# trig3_board_de0-nano.net
KiCad netlist of a schematic drawn in EAGLE
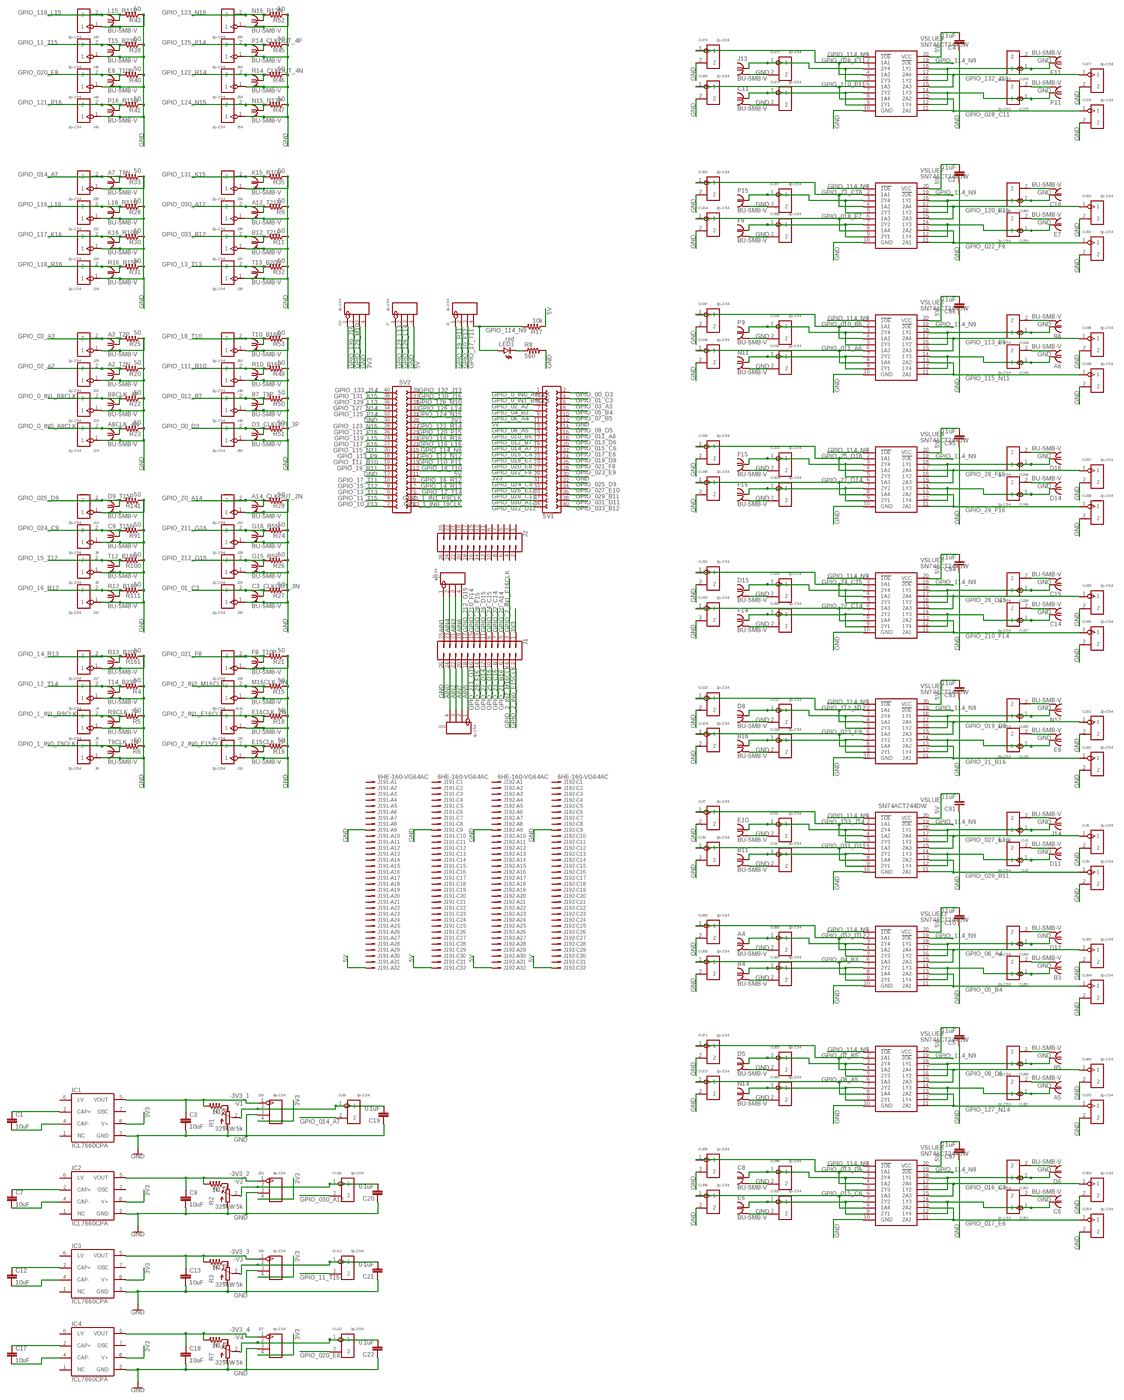
[diagram p0: schematic, sheet 1, overview]
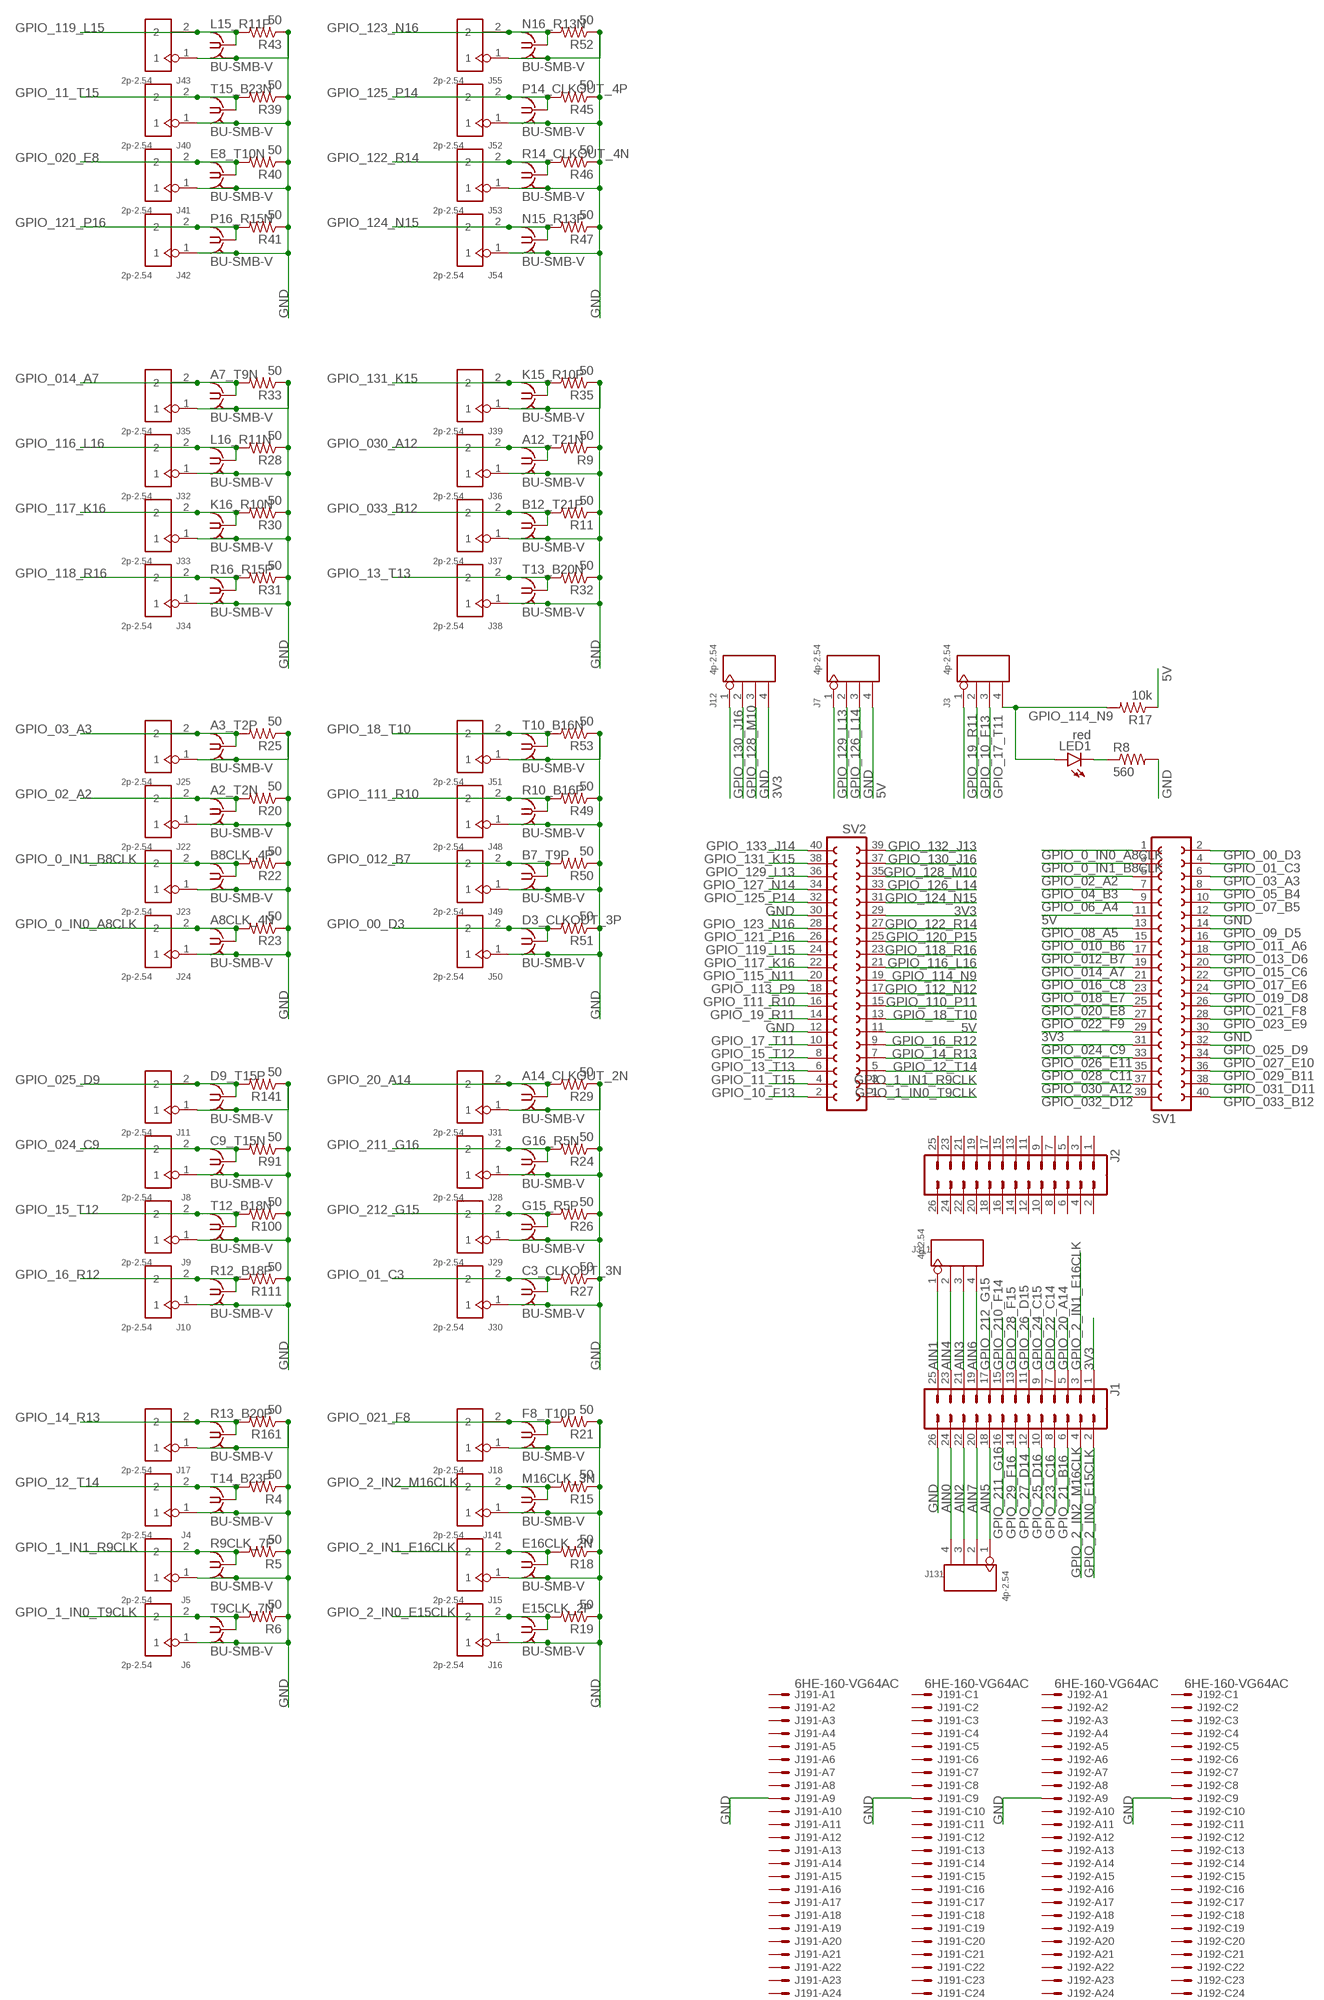
[diagram p1: schematic, sheet 1, part 1 of 4]
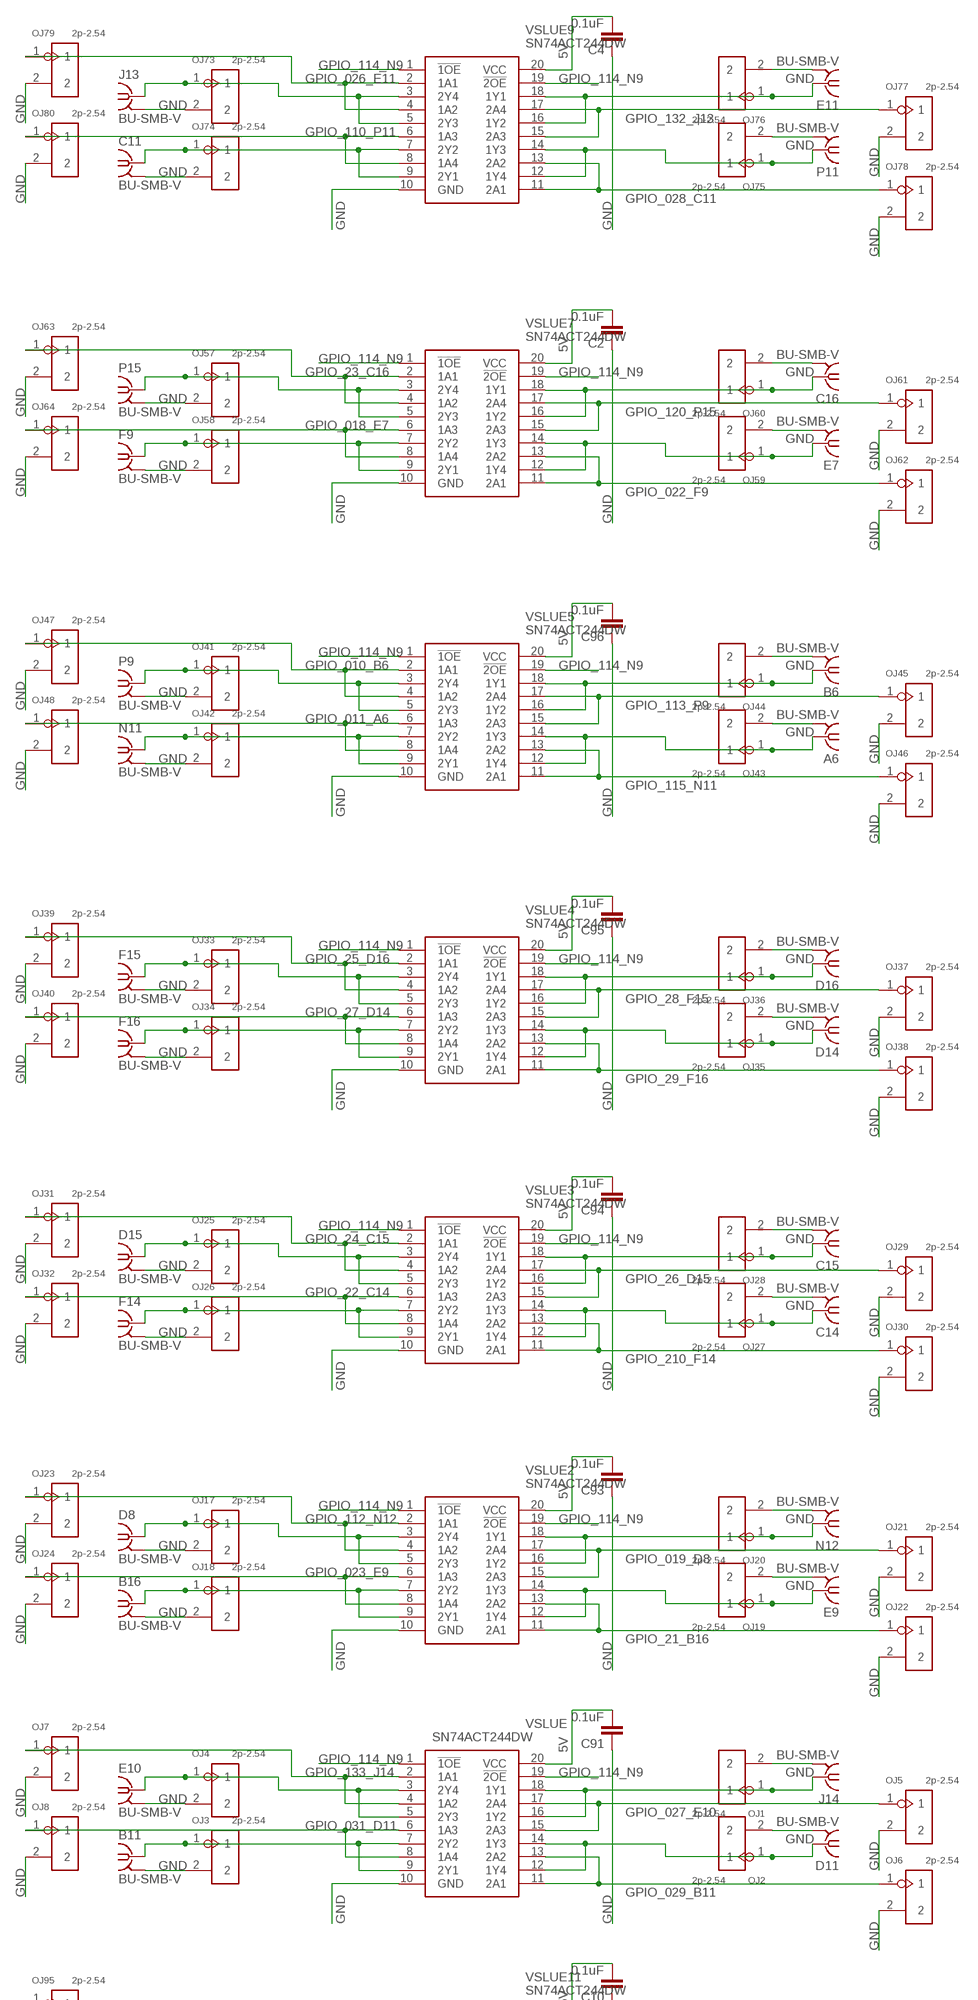
[diagram p2: schematic, sheet 1, part 2 of 4]
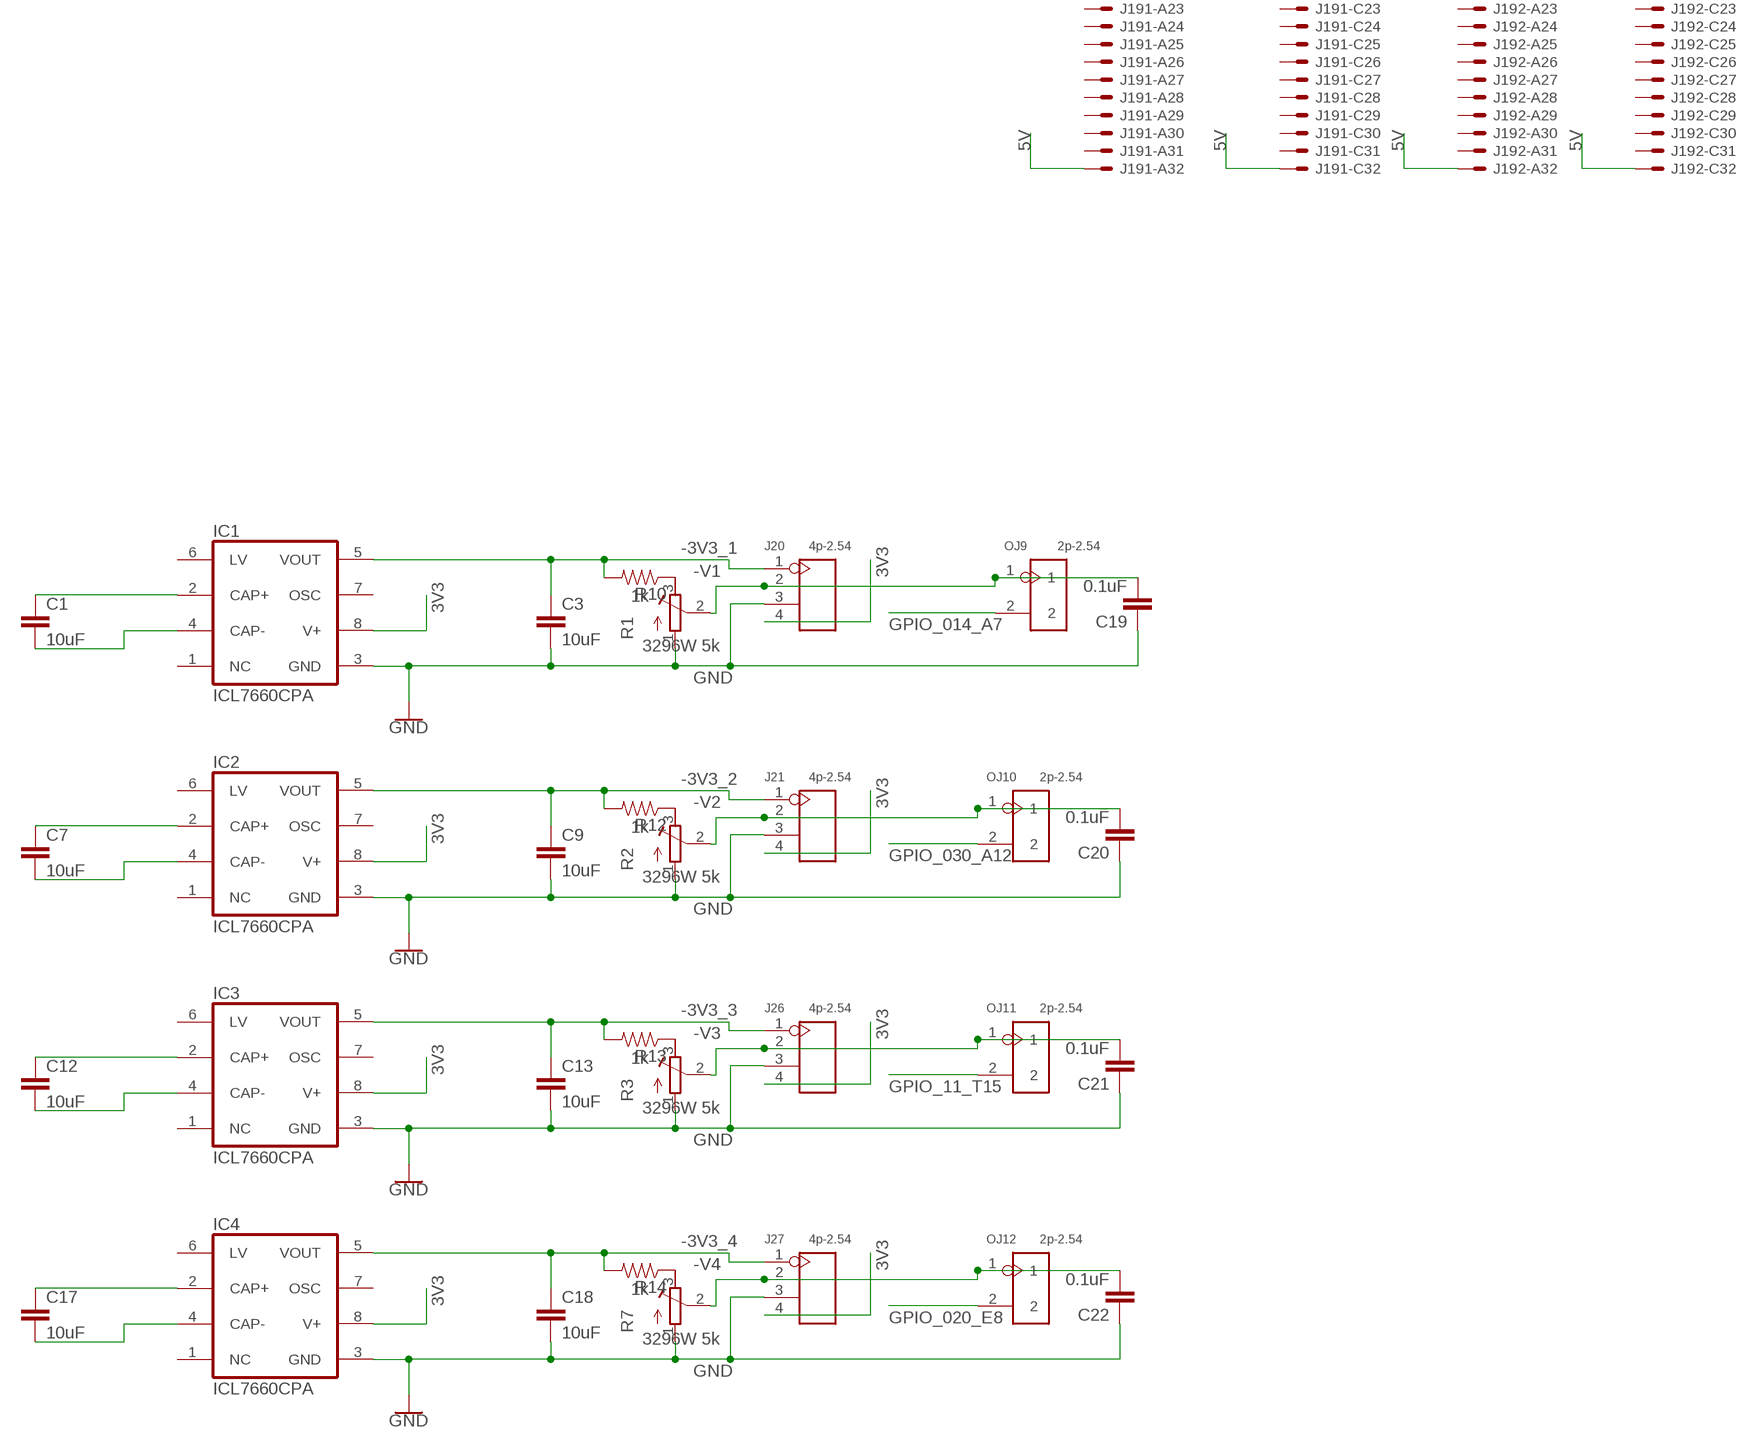
[diagram p3: schematic, sheet 1, part 3 of 4]
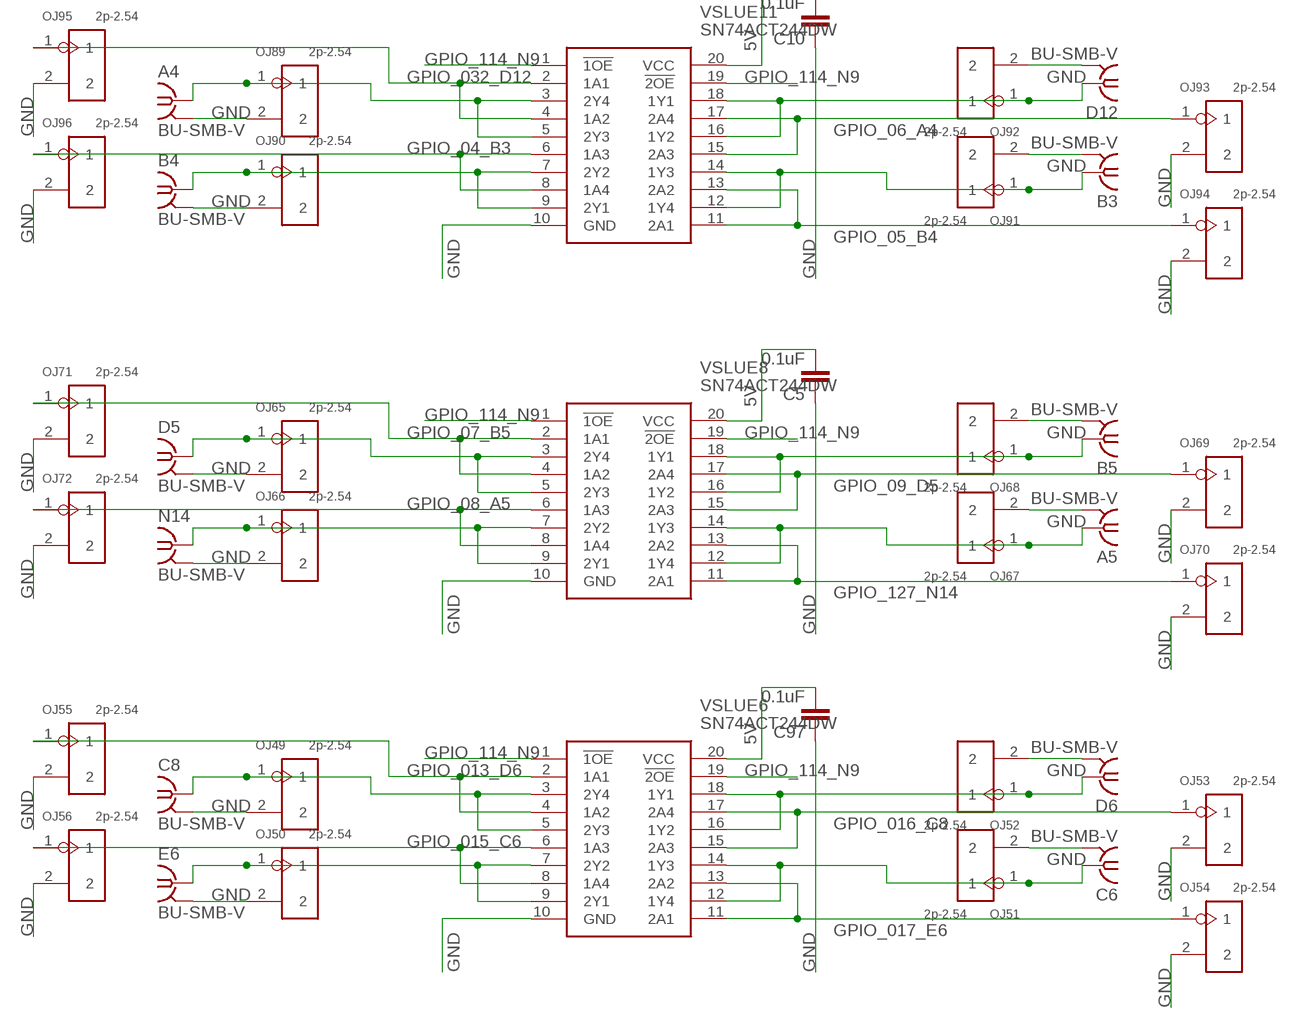
[diagram p4: schematic, sheet 1, part 4 of 4]

(export (version "E")
  (design (tool "Eeschema 10.0.6"))
  (components
    (comp (ref "A2_T2N")
      (value "BU-SMB-V")
      (footprint "eagle-import:BU-SMB-V")
      (libsource (lib "eagle-import") (part "BU-SMB-V"))
    )
    (comp (ref "A3_T2P")
      (value "BU-SMB-V")
      (footprint "eagle-import:BU-SMB-V")
      (libsource (lib "eagle-import") (part "BU-SMB-V"))
    )
    (comp (ref "A4")
      (value "BU-SMB-V")
      (footprint "eagle-import:BU-SMB-V")
      (libsource (lib "eagle-import") (part "BU-SMB-V"))
    )
    (comp (ref "A5")
      (value "BU-SMB-V")
      (footprint "eagle-import:BU-SMB-V")
      (libsource (lib "eagle-import") (part "BU-SMB-V"))
    )
    (comp (ref "A6")
      (value "BU-SMB-V")
      (footprint "eagle-import:BU-SMB-V")
      (libsource (lib "eagle-import") (part "BU-SMB-V"))
    )
    (comp (ref "A7_T9N")
      (value "BU-SMB-V")
      (footprint "eagle-import:BU-SMB-V")
      (libsource (lib "eagle-import") (part "BU-SMB-V"))
    )
    (comp (ref "A8CLK_4N")
      (value "BU-SMB-V")
      (footprint "eagle-import:BU-SMB-V")
      (libsource (lib "eagle-import") (part "BU-SMB-V"))
    )
    (comp (ref "A12_T21N")
      (value "BU-SMB-V")
      (footprint "eagle-import:BU-SMB-V")
      (libsource (lib "eagle-import") (part "BU-SMB-V"))
    )
    (comp (ref "A14_CLKOUT_2N")
      (value "BU-SMB-V")
      (footprint "eagle-import:BU-SMB-V")
      (libsource (lib "eagle-import") (part "BU-SMB-V"))
    )
    (comp (ref "B3")
      (value "BU-SMB-V")
      (footprint "eagle-import:BU-SMB-V")
      (libsource (lib "eagle-import") (part "BU-SMB-V"))
    )
    (comp (ref "B4")
      (value "BU-SMB-V")
      (footprint "eagle-import:BU-SMB-V")
      (libsource (lib "eagle-import") (part "BU-SMB-V"))
    )
    (comp (ref "B5")
      (value "BU-SMB-V")
      (footprint "eagle-import:BU-SMB-V")
      (libsource (lib "eagle-import") (part "BU-SMB-V"))
    )
    (comp (ref "B6")
      (value "BU-SMB-V")
      (footprint "eagle-import:BU-SMB-V")
      (libsource (lib "eagle-import") (part "BU-SMB-V"))
    )
    (comp (ref "B7_T9P")
      (value "BU-SMB-V")
      (footprint "eagle-import:BU-SMB-V")
      (libsource (lib "eagle-import") (part "BU-SMB-V"))
    )
    (comp (ref "B8CLK_4P")
      (value "BU-SMB-V")
      (footprint "eagle-import:BU-SMB-V")
      (libsource (lib "eagle-import") (part "BU-SMB-V"))
    )
    (comp (ref "B11")
      (value "BU-SMB-V")
      (footprint "eagle-import:BU-SMB-V")
      (libsource (lib "eagle-import") (part "BU-SMB-V"))
    )
    (comp (ref "B12_T21P")
      (value "BU-SMB-V")
      (footprint "eagle-import:BU-SMB-V")
      (libsource (lib "eagle-import") (part "BU-SMB-V"))
    )
    (comp (ref "B16")
      (value "BU-SMB-V")
      (footprint "eagle-import:BU-SMB-V")
      (libsource (lib "eagle-import") (part "BU-SMB-V"))
    )
    (comp (ref "C1")
      (value "10uF")
      (footprint "eagle-import:CAP-PTH-5MM")
      (libsource (lib "eagle-import") (part "CAPPTH1"))
    )
    (comp (ref "C2")
      (value "0.1uF")
      (footprint "eagle-import:0805")
      (libsource (lib "eagle-import") (part "CAP0805"))
    )
    (comp (ref "C3")
      (value "10uF")
      (footprint "eagle-import:CAP-PTH-5MM")
      (libsource (lib "eagle-import") (part "CAPPTH1"))
    )
    (comp (ref "C3_CLKOUT_3N")
      (value "BU-SMB-V")
      (footprint "eagle-import:BU-SMB-V")
      (libsource (lib "eagle-import") (part "BU-SMB-V"))
    )
    (comp (ref "C4")
      (value "0.1uF")
      (footprint "eagle-import:0805")
      (libsource (lib "eagle-import") (part "CAP0805"))
    )
    (comp (ref "C5")
      (value "0.1uF")
      (footprint "eagle-import:0805")
      (libsource (lib "eagle-import") (part "CAP0805"))
    )
    (comp (ref "C6")
      (value "BU-SMB-V")
      (footprint "eagle-import:BU-SMB-V")
      (libsource (lib "eagle-import") (part "BU-SMB-V"))
    )
    (comp (ref "C7")
      (value "10uF")
      (footprint "eagle-import:CAP-PTH-5MM")
      (libsource (lib "eagle-import") (part "CAPPTH1"))
    )
    (comp (ref "C8")
      (value "BU-SMB-V")
      (footprint "eagle-import:BU-SMB-V")
      (libsource (lib "eagle-import") (part "BU-SMB-V"))
    )
    (comp (ref "C9")
      (value "10uF")
      (footprint "eagle-import:CAP-PTH-5MM")
      (libsource (lib "eagle-import") (part "CAPPTH1"))
    )
    (comp (ref "C9_T15N")
      (value "BU-SMB-V")
      (footprint "eagle-import:BU-SMB-V")
      (libsource (lib "eagle-import") (part "BU-SMB-V"))
    )
    (comp (ref "C10")
      (value "0.1uF")
      (footprint "eagle-import:0805")
      (libsource (lib "eagle-import") (part "CAP0805"))
    )
    (comp (ref "C11")
      (value "BU-SMB-V")
      (footprint "eagle-import:BU-SMB-V")
      (libsource (lib "eagle-import") (part "BU-SMB-V"))
    )
    (comp (ref "C12")
      (value "10uF")
      (footprint "eagle-import:CAP-PTH-5MM")
      (libsource (lib "eagle-import") (part "CAPPTH1"))
    )
    (comp (ref "C13")
      (value "10uF")
      (footprint "eagle-import:CAP-PTH-5MM")
      (libsource (lib "eagle-import") (part "CAPPTH1"))
    )
    (comp (ref "C14")
      (value "BU-SMB-V")
      (footprint "eagle-import:BU-SMB-V")
      (libsource (lib "eagle-import") (part "BU-SMB-V"))
    )
    (comp (ref "C15")
      (value "BU-SMB-V")
      (footprint "eagle-import:BU-SMB-V")
      (libsource (lib "eagle-import") (part "BU-SMB-V"))
    )
    (comp (ref "C16")
      (value "BU-SMB-V")
      (footprint "eagle-import:BU-SMB-V")
      (libsource (lib "eagle-import") (part "BU-SMB-V"))
    )
    (comp (ref "C17")
      (value "10uF")
      (footprint "eagle-import:CAP-PTH-5MM")
      (libsource (lib "eagle-import") (part "CAPPTH1"))
    )
    (comp (ref "C18")
      (value "10uF")
      (footprint "eagle-import:CAP-PTH-5MM")
      (libsource (lib "eagle-import") (part "CAPPTH1"))
    )
    (comp (ref "C19")
      (value "0.1uF")
      (footprint "eagle-import:0805")
      (libsource (lib "eagle-import") (part "CAP0805"))
    )
    (comp (ref "C20")
      (value "0.1uF")
      (footprint "eagle-import:0805")
      (libsource (lib "eagle-import") (part "CAP0805"))
    )
    (comp (ref "C21")
      (value "0.1uF")
      (footprint "eagle-import:0805")
      (libsource (lib "eagle-import") (part "CAP0805"))
    )
    (comp (ref "C22")
      (value "0.1uF")
      (footprint "eagle-import:0805")
      (libsource (lib "eagle-import") (part "CAP0805"))
    )
    (comp (ref "C91")
      (value "0.1uF")
      (footprint "eagle-import:0805")
      (libsource (lib "eagle-import") (part "CAP0805"))
    )
    (comp (ref "C93")
      (value "0.1uF")
      (footprint "eagle-import:0805")
      (libsource (lib "eagle-import") (part "CAP0805"))
    )
    (comp (ref "C94")
      (value "0.1uF")
      (footprint "eagle-import:0805")
      (libsource (lib "eagle-import") (part "CAP0805"))
    )
    (comp (ref "C95")
      (value "0.1uF")
      (footprint "eagle-import:0805")
      (libsource (lib "eagle-import") (part "CAP0805"))
    )
    (comp (ref "C96")
      (value "0.1uF")
      (footprint "eagle-import:0805")
      (libsource (lib "eagle-import") (part "CAP0805"))
    )
    (comp (ref "C97")
      (value "0.1uF")
      (footprint "eagle-import:0805")
      (libsource (lib "eagle-import") (part "CAP0805"))
    )
    (comp (ref "D3_CLKOUT_3P")
      (value "BU-SMB-V")
      (footprint "eagle-import:BU-SMB-V")
      (libsource (lib "eagle-import") (part "BU-SMB-V"))
    )
    (comp (ref "D5")
      (value "BU-SMB-V")
      (footprint "eagle-import:BU-SMB-V")
      (libsource (lib "eagle-import") (part "BU-SMB-V"))
    )
    (comp (ref "D6")
      (value "BU-SMB-V")
      (footprint "eagle-import:BU-SMB-V")
      (libsource (lib "eagle-import") (part "BU-SMB-V"))
    )
    (comp (ref "D8")
      (value "BU-SMB-V")
      (footprint "eagle-import:BU-SMB-V")
      (libsource (lib "eagle-import") (part "BU-SMB-V"))
    )
    (comp (ref "D9_T15P")
      (value "BU-SMB-V")
      (footprint "eagle-import:BU-SMB-V")
      (libsource (lib "eagle-import") (part "BU-SMB-V"))
    )
    (comp (ref "D11")
      (value "BU-SMB-V")
      (footprint "eagle-import:BU-SMB-V")
      (libsource (lib "eagle-import") (part "BU-SMB-V"))
    )
    (comp (ref "D12")
      (value "BU-SMB-V")
      (footprint "eagle-import:BU-SMB-V")
      (libsource (lib "eagle-import") (part "BU-SMB-V"))
    )
    (comp (ref "D14")
      (value "BU-SMB-V")
      (footprint "eagle-import:BU-SMB-V")
      (libsource (lib "eagle-import") (part "BU-SMB-V"))
    )
    (comp (ref "D15")
      (value "BU-SMB-V")
      (footprint "eagle-import:BU-SMB-V")
      (libsource (lib "eagle-import") (part "BU-SMB-V"))
    )
    (comp (ref "D16")
      (value "BU-SMB-V")
      (footprint "eagle-import:BU-SMB-V")
      (libsource (lib "eagle-import") (part "BU-SMB-V"))
    )
    (comp (ref "E6")
      (value "BU-SMB-V")
      (footprint "eagle-import:BU-SMB-V")
      (libsource (lib "eagle-import") (part "BU-SMB-V"))
    )
    (comp (ref "E7")
      (value "BU-SMB-V")
      (footprint "eagle-import:BU-SMB-V")
      (libsource (lib "eagle-import") (part "BU-SMB-V"))
    )
    (comp (ref "E8_T10N")
      (value "BU-SMB-V")
      (footprint "eagle-import:BU-SMB-V")
      (libsource (lib "eagle-import") (part "BU-SMB-V"))
    )
    (comp (ref "E9")
      (value "BU-SMB-V")
      (footprint "eagle-import:BU-SMB-V")
      (libsource (lib "eagle-import") (part "BU-SMB-V"))
    )
    (comp (ref "E10")
      (value "BU-SMB-V")
      (footprint "eagle-import:BU-SMB-V")
      (libsource (lib "eagle-import") (part "BU-SMB-V"))
    )
    (comp (ref "E11")
      (value "BU-SMB-V")
      (footprint "eagle-import:BU-SMB-V")
      (libsource (lib "eagle-import") (part "BU-SMB-V"))
    )
    (comp (ref "E15CLK_2P")
      (value "BU-SMB-V")
      (footprint "eagle-import:BU-SMB-V")
      (libsource (lib "eagle-import") (part "BU-SMB-V"))
    )
    (comp (ref "E16CLK_2N")
      (value "BU-SMB-V")
      (footprint "eagle-import:BU-SMB-V")
      (libsource (lib "eagle-import") (part "BU-SMB-V"))
    )
    (comp (ref "F8_T10P")
      (value "BU-SMB-V")
      (footprint "eagle-import:BU-SMB-V")
      (libsource (lib "eagle-import") (part "BU-SMB-V"))
    )
    (comp (ref "F9")
      (value "BU-SMB-V")
      (footprint "eagle-import:BU-SMB-V")
      (libsource (lib "eagle-import") (part "BU-SMB-V"))
    )
    (comp (ref "F14")
      (value "BU-SMB-V")
      (footprint "eagle-import:BU-SMB-V")
      (libsource (lib "eagle-import") (part "BU-SMB-V"))
    )
    (comp (ref "F15")
      (value "BU-SMB-V")
      (footprint "eagle-import:BU-SMB-V")
      (libsource (lib "eagle-import") (part "BU-SMB-V"))
    )
    (comp (ref "F16")
      (value "BU-SMB-V")
      (footprint "eagle-import:BU-SMB-V")
      (libsource (lib "eagle-import") (part "BU-SMB-V"))
    )
    (comp (ref "G15_R5P")
      (value "BU-SMB-V")
      (footprint "eagle-import:BU-SMB-V")
      (libsource (lib "eagle-import") (part "BU-SMB-V"))
    )
    (comp (ref "G16_R5N")
      (value "BU-SMB-V")
      (footprint "eagle-import:BU-SMB-V")
      (libsource (lib "eagle-import") (part "BU-SMB-V"))
    )
    (comp (ref "IC1")
      (value "ICL7660CPA")
      (footprint "eagle-import:DIL08")
      (fields (field (name "MF") "INTERSIL"))
      (libsource (lib "eagle-import") (part "ICL7660CPA"))
    )
    (comp (ref "IC2")
      (value "ICL7660CPA")
      (footprint "eagle-import:DIL08")
      (fields (field (name "MF") "INTERSIL"))
      (libsource (lib "eagle-import") (part "ICL7660CPA"))
    )
    (comp (ref "IC3")
      (value "ICL7660CPA")
      (footprint "eagle-import:DIL08")
      (fields (field (name "MF") "INTERSIL"))
      (libsource (lib "eagle-import") (part "ICL7660CPA"))
    )
    (comp (ref "IC4")
      (value "ICL7660CPA")
      (footprint "eagle-import:DIL08")
      (fields (field (name "MF") "INTERSIL"))
      (libsource (lib "eagle-import") (part "ICL7660CPA"))
    )
    (comp (ref "J1")
      (value "M13X22X13")
      (footprint "eagle-import:2X13")
      (libsource (lib "eagle-import") (part "M13X22X13"))
    )
    (comp (ref "J2")
      (value "M13X22X13")
      (footprint "eagle-import:2X13")
      (libsource (lib "eagle-import") (part "M13X22X13"))
    )
    (comp (ref "J3")
      (value "4p-2.54")
      (footprint "eagle-import:H4-2.54")
      (fields (field (name "MPN") "F185-1104A1BSYA1"))
      (libsource (lib "eagle-import") (part "DIP-BLACK-FEMALE-HEADER-VERT(4P-2.54)"))
    )
    (comp (ref "J4")
      (value "2p-2.54")
      (footprint "eagle-import:H2-2.54")
      (fields (field (name "MPN") "P125-1102A0BS116A1"))
      (libsource (lib "eagle-import") (part "DIP-BLACK-MALE-HEADER-VERT(2P-2.54)"))
    )
    (comp (ref "J5")
      (value "2p-2.54")
      (footprint "eagle-import:H2-2.54")
      (fields (field (name "MPN") "P125-1102A0BS116A1"))
      (libsource (lib "eagle-import") (part "DIP-BLACK-MALE-HEADER-VERT(2P-2.54)"))
    )
    (comp (ref "J6")
      (value "2p-2.54")
      (footprint "eagle-import:H2-2.54")
      (fields (field (name "MPN") "P125-1102A0BS116A1"))
      (libsource (lib "eagle-import") (part "DIP-BLACK-MALE-HEADER-VERT(2P-2.54)"))
    )
    (comp (ref "J7")
      (value "4p-2.54")
      (footprint "eagle-import:H4-2.54")
      (fields (field (name "MPN") "F185-1104A1BSYA1"))
      (libsource (lib "eagle-import") (part "DIP-BLACK-FEMALE-HEADER-VERT(4P-2.54)"))
    )
    (comp (ref "J8")
      (value "2p-2.54")
      (footprint "eagle-import:H2-2.54")
      (fields (field (name "MPN") "P125-1102A0BS116A1"))
      (libsource (lib "eagle-import") (part "DIP-BLACK-MALE-HEADER-VERT(2P-2.54)"))
    )
    (comp (ref "J9")
      (value "2p-2.54")
      (footprint "eagle-import:H2-2.54")
      (fields (field (name "MPN") "P125-1102A0BS116A1"))
      (libsource (lib "eagle-import") (part "DIP-BLACK-MALE-HEADER-VERT(2P-2.54)"))
    )
    (comp (ref "J10")
      (value "2p-2.54")
      (footprint "eagle-import:H2-2.54")
      (fields (field (name "MPN") "P125-1102A0BS116A1"))
      (libsource (lib "eagle-import") (part "DIP-BLACK-MALE-HEADER-VERT(2P-2.54)"))
    )
    (comp (ref "J11")
      (value "2p-2.54")
      (footprint "eagle-import:H2-2.54")
      (fields (field (name "MPN") "P125-1102A0BS116A1"))
      (libsource (lib "eagle-import") (part "DIP-BLACK-MALE-HEADER-VERT(2P-2.54)"))
    )
    (comp (ref "J12")
      (value "4p-2.54")
      (footprint "eagle-import:H4-2.54")
      (fields (field (name "MPN") "F185-1104A1BSYA1"))
      (libsource (lib "eagle-import") (part "DIP-BLACK-FEMALE-HEADER-VERT(4P-2.54)"))
    )
    (comp (ref "J13")
      (value "BU-SMB-V")
      (footprint "eagle-import:BU-SMB-V")
      (libsource (lib "eagle-import") (part "BU-SMB-V"))
    )
    (comp (ref "J14")
      (value "BU-SMB-V")
      (footprint "eagle-import:BU-SMB-V")
      (libsource (lib "eagle-import") (part "BU-SMB-V"))
    )
    (comp (ref "J15")
      (value "2p-2.54")
      (footprint "eagle-import:H2-2.54")
      (fields (field (name "MPN") "P125-1102A0BS116A1"))
      (libsource (lib "eagle-import") (part "DIP-BLACK-MALE-HEADER-VERT(2P-2.54)"))
    )
    (comp (ref "J16")
      (value "2p-2.54")
      (footprint "eagle-import:H2-2.54")
      (fields (field (name "MPN") "P125-1102A0BS116A1"))
      (libsource (lib "eagle-import") (part "DIP-BLACK-MALE-HEADER-VERT(2P-2.54)"))
    )
    (comp (ref "J17")
      (value "2p-2.54")
      (footprint "eagle-import:H2-2.54")
      (fields (field (name "MPN") "P125-1102A0BS116A1"))
      (libsource (lib "eagle-import") (part "DIP-BLACK-MALE-HEADER-VERT(2P-2.54)"))
    )
    (comp (ref "J18")
      (value "2p-2.54")
      (footprint "eagle-import:H2-2.54")
      (fields (field (name "MPN") "P125-1102A0BS116A1"))
      (libsource (lib "eagle-import") (part "DIP-BLACK-MALE-HEADER-VERT(2P-2.54)"))
    )
    (comp (ref "J19")
      (value "6HE-160-VG64AC")
      (footprint "eagle-import:6HE_160-VG64AC")
      (libsource (lib "eagle-import") (part "6HE-?-VG64AC160"))
    )
    (comp (ref "J20")
      (value "4p-2.54")
      (footprint "eagle-import:H4-2.54")
      (fields (field (name "MPN") "P125-1104A0BS116A1"))
      (libsource (lib "eagle-import") (part "DIP-BLACK-MALE-HEADER-VERT(4P-2.54)"))
    )
    (comp (ref "J21")
      (value "4p-2.54")
      (footprint "eagle-import:H4-2.54")
      (fields (field (name "MPN") "P125-1104A0BS116A1"))
      (libsource (lib "eagle-import") (part "DIP-BLACK-MALE-HEADER-VERT(4P-2.54)"))
    )
    (comp (ref "J22")
      (value "2p-2.54")
      (footprint "eagle-import:H2-2.54")
      (fields (field (name "MPN") "P125-1102A0BS116A1"))
      (libsource (lib "eagle-import") (part "DIP-BLACK-MALE-HEADER-VERT(2P-2.54)"))
    )
    (comp (ref "J23")
      (value "2p-2.54")
      (footprint "eagle-import:H2-2.54")
      (fields (field (name "MPN") "P125-1102A0BS116A1"))
      (libsource (lib "eagle-import") (part "DIP-BLACK-MALE-HEADER-VERT(2P-2.54)"))
    )
    (comp (ref "J24")
      (value "2p-2.54")
      (footprint "eagle-import:H2-2.54")
      (fields (field (name "MPN") "P125-1102A0BS116A1"))
      (libsource (lib "eagle-import") (part "DIP-BLACK-MALE-HEADER-VERT(2P-2.54)"))
    )
    (comp (ref "J25")
      (value "2p-2.54")
      (footprint "eagle-import:H2-2.54")
      (fields (field (name "MPN") "P125-1102A0BS116A1"))
      (libsource (lib "eagle-import") (part "DIP-BLACK-MALE-HEADER-VERT(2P-2.54)"))
    )
    (comp (ref "J26")
      (value "4p-2.54")
      (footprint "eagle-import:H4-2.54")
      (fields (field (name "MPN") "P125-1104A0BS116A1"))
      (libsource (lib "eagle-import") (part "DIP-BLACK-MALE-HEADER-VERT(4P-2.54)"))
    )
    (comp (ref "J27")
      (value "4p-2.54")
      (footprint "eagle-import:H4-2.54")
      (fields (field (name "MPN") "P125-1104A0BS116A1"))
      (libsource (lib "eagle-import") (part "DIP-BLACK-MALE-HEADER-VERT(4P-2.54)"))
    )
    (comp (ref "J28")
      (value "2p-2.54")
      (footprint "eagle-import:H2-2.54")
      (fields (field (name "MPN") "P125-1102A0BS116A1"))
      (libsource (lib "eagle-import") (part "DIP-BLACK-MALE-HEADER-VERT(2P-2.54)"))
    )
    (comp (ref "J29")
      (value "2p-2.54")
      (footprint "eagle-import:H2-2.54")
      (fields (field (name "MPN") "P125-1102A0BS116A1"))
      (libsource (lib "eagle-import") (part "DIP-BLACK-MALE-HEADER-VERT(2P-2.54)"))
    )
    (comp (ref "J30")
      (value "2p-2.54")
      (footprint "eagle-import:H2-2.54")
      (fields (field (name "MPN") "P125-1102A0BS116A1"))
      (libsource (lib "eagle-import") (part "DIP-BLACK-MALE-HEADER-VERT(2P-2.54)"))
    )
    (comp (ref "J31")
      (value "2p-2.54")
      (footprint "eagle-import:H2-2.54")
      (fields (field (name "MPN") "P125-1102A0BS116A1"))
      (libsource (lib "eagle-import") (part "DIP-BLACK-MALE-HEADER-VERT(2P-2.54)"))
    )
    (comp (ref "J32")
      (value "2p-2.54")
      (footprint "eagle-import:H2-2.54")
      (fields (field (name "MPN") "P125-1102A0BS116A1"))
      (libsource (lib "eagle-import") (part "DIP-BLACK-MALE-HEADER-VERT(2P-2.54)"))
    )
    (comp (ref "J33")
      (value "2p-2.54")
      (footprint "eagle-import:H2-2.54")
      (fields (field (name "MPN") "P125-1102A0BS116A1"))
      (libsource (lib "eagle-import") (part "DIP-BLACK-MALE-HEADER-VERT(2P-2.54)"))
    )
    (comp (ref "J34")
      (value "2p-2.54")
      (footprint "eagle-import:H2-2.54")
      (fields (field (name "MPN") "P125-1102A0BS116A1"))
      (libsource (lib "eagle-import") (part "DIP-BLACK-MALE-HEADER-VERT(2P-2.54)"))
    )
    (comp (ref "J35")
      (value "2p-2.54")
      (footprint "eagle-import:H2-2.54")
      (fields (field (name "MPN") "P125-1102A0BS116A1"))
      (libsource (lib "eagle-import") (part "DIP-BLACK-MALE-HEADER-VERT(2P-2.54)"))
    )
    (comp (ref "J36")
      (value "2p-2.54")
      (footprint "eagle-import:H2-2.54")
      (fields (field (name "MPN") "P125-1102A0BS116A1"))
      (libsource (lib "eagle-import") (part "DIP-BLACK-MALE-HEADER-VERT(2P-2.54)"))
    )
    (comp (ref "J37")
      (value "2p-2.54")
      (footprint "eagle-import:H2-2.54")
      (fields (field (name "MPN") "P125-1102A0BS116A1"))
      (libsource (lib "eagle-import") (part "DIP-BLACK-MALE-HEADER-VERT(2P-2.54)"))
    )
    (comp (ref "J38")
      (value "2p-2.54")
      (footprint "eagle-import:H2-2.54")
      (fields (field (name "MPN") "P125-1102A0BS116A1"))
      (libsource (lib "eagle-import") (part "DIP-BLACK-MALE-HEADER-VERT(2P-2.54)"))
    )
    (comp (ref "J39")
      (value "2p-2.54")
      (footprint "eagle-import:H2-2.54")
      (fields (field (name "MPN") "P125-1102A0BS116A1"))
      (libsource (lib "eagle-import") (part "DIP-BLACK-MALE-HEADER-VERT(2P-2.54)"))
    )
    (comp (ref "J40")
      (value "2p-2.54")
      (footprint "eagle-import:H2-2.54")
      (fields (field (name "MPN") "P125-1102A0BS116A1"))
      (libsource (lib "eagle-import") (part "DIP-BLACK-MALE-HEADER-VERT(2P-2.54)"))
    )
    (comp (ref "J41")
      (value "2p-2.54")
      (footprint "eagle-import:H2-2.54")
      (fields (field (name "MPN") "P125-1102A0BS116A1"))
      (libsource (lib "eagle-import") (part "DIP-BLACK-MALE-HEADER-VERT(2P-2.54)"))
    )
    (comp (ref "J42")
      (value "2p-2.54")
      (footprint "eagle-import:H2-2.54")
      (fields (field (name "MPN") "P125-1102A0BS116A1"))
      (libsource (lib "eagle-import") (part "DIP-BLACK-MALE-HEADER-VERT(2P-2.54)"))
    )
    (comp (ref "J43")
      (value "2p-2.54")
      (footprint "eagle-import:H2-2.54")
      (fields (field (name "MPN") "P125-1102A0BS116A1"))
      (libsource (lib "eagle-import") (part "DIP-BLACK-MALE-HEADER-VERT(2P-2.54)"))
    )
    (comp (ref "J48")
      (value "2p-2.54")
      (footprint "eagle-import:H2-2.54")
      (fields (field (name "MPN") "P125-1102A0BS116A1"))
      (libsource (lib "eagle-import") (part "DIP-BLACK-MALE-HEADER-VERT(2P-2.54)"))
    )
    (comp (ref "J49")
      (value "2p-2.54")
      (footprint "eagle-import:H2-2.54")
      (fields (field (name "MPN") "P125-1102A0BS116A1"))
      (libsource (lib "eagle-import") (part "DIP-BLACK-MALE-HEADER-VERT(2P-2.54)"))
    )
    (comp (ref "J50")
      (value "2p-2.54")
      (footprint "eagle-import:H2-2.54")
      (fields (field (name "MPN") "P125-1102A0BS116A1"))
      (libsource (lib "eagle-import") (part "DIP-BLACK-MALE-HEADER-VERT(2P-2.54)"))
    )
    (comp (ref "J51")
      (value "2p-2.54")
      (footprint "eagle-import:H2-2.54")
      (fields (field (name "MPN") "P125-1102A0BS116A1"))
      (libsource (lib "eagle-import") (part "DIP-BLACK-MALE-HEADER-VERT(2P-2.54)"))
    )
    (comp (ref "J52")
      (value "2p-2.54")
      (footprint "eagle-import:H2-2.54")
      (fields (field (name "MPN") "P125-1102A0BS116A1"))
      (libsource (lib "eagle-import") (part "DIP-BLACK-MALE-HEADER-VERT(2P-2.54)"))
    )
    (comp (ref "J53")
      (value "2p-2.54")
      (footprint "eagle-import:H2-2.54")
      (fields (field (name "MPN") "P125-1102A0BS116A1"))
      (libsource (lib "eagle-import") (part "DIP-BLACK-MALE-HEADER-VERT(2P-2.54)"))
    )
    (comp (ref "J54")
      (value "2p-2.54")
      (footprint "eagle-import:H2-2.54")
      (fields (field (name "MPN") "P125-1102A0BS116A1"))
      (libsource (lib "eagle-import") (part "DIP-BLACK-MALE-HEADER-VERT(2P-2.54)"))
    )
    (comp (ref "J55")
      (value "2p-2.54")
      (footprint "eagle-import:H2-2.54")
      (fields (field (name "MPN") "P125-1102A0BS116A1"))
      (libsource (lib "eagle-import") (part "DIP-BLACK-MALE-HEADER-VERT(2P-2.54)"))
    )
    (comp (ref "J131")
      (value "4p-2.54")
      (footprint "eagle-import:H4-2.54")
      (fields (field (name "MPN") "F185-1104A1BSYA1"))
      (libsource (lib "eagle-import") (part "DIP-BLACK-FEMALE-HEADER-VERT(4P-2.54)"))
    )
    (comp (ref "J141")
      (value "2p-2.54")
      (footprint "eagle-import:H2-2.54")
      (fields (field (name "MPN") "P125-1102A0BS116A1"))
      (libsource (lib "eagle-import") (part "DIP-BLACK-MALE-HEADER-VERT(2P-2.54)"))
    )
    (comp (ref "J311")
      (value "4p-2.54")
      (footprint "eagle-import:H4-2.54")
      (fields (field (name "MPN") "F185-1104A1BSYA1"))
      (libsource (lib "eagle-import") (part "DIP-BLACK-FEMALE-HEADER-VERT(4P-2.54)"))
    )
    (comp (ref "K15_R10P")
      (value "BU-SMB-V")
      (footprint "eagle-import:BU-SMB-V")
      (libsource (lib "eagle-import") (part "BU-SMB-V"))
    )
    (comp (ref "K16_R10N")
      (value "BU-SMB-V")
      (footprint "eagle-import:BU-SMB-V")
      (libsource (lib "eagle-import") (part "BU-SMB-V"))
    )
    (comp (ref "L15_R11P")
      (value "BU-SMB-V")
      (footprint "eagle-import:BU-SMB-V")
      (libsource (lib "eagle-import") (part "BU-SMB-V"))
    )
    (comp (ref "L16_R11N")
      (value "BU-SMB-V")
      (footprint "eagle-import:BU-SMB-V")
      (libsource (lib "eagle-import") (part "BU-SMB-V"))
    )
    (comp (ref "LED1")
      (value "red")
      (footprint "eagle-import:CHIP-LED0805")
      (libsource (lib "eagle-import") (part "LEDCHIP-LED0805"))
    )
    (comp (ref "M16CLK_3N")
      (value "BU-SMB-V")
      (footprint "eagle-import:BU-SMB-V")
      (libsource (lib "eagle-import") (part "BU-SMB-V"))
    )
    (comp (ref "N11")
      (value "BU-SMB-V")
      (footprint "eagle-import:BU-SMB-V")
      (libsource (lib "eagle-import") (part "BU-SMB-V"))
    )
    (comp (ref "N12")
      (value "BU-SMB-V")
      (footprint "eagle-import:BU-SMB-V")
      (libsource (lib "eagle-import") (part "BU-SMB-V"))
    )
    (comp (ref "N14")
      (value "BU-SMB-V")
      (footprint "eagle-import:BU-SMB-V")
      (libsource (lib "eagle-import") (part "BU-SMB-V"))
    )
    (comp (ref "N15_R13P")
      (value "BU-SMB-V")
      (footprint "eagle-import:BU-SMB-V")
      (libsource (lib "eagle-import") (part "BU-SMB-V"))
    )
    (comp (ref "N16_R13N")
      (value "BU-SMB-V")
      (footprint "eagle-import:BU-SMB-V")
      (libsource (lib "eagle-import") (part "BU-SMB-V"))
    )
    (comp (ref "OJ1")
      (value "2p-2.54")
      (footprint "eagle-import:H2-2.54")
      (fields (field (name "MPN") "P125-1102A0BS116A1"))
      (libsource (lib "eagle-import") (part "DIP-BLACK-MALE-HEADER-VERT(2P-2.54)"))
    )
    (comp (ref "OJ2")
      (value "2p-2.54")
      (footprint "eagle-import:H2-2.54")
      (fields (field (name "MPN") "P125-1102A0BS116A1"))
      (libsource (lib "eagle-import") (part "DIP-BLACK-MALE-HEADER-VERT(2P-2.54)"))
    )
    (comp (ref "OJ3")
      (value "2p-2.54")
      (footprint "eagle-import:H2-2.54")
      (fields (field (name "MPN") "P125-1102A0BS116A1"))
      (libsource (lib "eagle-import") (part "DIP-BLACK-MALE-HEADER-VERT(2P-2.54)"))
    )
    (comp (ref "OJ4")
      (value "2p-2.54")
      (footprint "eagle-import:H2-2.54")
      (fields (field (name "MPN") "P125-1102A0BS116A1"))
      (libsource (lib "eagle-import") (part "DIP-BLACK-MALE-HEADER-VERT(2P-2.54)"))
    )
    (comp (ref "OJ5")
      (value "2p-2.54")
      (footprint "eagle-import:H2-2.54")
      (fields (field (name "MPN") "P125-1102A0BS116A1"))
      (libsource (lib "eagle-import") (part "DIP-BLACK-MALE-HEADER-VERT(2P-2.54)"))
    )
    (comp (ref "OJ6")
      (value "2p-2.54")
      (footprint "eagle-import:H2-2.54")
      (fields (field (name "MPN") "P125-1102A0BS116A1"))
      (libsource (lib "eagle-import") (part "DIP-BLACK-MALE-HEADER-VERT(2P-2.54)"))
    )
    (comp (ref "OJ7")
      (value "2p-2.54")
      (footprint "eagle-import:H2-2.54")
      (fields (field (name "MPN") "P125-1102A0BS116A1"))
      (libsource (lib "eagle-import") (part "DIP-BLACK-MALE-HEADER-VERT(2P-2.54)"))
    )
    (comp (ref "OJ8")
      (value "2p-2.54")
      (footprint "eagle-import:H2-2.54")
      (fields (field (name "MPN") "P125-1102A0BS116A1"))
      (libsource (lib "eagle-import") (part "DIP-BLACK-MALE-HEADER-VERT(2P-2.54)"))
    )
    (comp (ref "OJ9")
      (value "2p-2.54")
      (footprint "eagle-import:H2-2.54")
      (fields (field (name "MPN") "P125-1102A0BS116A1"))
      (libsource (lib "eagle-import") (part "DIP-BLACK-MALE-HEADER-VERT(2P-2.54)"))
    )
    (comp (ref "OJ10")
      (value "2p-2.54")
      (footprint "eagle-import:H2-2.54")
      (fields (field (name "MPN") "P125-1102A0BS116A1"))
      (libsource (lib "eagle-import") (part "DIP-BLACK-MALE-HEADER-VERT(2P-2.54)"))
    )
    (comp (ref "OJ11")
      (value "2p-2.54")
      (footprint "eagle-import:H2-2.54")
      (fields (field (name "MPN") "P125-1102A0BS116A1"))
      (libsource (lib "eagle-import") (part "DIP-BLACK-MALE-HEADER-VERT(2P-2.54)"))
    )
    (comp (ref "OJ12")
      (value "2p-2.54")
      (footprint "eagle-import:H2-2.54")
      (fields (field (name "MPN") "P125-1102A0BS116A1"))
      (libsource (lib "eagle-import") (part "DIP-BLACK-MALE-HEADER-VERT(2P-2.54)"))
    )
    (comp (ref "OJ17")
      (value "2p-2.54")
      (footprint "eagle-import:H2-2.54")
      (fields (field (name "MPN") "P125-1102A0BS116A1"))
      (libsource (lib "eagle-import") (part "DIP-BLACK-MALE-HEADER-VERT(2P-2.54)"))
    )
    (comp (ref "OJ18")
      (value "2p-2.54")
      (footprint "eagle-import:H2-2.54")
      (fields (field (name "MPN") "P125-1102A0BS116A1"))
      (libsource (lib "eagle-import") (part "DIP-BLACK-MALE-HEADER-VERT(2P-2.54)"))
    )
    (comp (ref "OJ19")
      (value "2p-2.54")
      (footprint "eagle-import:H2-2.54")
      (fields (field (name "MPN") "P125-1102A0BS116A1"))
      (libsource (lib "eagle-import") (part "DIP-BLACK-MALE-HEADER-VERT(2P-2.54)"))
    )
    (comp (ref "OJ20")
      (value "2p-2.54")
      (footprint "eagle-import:H2-2.54")
      (fields (field (name "MPN") "P125-1102A0BS116A1"))
      (libsource (lib "eagle-import") (part "DIP-BLACK-MALE-HEADER-VERT(2P-2.54)"))
    )
    (comp (ref "OJ21")
      (value "2p-2.54")
      (footprint "eagle-import:H2-2.54")
      (fields (field (name "MPN") "P125-1102A0BS116A1"))
      (libsource (lib "eagle-import") (part "DIP-BLACK-MALE-HEADER-VERT(2P-2.54)"))
    )
    (comp (ref "OJ22")
      (value "2p-2.54")
      (footprint "eagle-import:H2-2.54")
      (fields (field (name "MPN") "P125-1102A0BS116A1"))
      (libsource (lib "eagle-import") (part "DIP-BLACK-MALE-HEADER-VERT(2P-2.54)"))
    )
    (comp (ref "OJ23")
      (value "2p-2.54")
      (footprint "eagle-import:H2-2.54")
      (fields (field (name "MPN") "P125-1102A0BS116A1"))
      (libsource (lib "eagle-import") (part "DIP-BLACK-MALE-HEADER-VERT(2P-2.54)"))
    )
    (comp (ref "OJ24")
      (value "2p-2.54")
      (footprint "eagle-import:H2-2.54")
      (fields (field (name "MPN") "P125-1102A0BS116A1"))
      (libsource (lib "eagle-import") (part "DIP-BLACK-MALE-HEADER-VERT(2P-2.54)"))
    )
    (comp (ref "OJ25")
      (value "2p-2.54")
      (footprint "eagle-import:H2-2.54")
      (fields (field (name "MPN") "P125-1102A0BS116A1"))
      (libsource (lib "eagle-import") (part "DIP-BLACK-MALE-HEADER-VERT(2P-2.54)"))
    )
    (comp (ref "OJ26")
      (value "2p-2.54")
      (footprint "eagle-import:H2-2.54")
      (fields (field (name "MPN") "P125-1102A0BS116A1"))
      (libsource (lib "eagle-import") (part "DIP-BLACK-MALE-HEADER-VERT(2P-2.54)"))
    )
    (comp (ref "OJ27")
      (value "2p-2.54")
      (footprint "eagle-import:H2-2.54")
      (fields (field (name "MPN") "P125-1102A0BS116A1"))
      (libsource (lib "eagle-import") (part "DIP-BLACK-MALE-HEADER-VERT(2P-2.54)"))
    )
    (comp (ref "OJ28")
      (value "2p-2.54")
      (footprint "eagle-import:H2-2.54")
      (fields (field (name "MPN") "P125-1102A0BS116A1"))
      (libsource (lib "eagle-import") (part "DIP-BLACK-MALE-HEADER-VERT(2P-2.54)"))
    )
    (comp (ref "OJ29")
      (value "2p-2.54")
      (footprint "eagle-import:H2-2.54")
      (fields (field (name "MPN") "P125-1102A0BS116A1"))
      (libsource (lib "eagle-import") (part "DIP-BLACK-MALE-HEADER-VERT(2P-2.54)"))
    )
    (comp (ref "OJ30")
      (value "2p-2.54")
      (footprint "eagle-import:H2-2.54")
      (fields (field (name "MPN") "P125-1102A0BS116A1"))
      (libsource (lib "eagle-import") (part "DIP-BLACK-MALE-HEADER-VERT(2P-2.54)"))
    )
    (comp (ref "OJ31")
      (value "2p-2.54")
      (footprint "eagle-import:H2-2.54")
      (fields (field (name "MPN") "P125-1102A0BS116A1"))
      (libsource (lib "eagle-import") (part "DIP-BLACK-MALE-HEADER-VERT(2P-2.54)"))
    )
    (comp (ref "OJ32")
      (value "2p-2.54")
      (footprint "eagle-import:H2-2.54")
      (fields (field (name "MPN") "P125-1102A0BS116A1"))
      (libsource (lib "eagle-import") (part "DIP-BLACK-MALE-HEADER-VERT(2P-2.54)"))
    )
    (comp (ref "OJ33")
      (value "2p-2.54")
      (footprint "eagle-import:H2-2.54")
      (fields (field (name "MPN") "P125-1102A0BS116A1"))
      (libsource (lib "eagle-import") (part "DIP-BLACK-MALE-HEADER-VERT(2P-2.54)"))
    )
    (comp (ref "OJ34")
      (value "2p-2.54")
      (footprint "eagle-import:H2-2.54")
      (fields (field (name "MPN") "P125-1102A0BS116A1"))
      (libsource (lib "eagle-import") (part "DIP-BLACK-MALE-HEADER-VERT(2P-2.54)"))
    )
    (comp (ref "OJ35")
      (value "2p-2.54")
      (footprint "eagle-import:H2-2.54")
      (fields (field (name "MPN") "P125-1102A0BS116A1"))
      (libsource (lib "eagle-import") (part "DIP-BLACK-MALE-HEADER-VERT(2P-2.54)"))
    )
    (comp (ref "OJ36")
      (value "2p-2.54")
      (footprint "eagle-import:H2-2.54")
      (fields (field (name "MPN") "P125-1102A0BS116A1"))
      (libsource (lib "eagle-import") (part "DIP-BLACK-MALE-HEADER-VERT(2P-2.54)"))
    )
    (comp (ref "OJ37")
      (value "2p-2.54")
      (footprint "eagle-import:H2-2.54")
      (fields (field (name "MPN") "P125-1102A0BS116A1"))
      (libsource (lib "eagle-import") (part "DIP-BLACK-MALE-HEADER-VERT(2P-2.54)"))
    )
    (comp (ref "OJ38")
      (value "2p-2.54")
      (footprint "eagle-import:H2-2.54")
      (fields (field (name "MPN") "P125-1102A0BS116A1"))
      (libsource (lib "eagle-import") (part "DIP-BLACK-MALE-HEADER-VERT(2P-2.54)"))
    )
    (comp (ref "OJ39")
      (value "2p-2.54")
      (footprint "eagle-import:H2-2.54")
      (fields (field (name "MPN") "P125-1102A0BS116A1"))
      (libsource (lib "eagle-import") (part "DIP-BLACK-MALE-HEADER-VERT(2P-2.54)"))
    )
    (comp (ref "OJ40")
      (value "2p-2.54")
      (footprint "eagle-import:H2-2.54")
      (fields (field (name "MPN") "P125-1102A0BS116A1"))
      (libsource (lib "eagle-import") (part "DIP-BLACK-MALE-HEADER-VERT(2P-2.54)"))
    )
    (comp (ref "OJ41")
      (value "2p-2.54")
      (footprint "eagle-import:H2-2.54")
      (fields (field (name "MPN") "P125-1102A0BS116A1"))
      (libsource (lib "eagle-import") (part "DIP-BLACK-MALE-HEADER-VERT(2P-2.54)"))
    )
    (comp (ref "OJ42")
      (value "2p-2.54")
      (footprint "eagle-import:H2-2.54")
      (fields (field (name "MPN") "P125-1102A0BS116A1"))
      (libsource (lib "eagle-import") (part "DIP-BLACK-MALE-HEADER-VERT(2P-2.54)"))
    )
    (comp (ref "OJ43")
      (value "2p-2.54")
      (footprint "eagle-import:H2-2.54")
      (fields (field (name "MPN") "P125-1102A0BS116A1"))
      (libsource (lib "eagle-import") (part "DIP-BLACK-MALE-HEADER-VERT(2P-2.54)"))
    )
    (comp (ref "OJ44")
      (value "2p-2.54")
      (footprint "eagle-import:H2-2.54")
      (fields (field (name "MPN") "P125-1102A0BS116A1"))
      (libsource (lib "eagle-import") (part "DIP-BLACK-MALE-HEADER-VERT(2P-2.54)"))
    )
    (comp (ref "OJ45")
      (value "2p-2.54")
      (footprint "eagle-import:H2-2.54")
      (fields (field (name "MPN") "P125-1102A0BS116A1"))
      (libsource (lib "eagle-import") (part "DIP-BLACK-MALE-HEADER-VERT(2P-2.54)"))
    )
    (comp (ref "OJ46")
      (value "2p-2.54")
      (footprint "eagle-import:H2-2.54")
      (fields (field (name "MPN") "P125-1102A0BS116A1"))
      (libsource (lib "eagle-import") (part "DIP-BLACK-MALE-HEADER-VERT(2P-2.54)"))
    )
    (comp (ref "OJ47")
      (value "2p-2.54")
      (footprint "eagle-import:H2-2.54")
      (fields (field (name "MPN") "P125-1102A0BS116A1"))
      (libsource (lib "eagle-import") (part "DIP-BLACK-MALE-HEADER-VERT(2P-2.54)"))
    )
    (comp (ref "OJ48")
      (value "2p-2.54")
      (footprint "eagle-import:H2-2.54")
      (fields (field (name "MPN") "P125-1102A0BS116A1"))
      (libsource (lib "eagle-import") (part "DIP-BLACK-MALE-HEADER-VERT(2P-2.54)"))
    )
    (comp (ref "OJ49")
      (value "2p-2.54")
      (footprint "eagle-import:H2-2.54")
      (fields (field (name "MPN") "P125-1102A0BS116A1"))
      (libsource (lib "eagle-import") (part "DIP-BLACK-MALE-HEADER-VERT(2P-2.54)"))
    )
    (comp (ref "OJ50")
      (value "2p-2.54")
      (footprint "eagle-import:H2-2.54")
      (fields (field (name "MPN") "P125-1102A0BS116A1"))
      (libsource (lib "eagle-import") (part "DIP-BLACK-MALE-HEADER-VERT(2P-2.54)"))
    )
    (comp (ref "OJ51")
      (value "2p-2.54")
      (footprint "eagle-import:H2-2.54")
      (fields (field (name "MPN") "P125-1102A0BS116A1"))
      (libsource (lib "eagle-import") (part "DIP-BLACK-MALE-HEADER-VERT(2P-2.54)"))
    )
    (comp (ref "OJ52")
      (value "2p-2.54")
      (footprint "eagle-import:H2-2.54")
      (fields (field (name "MPN") "P125-1102A0BS116A1"))
      (libsource (lib "eagle-import") (part "DIP-BLACK-MALE-HEADER-VERT(2P-2.54)"))
    )
    (comp (ref "OJ53")
      (value "2p-2.54")
      (footprint "eagle-import:H2-2.54")
      (fields (field (name "MPN") "P125-1102A0BS116A1"))
      (libsource (lib "eagle-import") (part "DIP-BLACK-MALE-HEADER-VERT(2P-2.54)"))
    )
    (comp (ref "OJ54")
      (value "2p-2.54")
      (footprint "eagle-import:H2-2.54")
      (fields (field (name "MPN") "P125-1102A0BS116A1"))
      (libsource (lib "eagle-import") (part "DIP-BLACK-MALE-HEADER-VERT(2P-2.54)"))
    )
    (comp (ref "OJ55")
      (value "2p-2.54")
      (footprint "eagle-import:H2-2.54")
      (fields (field (name "MPN") "P125-1102A0BS116A1"))
      (libsource (lib "eagle-import") (part "DIP-BLACK-MALE-HEADER-VERT(2P-2.54)"))
    )
    (comp (ref "OJ56")
      (value "2p-2.54")
      (footprint "eagle-import:H2-2.54")
      (fields (field (name "MPN") "P125-1102A0BS116A1"))
      (libsource (lib "eagle-import") (part "DIP-BLACK-MALE-HEADER-VERT(2P-2.54)"))
    )
    (comp (ref "OJ57")
      (value "2p-2.54")
      (footprint "eagle-import:H2-2.54")
      (fields (field (name "MPN") "P125-1102A0BS116A1"))
      (libsource (lib "eagle-import") (part "DIP-BLACK-MALE-HEADER-VERT(2P-2.54)"))
    )
    (comp (ref "OJ58")
      (value "2p-2.54")
      (footprint "eagle-import:H2-2.54")
      (fields (field (name "MPN") "P125-1102A0BS116A1"))
      (libsource (lib "eagle-import") (part "DIP-BLACK-MALE-HEADER-VERT(2P-2.54)"))
    )
    (comp (ref "OJ59")
      (value "2p-2.54")
      (footprint "eagle-import:H2-2.54")
      (fields (field (name "MPN") "P125-1102A0BS116A1"))
      (libsource (lib "eagle-import") (part "DIP-BLACK-MALE-HEADER-VERT(2P-2.54)"))
    )
    (comp (ref "OJ60")
      (value "2p-2.54")
      (footprint "eagle-import:H2-2.54")
      (fields (field (name "MPN") "P125-1102A0BS116A1"))
      (libsource (lib "eagle-import") (part "DIP-BLACK-MALE-HEADER-VERT(2P-2.54)"))
    )
    (comp (ref "OJ61")
      (value "2p-2.54")
      (footprint "eagle-import:H2-2.54")
      (fields (field (name "MPN") "P125-1102A0BS116A1"))
      (libsource (lib "eagle-import") (part "DIP-BLACK-MALE-HEADER-VERT(2P-2.54)"))
    )
    (comp (ref "OJ62")
      (value "2p-2.54")
      (footprint "eagle-import:H2-2.54")
      (fields (field (name "MPN") "P125-1102A0BS116A1"))
      (libsource (lib "eagle-import") (part "DIP-BLACK-MALE-HEADER-VERT(2P-2.54)"))
    )
    (comp (ref "OJ63")
      (value "2p-2.54")
      (footprint "eagle-import:H2-2.54")
      (fields (field (name "MPN") "P125-1102A0BS116A1"))
      (libsource (lib "eagle-import") (part "DIP-BLACK-MALE-HEADER-VERT(2P-2.54)"))
    )
    (comp (ref "OJ64")
      (value "2p-2.54")
      (footprint "eagle-import:H2-2.54")
      (fields (field (name "MPN") "P125-1102A0BS116A1"))
      (libsource (lib "eagle-import") (part "DIP-BLACK-MALE-HEADER-VERT(2P-2.54)"))
    )
    (comp (ref "OJ65")
      (value "2p-2.54")
      (footprint "eagle-import:H2-2.54")
      (fields (field (name "MPN") "P125-1102A0BS116A1"))
      (libsource (lib "eagle-import") (part "DIP-BLACK-MALE-HEADER-VERT(2P-2.54)"))
    )
    (comp (ref "OJ66")
      (value "2p-2.54")
      (footprint "eagle-import:H2-2.54")
      (fields (field (name "MPN") "P125-1102A0BS116A1"))
      (libsource (lib "eagle-import") (part "DIP-BLACK-MALE-HEADER-VERT(2P-2.54)"))
    )
    (comp (ref "OJ67")
      (value "2p-2.54")
      (footprint "eagle-import:H2-2.54")
      (fields (field (name "MPN") "P125-1102A0BS116A1"))
      (libsource (lib "eagle-import") (part "DIP-BLACK-MALE-HEADER-VERT(2P-2.54)"))
    )
    (comp (ref "OJ68")
      (value "2p-2.54")
      (footprint "eagle-import:H2-2.54")
      (fields (field (name "MPN") "P125-1102A0BS116A1"))
      (libsource (lib "eagle-import") (part "DIP-BLACK-MALE-HEADER-VERT(2P-2.54)"))
    )
    (comp (ref "OJ69")
      (value "2p-2.54")
      (footprint "eagle-import:H2-2.54")
      (fields (field (name "MPN") "P125-1102A0BS116A1"))
      (libsource (lib "eagle-import") (part "DIP-BLACK-MALE-HEADER-VERT(2P-2.54)"))
    )
    (comp (ref "OJ70")
      (value "2p-2.54")
      (footprint "eagle-import:H2-2.54")
      (fields (field (name "MPN") "P125-1102A0BS116A1"))
      (libsource (lib "eagle-import") (part "DIP-BLACK-MALE-HEADER-VERT(2P-2.54)"))
    )
    (comp (ref "OJ71")
      (value "2p-2.54")
      (footprint "eagle-import:H2-2.54")
      (fields (field (name "MPN") "P125-1102A0BS116A1"))
      (libsource (lib "eagle-import") (part "DIP-BLACK-MALE-HEADER-VERT(2P-2.54)"))
    )
    (comp (ref "OJ72")
      (value "2p-2.54")
      (footprint "eagle-import:H2-2.54")
      (fields (field (name "MPN") "P125-1102A0BS116A1"))
      (libsource (lib "eagle-import") (part "DIP-BLACK-MALE-HEADER-VERT(2P-2.54)"))
    )
    (comp (ref "OJ73")
      (value "2p-2.54")
      (footprint "eagle-import:H2-2.54")
      (fields (field (name "MPN") "P125-1102A0BS116A1"))
      (libsource (lib "eagle-import") (part "DIP-BLACK-MALE-HEADER-VERT(2P-2.54)"))
    )
    (comp (ref "OJ74")
      (value "2p-2.54")
      (footprint "eagle-import:H2-2.54")
      (fields (field (name "MPN") "P125-1102A0BS116A1"))
      (libsource (lib "eagle-import") (part "DIP-BLACK-MALE-HEADER-VERT(2P-2.54)"))
    )
    (comp (ref "OJ75")
      (value "2p-2.54")
      (footprint "eagle-import:H2-2.54")
      (fields (field (name "MPN") "P125-1102A0BS116A1"))
      (libsource (lib "eagle-import") (part "DIP-BLACK-MALE-HEADER-VERT(2P-2.54)"))
    )
    (comp (ref "OJ76")
      (value "2p-2.54")
      (footprint "eagle-import:H2-2.54")
      (fields (field (name "MPN") "P125-1102A0BS116A1"))
      (libsource (lib "eagle-import") (part "DIP-BLACK-MALE-HEADER-VERT(2P-2.54)"))
    )
    (comp (ref "OJ77")
      (value "2p-2.54")
      (footprint "eagle-import:H2-2.54")
      (fields (field (name "MPN") "P125-1102A0BS116A1"))
      (libsource (lib "eagle-import") (part "DIP-BLACK-MALE-HEADER-VERT(2P-2.54)"))
    )
    (comp (ref "OJ78")
      (value "2p-2.54")
      (footprint "eagle-import:H2-2.54")
      (fields (field (name "MPN") "P125-1102A0BS116A1"))
      (libsource (lib "eagle-import") (part "DIP-BLACK-MALE-HEADER-VERT(2P-2.54)"))
    )
    (comp (ref "OJ79")
      (value "2p-2.54")
      (footprint "eagle-import:H2-2.54")
      (fields (field (name "MPN") "P125-1102A0BS116A1"))
      (libsource (lib "eagle-import") (part "DIP-BLACK-MALE-HEADER-VERT(2P-2.54)"))
    )
    (comp (ref "OJ80")
      (value "2p-2.54")
      (footprint "eagle-import:H2-2.54")
      (fields (field (name "MPN") "P125-1102A0BS116A1"))
      (libsource (lib "eagle-import") (part "DIP-BLACK-MALE-HEADER-VERT(2P-2.54)"))
    )
    (comp (ref "OJ89")
      (value "2p-2.54")
      (footprint "eagle-import:H2-2.54")
      (fields (field (name "MPN") "P125-1102A0BS116A1"))
      (libsource (lib "eagle-import") (part "DIP-BLACK-MALE-HEADER-VERT(2P-2.54)"))
    )
    (comp (ref "OJ90")
      (value "2p-2.54")
      (footprint "eagle-import:H2-2.54")
      (fields (field (name "MPN") "P125-1102A0BS116A1"))
      (libsource (lib "eagle-import") (part "DIP-BLACK-MALE-HEADER-VERT(2P-2.54)"))
    )
    (comp (ref "OJ91")
      (value "2p-2.54")
      (footprint "eagle-import:H2-2.54")
      (fields (field (name "MPN") "P125-1102A0BS116A1"))
      (libsource (lib "eagle-import") (part "DIP-BLACK-MALE-HEADER-VERT(2P-2.54)"))
    )
    (comp (ref "OJ92")
      (value "2p-2.54")
      (footprint "eagle-import:H2-2.54")
      (fields (field (name "MPN") "P125-1102A0BS116A1"))
      (libsource (lib "eagle-import") (part "DIP-BLACK-MALE-HEADER-VERT(2P-2.54)"))
    )
    (comp (ref "OJ93")
      (value "2p-2.54")
      (footprint "eagle-import:H2-2.54")
      (fields (field (name "MPN") "P125-1102A0BS116A1"))
      (libsource (lib "eagle-import") (part "DIP-BLACK-MALE-HEADER-VERT(2P-2.54)"))
    )
    (comp (ref "OJ94")
      (value "2p-2.54")
      (footprint "eagle-import:H2-2.54")
      (fields (field (name "MPN") "P125-1102A0BS116A1"))
      (libsource (lib "eagle-import") (part "DIP-BLACK-MALE-HEADER-VERT(2P-2.54)"))
    )
    (comp (ref "OJ95")
      (value "2p-2.54")
      (footprint "eagle-import:H2-2.54")
      (fields (field (name "MPN") "P125-1102A0BS116A1"))
      (libsource (lib "eagle-import") (part "DIP-BLACK-MALE-HEADER-VERT(2P-2.54)"))
    )
    (comp (ref "OJ96")
      (value "2p-2.54")
      (footprint "eagle-import:H2-2.54")
      (fields (field (name "MPN") "P125-1102A0BS116A1"))
      (libsource (lib "eagle-import") (part "DIP-BLACK-MALE-HEADER-VERT(2P-2.54)"))
    )
    (comp (ref "P9")
      (value "BU-SMB-V")
      (footprint "eagle-import:BU-SMB-V")
      (libsource (lib "eagle-import") (part "BU-SMB-V"))
    )
    (comp (ref "P11")
      (value "BU-SMB-V")
      (footprint "eagle-import:BU-SMB-V")
      (libsource (lib "eagle-import") (part "BU-SMB-V"))
    )
    (comp (ref "P14_CLKOUT_4P")
      (value "BU-SMB-V")
      (footprint "eagle-import:BU-SMB-V")
      (libsource (lib "eagle-import") (part "BU-SMB-V"))
    )
    (comp (ref "P15")
      (value "BU-SMB-V")
      (footprint "eagle-import:BU-SMB-V")
      (libsource (lib "eagle-import") (part "BU-SMB-V"))
    )
    (comp (ref "P16_R15N")
      (value "BU-SMB-V")
      (footprint "eagle-import:BU-SMB-V")
      (libsource (lib "eagle-import") (part "BU-SMB-V"))
    )
    (comp (ref "R1")
      (value "3296W 5k")
      (footprint "eagle-import:RTRIM3296W")
      (libsource (lib "eagle-import") (part "R-TRIMM3296W"))
    )
    (comp (ref "R2")
      (value "3296W 5k")
      (footprint "eagle-import:RTRIM3296W")
      (libsource (lib "eagle-import") (part "R-TRIMM3296W"))
    )
    (comp (ref "R3")
      (value "3296W 5k")
      (footprint "eagle-import:RTRIM3296W")
      (libsource (lib "eagle-import") (part "R-TRIMM3296W"))
    )
    (comp (ref "R4")
      (value "50")
      (footprint "eagle-import:AXIAL-0.3")
      (libsource (lib "eagle-import") (part "RESISTORAXIAL-0.3"))
    )
    (comp (ref "R5")
      (value "50")
      (footprint "eagle-import:AXIAL-0.3")
      (libsource (lib "eagle-import") (part "RESISTORAXIAL-0.3"))
    )
    (comp (ref "R6")
      (value "50")
      (footprint "eagle-import:AXIAL-0.3")
      (libsource (lib "eagle-import") (part "RESISTORAXIAL-0.3"))
    )
    (comp (ref "R7")
      (value "3296W 5k")
      (footprint "eagle-import:RTRIM3296W")
      (libsource (lib "eagle-import") (part "R-TRIMM3296W"))
    )
    (comp (ref "R8")
      (value "560")
      (footprint "eagle-import:R0805")
      (libsource (lib "eagle-import") (part "R-US_R0805"))
    )
    (comp (ref "R9")
      (value "50")
      (footprint "eagle-import:AXIAL-0.3")
      (libsource (lib "eagle-import") (part "RESISTORAXIAL-0.3"))
    )
    (comp (ref "R9CLK_7P")
      (value "BU-SMB-V")
      (footprint "eagle-import:BU-SMB-V")
      (libsource (lib "eagle-import") (part "BU-SMB-V"))
    )
    (comp (ref "R10")
      (value "1k")
      (footprint "eagle-import:AXIAL-0.3")
      (libsource (lib "eagle-import") (part "RESISTORAXIAL-0.3"))
    )
    (comp (ref "R10_B16P")
      (value "BU-SMB-V")
      (footprint "eagle-import:BU-SMB-V")
      (libsource (lib "eagle-import") (part "BU-SMB-V"))
    )
    (comp (ref "R11")
      (value "50")
      (footprint "eagle-import:AXIAL-0.3")
      (libsource (lib "eagle-import") (part "RESISTORAXIAL-0.3"))
    )
    (comp (ref "R12")
      (value "1k")
      (footprint "eagle-import:AXIAL-0.3")
      (libsource (lib "eagle-import") (part "RESISTORAXIAL-0.3"))
    )
    (comp (ref "R12_B18P")
      (value "BU-SMB-V")
      (footprint "eagle-import:BU-SMB-V")
      (libsource (lib "eagle-import") (part "BU-SMB-V"))
    )
    (comp (ref "R13")
      (value "1k")
      (footprint "eagle-import:AXIAL-0.3")
      (libsource (lib "eagle-import") (part "RESISTORAXIAL-0.3"))
    )
    (comp (ref "R13_B20P")
      (value "BU-SMB-V")
      (footprint "eagle-import:BU-SMB-V")
      (libsource (lib "eagle-import") (part "BU-SMB-V"))
    )
    (comp (ref "R14")
      (value "1k")
      (footprint "eagle-import:AXIAL-0.3")
      (libsource (lib "eagle-import") (part "RESISTORAXIAL-0.3"))
    )
    (comp (ref "R14_CLKOUT_4N")
      (value "BU-SMB-V")
      (footprint "eagle-import:BU-SMB-V")
      (libsource (lib "eagle-import") (part "BU-SMB-V"))
    )
    (comp (ref "R15")
      (value "50")
      (footprint "eagle-import:AXIAL-0.3")
      (libsource (lib "eagle-import") (part "RESISTORAXIAL-0.3"))
    )
    (comp (ref "R16_R15P")
      (value "BU-SMB-V")
      (footprint "eagle-import:BU-SMB-V")
      (libsource (lib "eagle-import") (part "BU-SMB-V"))
    )
    (comp (ref "R17")
      (value "10k")
      (footprint "eagle-import:AXIAL-0.3")
      (libsource (lib "eagle-import") (part "RESISTORAXIAL-0.3"))
    )
    (comp (ref "R18")
      (value "50")
      (footprint "eagle-import:AXIAL-0.3")
      (libsource (lib "eagle-import") (part "RESISTORAXIAL-0.3"))
    )
    (comp (ref "R19")
      (value "50")
      (footprint "eagle-import:AXIAL-0.3")
      (libsource (lib "eagle-import") (part "RESISTORAXIAL-0.3"))
    )
    (comp (ref "R20")
      (value "50")
      (footprint "eagle-import:AXIAL-0.3")
      (libsource (lib "eagle-import") (part "RESISTORAXIAL-0.3"))
    )
    (comp (ref "R21")
      (value "50")
      (footprint "eagle-import:AXIAL-0.3")
      (libsource (lib "eagle-import") (part "RESISTORAXIAL-0.3"))
    )
    (comp (ref "R22")
      (value "50")
      (footprint "eagle-import:AXIAL-0.3")
      (libsource (lib "eagle-import") (part "RESISTORAXIAL-0.3"))
    )
    (comp (ref "R23")
      (value "50")
      (footprint "eagle-import:AXIAL-0.3")
      (libsource (lib "eagle-import") (part "RESISTORAXIAL-0.3"))
    )
    (comp (ref "R24")
      (value "50")
      (footprint "eagle-import:AXIAL-0.3")
      (libsource (lib "eagle-import") (part "RESISTORAXIAL-0.3"))
    )
    (comp (ref "R25")
      (value "50")
      (footprint "eagle-import:AXIAL-0.3")
      (libsource (lib "eagle-import") (part "RESISTORAXIAL-0.3"))
    )
    (comp (ref "R26")
      (value "50")
      (footprint "eagle-import:AXIAL-0.3")
      (libsource (lib "eagle-import") (part "RESISTORAXIAL-0.3"))
    )
    (comp (ref "R27")
      (value "50")
      (footprint "eagle-import:AXIAL-0.3")
      (libsource (lib "eagle-import") (part "RESISTORAXIAL-0.3"))
    )
    (comp (ref "R28")
      (value "50")
      (footprint "eagle-import:AXIAL-0.3")
      (libsource (lib "eagle-import") (part "RESISTORAXIAL-0.3"))
    )
    (comp (ref "R29")
      (value "50")
      (footprint "eagle-import:AXIAL-0.3")
      (libsource (lib "eagle-import") (part "RESISTORAXIAL-0.3"))
    )
    (comp (ref "R30")
      (value "50")
      (footprint "eagle-import:AXIAL-0.3")
      (libsource (lib "eagle-import") (part "RESISTORAXIAL-0.3"))
    )
    (comp (ref "R31")
      (value "50")
      (footprint "eagle-import:AXIAL-0.3")
      (libsource (lib "eagle-import") (part "RESISTORAXIAL-0.3"))
    )
    (comp (ref "R32")
      (value "50")
      (footprint "eagle-import:AXIAL-0.3")
      (libsource (lib "eagle-import") (part "RESISTORAXIAL-0.3"))
    )
    (comp (ref "R33")
      (value "50")
      (footprint "eagle-import:AXIAL-0.3")
      (libsource (lib "eagle-import") (part "RESISTORAXIAL-0.3"))
    )
    (comp (ref "R35")
      (value "50")
      (footprint "eagle-import:AXIAL-0.3")
      (libsource (lib "eagle-import") (part "RESISTORAXIAL-0.3"))
    )
    (comp (ref "R39")
      (value "50")
      (footprint "eagle-import:AXIAL-0.3")
      (libsource (lib "eagle-import") (part "RESISTORAXIAL-0.3"))
    )
    (comp (ref "R40")
      (value "50")
      (footprint "eagle-import:AXIAL-0.3")
      (libsource (lib "eagle-import") (part "RESISTORAXIAL-0.3"))
    )
    (comp (ref "R41")
      (value "50")
      (footprint "eagle-import:AXIAL-0.3")
      (libsource (lib "eagle-import") (part "RESISTORAXIAL-0.3"))
    )
    (comp (ref "R43")
      (value "50")
      (footprint "eagle-import:AXIAL-0.3")
      (libsource (lib "eagle-import") (part "RESISTORAXIAL-0.3"))
    )
    (comp (ref "R45")
      (value "50")
      (footprint "eagle-import:AXIAL-0.3")
      (libsource (lib "eagle-import") (part "RESISTORAXIAL-0.3"))
    )
    (comp (ref "R46")
      (value "50")
      (footprint "eagle-import:AXIAL-0.3")
      (libsource (lib "eagle-import") (part "RESISTORAXIAL-0.3"))
    )
    (comp (ref "R47")
      (value "50")
      (footprint "eagle-import:AXIAL-0.3")
      (libsource (lib "eagle-import") (part "RESISTORAXIAL-0.3"))
    )
    (comp (ref "R49")
      (value "50")
      (footprint "eagle-import:AXIAL-0.3")
      (libsource (lib "eagle-import") (part "RESISTORAXIAL-0.3"))
    )
    (comp (ref "R50")
      (value "50")
      (footprint "eagle-import:AXIAL-0.3")
      (libsource (lib "eagle-import") (part "RESISTORAXIAL-0.3"))
    )
    (comp (ref "R51")
      (value "50")
      (footprint "eagle-import:AXIAL-0.3")
      (libsource (lib "eagle-import") (part "RESISTORAXIAL-0.3"))
    )
    (comp (ref "R52")
      (value "50")
      (footprint "eagle-import:AXIAL-0.3")
      (libsource (lib "eagle-import") (part "RESISTORAXIAL-0.3"))
    )
    (comp (ref "R53")
      (value "50")
      (footprint "eagle-import:AXIAL-0.3")
      (libsource (lib "eagle-import") (part "RESISTORAXIAL-0.3"))
    )
    (comp (ref "R91")
      (value "50")
      (footprint "eagle-import:AXIAL-0.3")
      (libsource (lib "eagle-import") (part "RESISTORAXIAL-0.3"))
    )
    (comp (ref "R100")
      (value "50")
      (footprint "eagle-import:AXIAL-0.3")
      (libsource (lib "eagle-import") (part "RESISTORAXIAL-0.3"))
    )
    (comp (ref "R111")
      (value "50")
      (footprint "eagle-import:AXIAL-0.3")
      (libsource (lib "eagle-import") (part "RESISTORAXIAL-0.3"))
    )
    (comp (ref "R141")
      (value "50")
      (footprint "eagle-import:AXIAL-0.3")
      (libsource (lib "eagle-import") (part "RESISTORAXIAL-0.3"))
    )
    (comp (ref "R161")
      (value "50")
      (footprint "eagle-import:AXIAL-0.3")
      (libsource (lib "eagle-import") (part "RESISTORAXIAL-0.3"))
    )
    (comp (ref "SV1")
      (value "FE20-2")
      (footprint "eagle-import:FE20-2")
      (libsource (lib "eagle-import") (part "FE20-2"))
    )
    (comp (ref "SV2")
      (value "FE20-2")
      (footprint "eagle-import:FE20-2")
      (libsource (lib "eagle-import") (part "FE20-2"))
    )
    (comp (ref "T9CLK_7N")
      (value "BU-SMB-V")
      (footprint "eagle-import:BU-SMB-V")
      (libsource (lib "eagle-import") (part "BU-SMB-V"))
    )
    (comp (ref "T10_B16N")
      (value "BU-SMB-V")
      (footprint "eagle-import:BU-SMB-V")
      (libsource (lib "eagle-import") (part "BU-SMB-V"))
    )
    (comp (ref "T12_B18N")
      (value "BU-SMB-V")
      (footprint "eagle-import:BU-SMB-V")
      (libsource (lib "eagle-import") (part "BU-SMB-V"))
    )
    (comp (ref "T13_B20N")
      (value "BU-SMB-V")
      (footprint "eagle-import:BU-SMB-V")
      (libsource (lib "eagle-import") (part "BU-SMB-V"))
    )
    (comp (ref "T14_B23P")
      (value "BU-SMB-V")
      (footprint "eagle-import:BU-SMB-V")
      (libsource (lib "eagle-import") (part "BU-SMB-V"))
    )
    (comp (ref "T15_B23N")
      (value "BU-SMB-V")
      (footprint "eagle-import:BU-SMB-V")
      (libsource (lib "eagle-import") (part "BU-SMB-V"))
    )
    (comp (ref "VSLUE")
      (value "SN74ACT244DW")
      (footprint "eagle-import:SOIC127P1030X265-20N")
      (fields (field (name "RS_PART_NUMBER") "4363169"))
      (libsource (lib "eagle-import") (part "SN74ACT244DW"))
    )
    (comp (ref "VSLUE2")
      (value "SN74ACT244DW")
      (footprint "eagle-import:SOIC127P1030X265-20N")
      (fields (field (name "RS_PART_NUMBER") "4363169"))
      (libsource (lib "eagle-import") (part "SN74ACT244DW"))
    )
    (comp (ref "VSLUE3")
      (value "SN74ACT244DW")
      (footprint "eagle-import:SOIC127P1030X265-20N")
      (fields (field (name "RS_PART_NUMBER") "4363169"))
      (libsource (lib "eagle-import") (part "SN74ACT244DW"))
    )
    (comp (ref "VSLUE4")
      (value "SN74ACT244DW")
      (footprint "eagle-import:SOIC127P1030X265-20N")
      (fields (field (name "RS_PART_NUMBER") "4363169"))
      (libsource (lib "eagle-import") (part "SN74ACT244DW"))
    )
    (comp (ref "VSLUE5")
      (value "SN74ACT244DW")
      (footprint "eagle-import:SOIC127P1030X265-20N")
      (fields (field (name "RS_PART_NUMBER") "4363169"))
      (libsource (lib "eagle-import") (part "SN74ACT244DW"))
    )
    (comp (ref "VSLUE6")
      (value "SN74ACT244DW")
      (footprint "eagle-import:SOIC127P1030X265-20N")
      (fields (field (name "RS_PART_NUMBER") "4363169"))
      (libsource (lib "eagle-import") (part "SN74ACT244DW"))
    )
    (comp (ref "VSLUE7")
      (value "SN74ACT244DW")
      (footprint "eagle-import:SOIC127P1030X265-20N")
      (fields (field (name "RS_PART_NUMBER") "4363169"))
      (libsource (lib "eagle-import") (part "SN74ACT244DW"))
    )
    (comp (ref "VSLUE8")
      (value "SN74ACT244DW")
      (footprint "eagle-import:SOIC127P1030X265-20N")
      (fields (field (name "RS_PART_NUMBER") "4363169"))
      (libsource (lib "eagle-import") (part "SN74ACT244DW"))
    )
    (comp (ref "VSLUE9")
      (value "SN74ACT244DW")
      (footprint "eagle-import:SOIC127P1030X265-20N")
      (fields (field (name "RS_PART_NUMBER") "4363169"))
      (libsource (lib "eagle-import") (part "SN74ACT244DW"))
    )
    (comp (ref "VSLUE11")
      (value "SN74ACT244DW")
      (footprint "eagle-import:SOIC127P1030X265-20N")
      (fields (field (name "RS_PART_NUMBER") "4363169"))
      (libsource (lib "eagle-import") (part "SN74ACT244DW"))
    )
  )
  (nets
    (net (code "1") (name "/-3V3_1") (class "Default")
      (node (ref "C3") (pin "1") (pinfunction "1_1") (pintype "passive"))
      (node (ref "IC1") (pin "5") (pinfunction "VOUT_5") (pintype "output"))
      (node (ref "J20") (pin "1") (pinfunction "P$1_1") (pintype "bidirectional"))
      (node (ref "R10") (pin "P$2") (pinfunction "2_P$2") (pintype "passive"))
    )
    (net (code "2") (name "/-3V3_2") (class "Default")
      (node (ref "C9") (pin "1") (pinfunction "1_1") (pintype "passive"))
      (node (ref "IC2") (pin "5") (pinfunction "VOUT_5") (pintype "output"))
      (node (ref "J21") (pin "1") (pinfunction "P$1_1") (pintype "bidirectional"))
      (node (ref "R12") (pin "P$2") (pinfunction "2_P$2") (pintype "passive"))
    )
    (net (code "3") (name "/-3V3_3") (class "Default")
      (node (ref "C13") (pin "1") (pinfunction "1_1") (pintype "passive"))
      (node (ref "IC3") (pin "5") (pinfunction "VOUT_5") (pintype "output"))
      (node (ref "J26") (pin "1") (pinfunction "P$1_1") (pintype "bidirectional"))
      (node (ref "R13") (pin "P$2") (pinfunction "2_P$2") (pintype "passive"))
    )
    (net (code "4") (name "/-3V3_4") (class "Default")
      (node (ref "C18") (pin "1") (pinfunction "1_1") (pintype "passive"))
      (node (ref "IC4") (pin "5") (pinfunction "VOUT_5") (pintype "output"))
      (node (ref "J27") (pin "1") (pinfunction "P$1_1") (pintype "bidirectional"))
      (node (ref "R14") (pin "P$2") (pinfunction "2_P$2") (pintype "passive"))
    )
    (net (code "5") (name "/-V1") (class "Default")
      (node (ref "C19") (pin "2") (pinfunction "2_2") (pintype "passive"))
      (node (ref "J20") (pin "2") (pinfunction "P$2_2") (pintype "bidirectional"))
      (node (ref "OJ9") (pin "1") (pinfunction "1_1") (pintype "bidirectional"))
      (node (ref "R1") (pin "2") (pinfunction "S_2") (pintype "passive"))
    )
    (net (code "6") (name "/-V2") (class "Default")
      (node (ref "C20") (pin "2") (pinfunction "2_2") (pintype "passive"))
      (node (ref "J21") (pin "2") (pinfunction "P$2_2") (pintype "bidirectional"))
      (node (ref "OJ10") (pin "1") (pinfunction "1_1") (pintype "bidirectional"))
      (node (ref "R2") (pin "2") (pinfunction "S_2") (pintype "passive"))
    )
    (net (code "7") (name "/-V3") (class "Default")
      (node (ref "C21") (pin "2") (pinfunction "2_2") (pintype "passive"))
      (node (ref "J26") (pin "2") (pinfunction "P$2_2") (pintype "bidirectional"))
      (node (ref "OJ11") (pin "1") (pinfunction "1_1") (pintype "bidirectional"))
      (node (ref "R3") (pin "2") (pinfunction "S_2") (pintype "passive"))
    )
    (net (code "8") (name "/-V4") (class "Default")
      (node (ref "C22") (pin "2") (pinfunction "2_2") (pintype "passive"))
      (node (ref "J27") (pin "2") (pinfunction "P$2_2") (pintype "bidirectional"))
      (node (ref "OJ12") (pin "1") (pinfunction "1_1") (pintype "bidirectional"))
      (node (ref "R7") (pin "2") (pinfunction "S_2") (pintype "passive"))
    )
    (net (code "9") (name "/3V3") (class "Default")
      (node (ref "IC1") (pin "8") (pinfunction "V+_8") (pintype "power_in"))
      (node (ref "IC2") (pin "8") (pinfunction "V+_8") (pintype "power_in"))
      (node (ref "IC3") (pin "8") (pinfunction "V+_8") (pintype "power_in"))
      (node (ref "IC4") (pin "8") (pinfunction "V+_8") (pintype "power_in"))
      (node (ref "J1") (pin "1") (pinfunction "1_1") (pintype "passive"))
      (node (ref "J12") (pin "4") (pinfunction "P$4_4") (pintype "bidirectional"))
      (node (ref "J20") (pin "4") (pinfunction "P$4_4") (pintype "bidirectional"))
      (node (ref "J21") (pin "4") (pinfunction "P$4_4") (pintype "bidirectional"))
      (node (ref "J26") (pin "4") (pinfunction "P$4_4") (pintype "bidirectional"))
      (node (ref "J27") (pin "4") (pinfunction "P$4_4") (pintype "bidirectional"))
      (node (ref "SV1") (pin "29") (pinfunction "29_29") (pintype "passive"))
      (node (ref "SV2") (pin "29") (pinfunction "29_29") (pintype "passive"))
    )
    (net (code "10") (name "/5V") (class "Default")
      (node (ref "C10") (pin "2") (pinfunction "2_2") (pintype "passive"))
      (node (ref "C2") (pin "2") (pinfunction "2_2") (pintype "passive"))
      (node (ref "C4") (pin "2") (pinfunction "2_2") (pintype "passive"))
      (node (ref "C5") (pin "2") (pinfunction "2_2") (pintype "passive"))
      (node (ref "C91") (pin "2") (pinfunction "2_2") (pintype "passive"))
      (node (ref "C93") (pin "2") (pinfunction "2_2") (pintype "passive"))
      (node (ref "C94") (pin "2") (pinfunction "2_2") (pintype "passive"))
      (node (ref "C95") (pin "2") (pinfunction "2_2") (pintype "passive"))
      (node (ref "C96") (pin "2") (pinfunction "2_2") (pintype "passive"))
      (node (ref "C97") (pin "2") (pinfunction "2_2") (pintype "passive"))
      (node (ref "J19") (pin "1-A32") (pinfunction "MS_1-A32") (pintype "passive"))
      (node (ref "J19") (pin "1-C32") (pinfunction "MS_1-C32") (pintype "passive"))
      (node (ref "J19") (pin "2-A32") (pinfunction "MS_2-A32") (pintype "passive"))
      (node (ref "J19") (pin "2-C32") (pinfunction "MS_2-C32") (pintype "passive"))
      (node (ref "J7") (pin "4") (pinfunction "P$4_4") (pintype "bidirectional"))
      (node (ref "R17") (pin "P$1") (pinfunction "1_P$1") (pintype "passive"))
      (node (ref "SV1") (pin "11") (pinfunction "11_11") (pintype "passive"))
      (node (ref "SV2") (pin "11") (pinfunction "11_11") (pintype "passive"))
      (node (ref "VSLUE") (pin "20") (pinfunction "VCC_20") (pintype "power_in"))
      (node (ref "VSLUE11") (pin "20") (pinfunction "VCC_20") (pintype "power_in"))
      (node (ref "VSLUE2") (pin "20") (pinfunction "VCC_20") (pintype "power_in"))
      (node (ref "VSLUE3") (pin "20") (pinfunction "VCC_20") (pintype "power_in"))
      (node (ref "VSLUE4") (pin "20") (pinfunction "VCC_20") (pintype "power_in"))
      (node (ref "VSLUE5") (pin "20") (pinfunction "VCC_20") (pintype "power_in"))
      (node (ref "VSLUE6") (pin "20") (pinfunction "VCC_20") (pintype "power_in"))
      (node (ref "VSLUE7") (pin "20") (pinfunction "VCC_20") (pintype "power_in"))
      (node (ref "VSLUE8") (pin "20") (pinfunction "VCC_20") (pintype "power_in"))
      (node (ref "VSLUE9") (pin "20") (pinfunction "VCC_20") (pintype "power_in"))
    )
    (net (code "11") (name "/AIN0") (class "Default")
      (node (ref "J1") (pin "24") (pinfunction "24_24") (pintype "passive"))
      (node (ref "J131") (pin "4") (pinfunction "P$4_4") (pintype "bidirectional"))
    )
    (net (code "12") (name "/AIN1") (class "Default")
      (node (ref "J1") (pin "25") (pinfunction "25_25") (pintype "passive"))
      (node (ref "J311") (pin "1") (pinfunction "P$1_1") (pintype "bidirectional"))
    )
    (net (code "13") (name "/AIN2") (class "Default")
      (node (ref "J1") (pin "22") (pinfunction "22_22") (pintype "passive"))
      (node (ref "J131") (pin "3") (pinfunction "P$3_3") (pintype "bidirectional"))
    )
    (net (code "14") (name "/AIN3") (class "Default")
      (node (ref "J1") (pin "21") (pinfunction "21_21") (pintype "passive"))
      (node (ref "J311") (pin "3") (pinfunction "P$3_3") (pintype "bidirectional"))
    )
    (net (code "15") (name "/AIN4") (class "Default")
      (node (ref "J1") (pin "23") (pinfunction "23_23") (pintype "passive"))
      (node (ref "J311") (pin "2") (pinfunction "P$2_2") (pintype "bidirectional"))
    )
    (net (code "16") (name "/AIN5") (class "Default")
      (node (ref "J1") (pin "18") (pinfunction "18_18") (pintype "passive"))
      (node (ref "J131") (pin "1") (pinfunction "P$1_1") (pintype "bidirectional"))
    )
    (net (code "17") (name "/AIN6") (class "Default")
      (node (ref "J1") (pin "19") (pinfunction "19_19") (pintype "passive"))
      (node (ref "J311") (pin "4") (pinfunction "P$4_4") (pintype "bidirectional"))
    )
    (net (code "18") (name "/AIN7") (class "Default")
      (node (ref "J1") (pin "20") (pinfunction "20_20") (pintype "passive"))
      (node (ref "J131") (pin "2") (pinfunction "P$2_2") (pintype "bidirectional"))
    )
    (net (code "19") (name "/GPIO_00_D3") (class "Default")
      (node (ref "D3_CLKOUT_3P") (pin "1") (pinfunction "1_1") (pintype "passive"))
      (node (ref "J50") (pin "2") (pinfunction "2_2") (pintype "bidirectional"))
      (node (ref "R51") (pin "P$2") (pinfunction "2_P$2") (pintype "passive"))
      (node (ref "SV1") (pin "2") (pinfunction "2_2") (pintype "passive"))
    )
    (net (code "20") (name "/GPIO_0_IN0_A8CLK") (class "Default")
      (node (ref "A8CLK_4N") (pin "1") (pinfunction "1_1") (pintype "passive"))
      (node (ref "J24") (pin "2") (pinfunction "2_2") (pintype "bidirectional"))
      (node (ref "R23") (pin "P$2") (pinfunction "2_P$2") (pintype "passive"))
      (node (ref "SV1") (pin "1") (pinfunction "1_1") (pintype "passive"))
    )
    (net (code "21") (name "/GPIO_0_IN1_B8CLK") (class "Default")
      (node (ref "B8CLK_4P") (pin "1") (pinfunction "1_1") (pintype "passive"))
      (node (ref "J23") (pin "2") (pinfunction "2_2") (pintype "bidirectional"))
      (node (ref "R22") (pin "P$2") (pinfunction "2_P$2") (pintype "passive"))
      (node (ref "SV1") (pin "3") (pinfunction "3_3") (pintype "passive"))
    )
    (net (code "22") (name "/GPIO_01_C3") (class "Default")
      (node (ref "C3_CLKOUT_3N") (pin "1") (pinfunction "1_1") (pintype "passive"))
      (node (ref "J30") (pin "2") (pinfunction "2_2") (pintype "bidirectional"))
      (node (ref "R27") (pin "P$2") (pinfunction "2_P$2") (pintype "passive"))
      (node (ref "SV1") (pin "4") (pinfunction "4_4") (pintype "passive"))
    )
    (net (code "23") (name "/GPIO_1_IN0_T9CLK") (class "Default")
      (node (ref "J6") (pin "2") (pinfunction "2_2") (pintype "bidirectional"))
      (node (ref "R6") (pin "P$2") (pinfunction "2_P$2") (pintype "passive"))
      (node (ref "SV2") (pin "1") (pinfunction "1_1") (pintype "passive"))
      (node (ref "T9CLK_7N") (pin "1") (pinfunction "1_1") (pintype "passive"))
    )
    (net (code "24") (name "/GPIO_1_IN1_R9CLK") (class "Default")
      (node (ref "J5") (pin "2") (pinfunction "2_2") (pintype "bidirectional"))
      (node (ref "R5") (pin "P$2") (pinfunction "2_P$2") (pintype "passive"))
      (node (ref "R9CLK_7P") (pin "1") (pinfunction "1_1") (pintype "passive"))
      (node (ref "SV2") (pin "3") (pinfunction "3_3") (pintype "passive"))
    )
    (net (code "25") (name "/GPIO_02_A2") (class "Default")
      (node (ref "A2_T2N") (pin "1") (pinfunction "1_1") (pintype "passive"))
      (node (ref "J22") (pin "2") (pinfunction "2_2") (pintype "bidirectional"))
      (node (ref "R20") (pin "P$2") (pinfunction "2_P$2") (pintype "passive"))
      (node (ref "SV1") (pin "5") (pinfunction "5_5") (pintype "passive"))
    )
    (net (code "26") (name "/GPIO_2_IN0_E15CLK") (class "Default")
      (node (ref "E15CLK_2P") (pin "1") (pinfunction "1_1") (pintype "passive"))
      (node (ref "J1") (pin "2") (pinfunction "2_2") (pintype "passive"))
      (node (ref "J16") (pin "2") (pinfunction "2_2") (pintype "bidirectional"))
      (node (ref "R19") (pin "P$2") (pinfunction "2_P$2") (pintype "passive"))
    )
    (net (code "27") (name "/GPIO_2_IN1_E16CLK") (class "Default")
      (node (ref "E16CLK_2N") (pin "1") (pinfunction "1_1") (pintype "passive"))
      (node (ref "J1") (pin "3") (pinfunction "3_3") (pintype "passive"))
      (node (ref "J15") (pin "2") (pinfunction "2_2") (pintype "bidirectional"))
      (node (ref "R18") (pin "P$2") (pinfunction "2_P$2") (pintype "passive"))
    )
    (net (code "28") (name "/GPIO_2_IN2_M16CLK") (class "Default")
      (node (ref "J1") (pin "4") (pinfunction "4_4") (pintype "passive"))
      (node (ref "J141") (pin "2") (pinfunction "2_2") (pintype "bidirectional"))
      (node (ref "M16CLK_3N") (pin "1") (pinfunction "1_1") (pintype "passive"))
      (node (ref "R15") (pin "P$2") (pinfunction "2_P$2") (pintype "passive"))
    )
    (net (code "29") (name "/GPIO_03_A3") (class "Default")
      (node (ref "A3_T2P") (pin "1") (pinfunction "1_1") (pintype "passive"))
      (node (ref "J25") (pin "2") (pinfunction "2_2") (pintype "bidirectional"))
      (node (ref "R25") (pin "P$2") (pinfunction "2_P$2") (pintype "passive"))
      (node (ref "SV1") (pin "6") (pinfunction "6_6") (pintype "passive"))
    )
    (net (code "30") (name "/GPIO_04_B3") (class "Default")
      (node (ref "OJ96") (pin "1") (pinfunction "1_1") (pintype "bidirectional"))
      (node (ref "SV1") (pin "7") (pinfunction "7_7") (pintype "passive"))
      (node (ref "VSLUE11") (pin "6") (pinfunction "1A3_6") (pintype "input"))
      (node (ref "VSLUE11") (pin "8") (pinfunction "1A4_8") (pintype "input"))
    )
    (net (code "31") (name "/GPIO_05_B4") (class "Default")
      (node (ref "OJ94") (pin "1") (pinfunction "1_1") (pintype "bidirectional"))
      (node (ref "SV1") (pin "8") (pinfunction "8_8") (pintype "passive"))
      (node (ref "VSLUE11") (pin "11") (pinfunction "2A1_11") (pintype "input"))
      (node (ref "VSLUE11") (pin "13") (pinfunction "2A2_13") (pintype "input"))
    )
    (net (code "32") (name "/GPIO_06_A4") (class "Default")
      (node (ref "OJ93") (pin "1") (pinfunction "1_1") (pintype "bidirectional"))
      (node (ref "SV1") (pin "9") (pinfunction "9_9") (pintype "passive"))
      (node (ref "VSLUE11") (pin "15") (pinfunction "2A3_15") (pintype "input"))
      (node (ref "VSLUE11") (pin "17") (pinfunction "2A4_17") (pintype "input"))
    )
    (net (code "33") (name "/GPIO_07_B5") (class "Default")
      (node (ref "OJ71") (pin "1") (pinfunction "1_1") (pintype "bidirectional"))
      (node (ref "SV1") (pin "10") (pinfunction "10_10") (pintype "passive"))
      (node (ref "VSLUE8") (pin "2") (pinfunction "1A1_2") (pintype "input"))
      (node (ref "VSLUE8") (pin "4") (pinfunction "1A2_4") (pintype "input"))
    )
    (net (code "34") (name "/GPIO_08_A5") (class "Default")
      (node (ref "OJ72") (pin "1") (pinfunction "1_1") (pintype "bidirectional"))
      (node (ref "SV1") (pin "13") (pinfunction "13_13") (pintype "passive"))
      (node (ref "VSLUE8") (pin "6") (pinfunction "1A3_6") (pintype "input"))
      (node (ref "VSLUE8") (pin "8") (pinfunction "1A4_8") (pintype "input"))
    )
    (net (code "35") (name "/GPIO_09_D5") (class "Default")
      (node (ref "OJ69") (pin "1") (pinfunction "1_1") (pintype "bidirectional"))
      (node (ref "SV1") (pin "14") (pinfunction "14_14") (pintype "passive"))
      (node (ref "VSLUE8") (pin "15") (pinfunction "2A3_15") (pintype "input"))
      (node (ref "VSLUE8") (pin "17") (pinfunction "2A4_17") (pintype "input"))
    )
    (net (code "36") (name "/GPIO_010_B6") (class "Default")
      (node (ref "OJ47") (pin "1") (pinfunction "1_1") (pintype "bidirectional"))
      (node (ref "SV1") (pin "15") (pinfunction "15_15") (pintype "passive"))
      (node (ref "VSLUE5") (pin "2") (pinfunction "1A1_2") (pintype "input"))
      (node (ref "VSLUE5") (pin "4") (pinfunction "1A2_4") (pintype "input"))
    )
    (net (code "37") (name "/GPIO_10_F13") (class "Default")
      (node (ref "J3") (pin "2") (pinfunction "P$2_2") (pintype "bidirectional"))
      (node (ref "SV2") (pin "2") (pinfunction "2_2") (pintype "passive"))
    )
    (net (code "38") (name "/GPIO_011_A6") (class "Default")
      (node (ref "OJ48") (pin "1") (pinfunction "1_1") (pintype "bidirectional"))
      (node (ref "SV1") (pin "16") (pinfunction "16_16") (pintype "passive"))
      (node (ref "VSLUE5") (pin "6") (pinfunction "1A3_6") (pintype "input"))
      (node (ref "VSLUE5") (pin "8") (pinfunction "1A4_8") (pintype "input"))
    )
    (net (code "39") (name "/GPIO_11_T15") (class "Default")
      (node (ref "J40") (pin "2") (pinfunction "2_2") (pintype "bidirectional"))
      (node (ref "OJ11") (pin "2") (pinfunction "2_2") (pintype "bidirectional"))
      (node (ref "R39") (pin "P$2") (pinfunction "2_P$2") (pintype "passive"))
      (node (ref "SV2") (pin "4") (pinfunction "4_4") (pintype "passive"))
      (node (ref "T15_B23N") (pin "1") (pinfunction "1_1") (pintype "passive"))
    )
    (net (code "40") (name "/GPIO_012_B7") (class "Default")
      (node (ref "B7_T9P") (pin "1") (pinfunction "1_1") (pintype "passive"))
      (node (ref "J49") (pin "2") (pinfunction "2_2") (pintype "bidirectional"))
      (node (ref "R50") (pin "P$2") (pinfunction "2_P$2") (pintype "passive"))
      (node (ref "SV1") (pin "17") (pinfunction "17_17") (pintype "passive"))
    )
    (net (code "41") (name "/GPIO_12_T14") (class "Default")
      (node (ref "J4") (pin "2") (pinfunction "2_2") (pintype "bidirectional"))
      (node (ref "R4") (pin "P$2") (pinfunction "2_P$2") (pintype "passive"))
      (node (ref "SV2") (pin "5") (pinfunction "5_5") (pintype "passive"))
      (node (ref "T14_B23P") (pin "1") (pinfunction "1_1") (pintype "passive"))
    )
    (net (code "42") (name "/GPIO_013_D6") (class "Default")
      (node (ref "OJ55") (pin "1") (pinfunction "1_1") (pintype "bidirectional"))
      (node (ref "SV1") (pin "18") (pinfunction "18_18") (pintype "passive"))
      (node (ref "VSLUE6") (pin "2") (pinfunction "1A1_2") (pintype "input"))
      (node (ref "VSLUE6") (pin "4") (pinfunction "1A2_4") (pintype "input"))
    )
    (net (code "43") (name "/GPIO_13_T13") (class "Default")
      (node (ref "J38") (pin "2") (pinfunction "2_2") (pintype "bidirectional"))
      (node (ref "R32") (pin "P$2") (pinfunction "2_P$2") (pintype "passive"))
      (node (ref "SV2") (pin "6") (pinfunction "6_6") (pintype "passive"))
      (node (ref "T13_B20N") (pin "1") (pinfunction "1_1") (pintype "passive"))
    )
    (net (code "44") (name "/GPIO_014_A7") (class "Default")
      (node (ref "A7_T9N") (pin "1") (pinfunction "1_1") (pintype "passive"))
      (node (ref "J35") (pin "2") (pinfunction "2_2") (pintype "bidirectional"))
      (node (ref "OJ9") (pin "2") (pinfunction "2_2") (pintype "bidirectional"))
      (node (ref "R33") (pin "P$2") (pinfunction "2_P$2") (pintype "passive"))
      (node (ref "SV1") (pin "19") (pinfunction "19_19") (pintype "passive"))
    )
    (net (code "45") (name "/GPIO_14_R13") (class "Default")
      (node (ref "J17") (pin "2") (pinfunction "2_2") (pintype "bidirectional"))
      (node (ref "R13_B20P") (pin "1") (pinfunction "1_1") (pintype "passive"))
      (node (ref "R161") (pin "P$2") (pinfunction "2_P$2") (pintype "passive"))
      (node (ref "SV2") (pin "7") (pinfunction "7_7") (pintype "passive"))
    )
    (net (code "46") (name "/GPIO_015_C6") (class "Default")
      (node (ref "OJ56") (pin "1") (pinfunction "1_1") (pintype "bidirectional"))
      (node (ref "SV1") (pin "20") (pinfunction "20_20") (pintype "passive"))
      (node (ref "VSLUE6") (pin "6") (pinfunction "1A3_6") (pintype "input"))
      (node (ref "VSLUE6") (pin "8") (pinfunction "1A4_8") (pintype "input"))
    )
    (net (code "47") (name "/GPIO_15_T12") (class "Default")
      (node (ref "J9") (pin "2") (pinfunction "2_2") (pintype "bidirectional"))
      (node (ref "R100") (pin "P$2") (pinfunction "2_P$2") (pintype "passive"))
      (node (ref "SV2") (pin "8") (pinfunction "8_8") (pintype "passive"))
      (node (ref "T12_B18N") (pin "1") (pinfunction "1_1") (pintype "passive"))
    )
    (net (code "48") (name "/GPIO_016_C8") (class "Default")
      (node (ref "OJ53") (pin "1") (pinfunction "1_1") (pintype "bidirectional"))
      (node (ref "SV1") (pin "21") (pinfunction "21_21") (pintype "passive"))
      (node (ref "VSLUE6") (pin "15") (pinfunction "2A3_15") (pintype "input"))
      (node (ref "VSLUE6") (pin "17") (pinfunction "2A4_17") (pintype "input"))
    )
    (net (code "49") (name "/GPIO_16_R12") (class "Default")
      (node (ref "J10") (pin "2") (pinfunction "2_2") (pintype "bidirectional"))
      (node (ref "R111") (pin "P$2") (pinfunction "2_P$2") (pintype "passive"))
      (node (ref "R12_B18P") (pin "1") (pinfunction "1_1") (pintype "passive"))
      (node (ref "SV2") (pin "9") (pinfunction "9_9") (pintype "passive"))
    )
    (net (code "50") (name "/GPIO_017_E6") (class "Default")
      (node (ref "OJ54") (pin "1") (pinfunction "1_1") (pintype "bidirectional"))
      (node (ref "SV1") (pin "22") (pinfunction "22_22") (pintype "passive"))
      (node (ref "VSLUE6") (pin "11") (pinfunction "2A1_11") (pintype "input"))
      (node (ref "VSLUE6") (pin "13") (pinfunction "2A2_13") (pintype "input"))
    )
    (net (code "51") (name "/GPIO_17_T11") (class "Default")
      (node (ref "J3") (pin "3") (pinfunction "P$3_3") (pintype "bidirectional"))
      (node (ref "SV2") (pin "10") (pinfunction "10_10") (pintype "passive"))
    )
    (net (code "52") (name "/GPIO_018_E7") (class "Default")
      (node (ref "OJ64") (pin "1") (pinfunction "1_1") (pintype "bidirectional"))
      (node (ref "SV1") (pin "23") (pinfunction "23_23") (pintype "passive"))
      (node (ref "VSLUE7") (pin "6") (pinfunction "1A3_6") (pintype "input"))
      (node (ref "VSLUE7") (pin "8") (pinfunction "1A4_8") (pintype "input"))
    )
    (net (code "53") (name "/GPIO_18_T10") (class "Default")
      (node (ref "J51") (pin "2") (pinfunction "2_2") (pintype "bidirectional"))
      (node (ref "R53") (pin "P$2") (pinfunction "2_P$2") (pintype "passive"))
      (node (ref "SV2") (pin "13") (pinfunction "13_13") (pintype "passive"))
      (node (ref "T10_B16N") (pin "1") (pinfunction "1_1") (pintype "passive"))
    )
    (net (code "54") (name "/GPIO_019_D8") (class "Default")
      (node (ref "OJ21") (pin "1") (pinfunction "1_1") (pintype "bidirectional"))
      (node (ref "SV1") (pin "24") (pinfunction "24_24") (pintype "passive"))
      (node (ref "VSLUE2") (pin "15") (pinfunction "2A3_15") (pintype "input"))
      (node (ref "VSLUE2") (pin "17") (pinfunction "2A4_17") (pintype "input"))
    )
    (net (code "55") (name "/GPIO_19_R11") (class "Default")
      (node (ref "J3") (pin "1") (pinfunction "P$1_1") (pintype "bidirectional"))
      (node (ref "SV2") (pin "14") (pinfunction "14_14") (pintype "passive"))
    )
    (net (code "56") (name "/GPIO_20_A14") (class "Default")
      (node (ref "A14_CLKOUT_2N") (pin "1") (pinfunction "1_1") (pintype "passive"))
      (node (ref "J1") (pin "5") (pinfunction "5_5") (pintype "passive"))
      (node (ref "J31") (pin "2") (pinfunction "2_2") (pintype "bidirectional"))
      (node (ref "R29") (pin "P$2") (pinfunction "2_P$2") (pintype "passive"))
    )
    (net (code "57") (name "/GPIO_020_E8") (class "Default")
      (node (ref "E8_T10N") (pin "1") (pinfunction "1_1") (pintype "passive"))
      (node (ref "J41") (pin "2") (pinfunction "2_2") (pintype "bidirectional"))
      (node (ref "OJ12") (pin "2") (pinfunction "2_2") (pintype "bidirectional"))
      (node (ref "R40") (pin "P$2") (pinfunction "2_P$2") (pintype "passive"))
      (node (ref "SV1") (pin "25") (pinfunction "25_25") (pintype "passive"))
    )
    (net (code "58") (name "/GPIO_21_B16") (class "Default")
      (node (ref "J1") (pin "6") (pinfunction "6_6") (pintype "passive"))
      (node (ref "OJ22") (pin "1") (pinfunction "1_1") (pintype "bidirectional"))
      (node (ref "VSLUE2") (pin "11") (pinfunction "2A1_11") (pintype "input"))
      (node (ref "VSLUE2") (pin "13") (pinfunction "2A2_13") (pintype "input"))
    )
    (net (code "59") (name "/GPIO_021_F8") (class "Default")
      (node (ref "F8_T10P") (pin "1") (pinfunction "1_1") (pintype "passive"))
      (node (ref "J18") (pin "2") (pinfunction "2_2") (pintype "bidirectional"))
      (node (ref "R21") (pin "P$2") (pinfunction "2_P$2") (pintype "passive"))
      (node (ref "SV1") (pin "26") (pinfunction "26_26") (pintype "passive"))
    )
    (net (code "60") (name "/GPIO_22_C14") (class "Default")
      (node (ref "J1") (pin "7") (pinfunction "7_7") (pintype "passive"))
      (node (ref "OJ32") (pin "1") (pinfunction "1_1") (pintype "bidirectional"))
      (node (ref "VSLUE3") (pin "6") (pinfunction "1A3_6") (pintype "input"))
      (node (ref "VSLUE3") (pin "8") (pinfunction "1A4_8") (pintype "input"))
    )
    (net (code "61") (name "/GPIO_022_F9") (class "Default")
      (node (ref "OJ62") (pin "1") (pinfunction "1_1") (pintype "bidirectional"))
      (node (ref "SV1") (pin "27") (pinfunction "27_27") (pintype "passive"))
      (node (ref "VSLUE7") (pin "11") (pinfunction "2A1_11") (pintype "input"))
      (node (ref "VSLUE7") (pin "13") (pinfunction "2A2_13") (pintype "input"))
    )
    (net (code "62") (name "/GPIO_23_C16") (class "Default")
      (node (ref "J1") (pin "8") (pinfunction "8_8") (pintype "passive"))
      (node (ref "OJ63") (pin "1") (pinfunction "1_1") (pintype "bidirectional"))
      (node (ref "VSLUE7") (pin "2") (pinfunction "1A1_2") (pintype "input"))
      (node (ref "VSLUE7") (pin "4") (pinfunction "1A2_4") (pintype "input"))
    )
    (net (code "63") (name "/GPIO_023_E9") (class "Default")
      (node (ref "OJ24") (pin "1") (pinfunction "1_1") (pintype "bidirectional"))
      (node (ref "SV1") (pin "28") (pinfunction "28_28") (pintype "passive"))
      (node (ref "VSLUE2") (pin "6") (pinfunction "1A3_6") (pintype "input"))
      (node (ref "VSLUE2") (pin "8") (pinfunction "1A4_8") (pintype "input"))
    )
    (net (code "64") (name "/GPIO_024_C9") (class "Default")
      (node (ref "C9_T15N") (pin "1") (pinfunction "1_1") (pintype "passive"))
      (node (ref "J8") (pin "2") (pinfunction "2_2") (pintype "bidirectional"))
      (node (ref "R91") (pin "P$2") (pinfunction "2_P$2") (pintype "passive"))
      (node (ref "SV1") (pin "31") (pinfunction "31_31") (pintype "passive"))
    )
    (net (code "65") (name "/GPIO_24_C15") (class "Default")
      (node (ref "J1") (pin "9") (pinfunction "9_9") (pintype "passive"))
      (node (ref "OJ31") (pin "1") (pinfunction "1_1") (pintype "bidirectional"))
      (node (ref "VSLUE3") (pin "2") (pinfunction "1A1_2") (pintype "input"))
      (node (ref "VSLUE3") (pin "4") (pinfunction "1A2_4") (pintype "input"))
    )
    (net (code "66") (name "/GPIO_025_D9") (class "Default")
      (node (ref "D9_T15P") (pin "1") (pinfunction "1_1") (pintype "passive"))
      (node (ref "J11") (pin "2") (pinfunction "2_2") (pintype "bidirectional"))
      (node (ref "R141") (pin "P$2") (pinfunction "2_P$2") (pintype "passive"))
      (node (ref "SV1") (pin "32") (pinfunction "32_32") (pintype "passive"))
    )
    (net (code "67") (name "/GPIO_25_D16") (class "Default")
      (node (ref "J1") (pin "10") (pinfunction "10_10") (pintype "passive"))
      (node (ref "OJ39") (pin "1") (pinfunction "1_1") (pintype "bidirectional"))
      (node (ref "VSLUE4") (pin "2") (pinfunction "1A1_2") (pintype "input"))
      (node (ref "VSLUE4") (pin "4") (pinfunction "1A2_4") (pintype "input"))
    )
    (net (code "68") (name "/GPIO_26_D15") (class "Default")
      (node (ref "J1") (pin "11") (pinfunction "11_11") (pintype "passive"))
      (node (ref "OJ29") (pin "1") (pinfunction "1_1") (pintype "bidirectional"))
      (node (ref "VSLUE3") (pin "15") (pinfunction "2A3_15") (pintype "input"))
      (node (ref "VSLUE3") (pin "17") (pinfunction "2A4_17") (pintype "input"))
    )
    (net (code "69") (name "/GPIO_026_E11") (class "Default")
      (node (ref "OJ79") (pin "1") (pinfunction "1_1") (pintype "bidirectional"))
      (node (ref "SV1") (pin "33") (pinfunction "33_33") (pintype "passive"))
      (node (ref "VSLUE9") (pin "2") (pinfunction "1A1_2") (pintype "input"))
      (node (ref "VSLUE9") (pin "4") (pinfunction "1A2_4") (pintype "input"))
    )
    (net (code "70") (name "/GPIO_27_D14") (class "Default")
      (node (ref "J1") (pin "12") (pinfunction "12_12") (pintype "passive"))
      (node (ref "OJ40") (pin "1") (pinfunction "1_1") (pintype "bidirectional"))
      (node (ref "VSLUE4") (pin "6") (pinfunction "1A3_6") (pintype "input"))
      (node (ref "VSLUE4") (pin "8") (pinfunction "1A4_8") (pintype "input"))
    )
    (net (code "71") (name "/GPIO_027_E10") (class "Default")
      (node (ref "OJ5") (pin "1") (pinfunction "1_1") (pintype "bidirectional"))
      (node (ref "SV1") (pin "34") (pinfunction "34_34") (pintype "passive"))
      (node (ref "VSLUE") (pin "15") (pinfunction "2A3_15") (pintype "input"))
      (node (ref "VSLUE") (pin "17") (pinfunction "2A4_17") (pintype "input"))
    )
    (net (code "72") (name "/GPIO_028_C11") (class "Default")
      (node (ref "OJ78") (pin "1") (pinfunction "1_1") (pintype "bidirectional"))
      (node (ref "SV1") (pin "35") (pinfunction "35_35") (pintype "passive"))
      (node (ref "VSLUE9") (pin "11") (pinfunction "2A1_11") (pintype "input"))
      (node (ref "VSLUE9") (pin "13") (pinfunction "2A2_13") (pintype "input"))
    )
    (net (code "73") (name "/GPIO_28_F15") (class "Default")
      (node (ref "J1") (pin "13") (pinfunction "13_13") (pintype "passive"))
      (node (ref "OJ37") (pin "1") (pinfunction "1_1") (pintype "bidirectional"))
      (node (ref "VSLUE4") (pin "15") (pinfunction "2A3_15") (pintype "input"))
      (node (ref "VSLUE4") (pin "17") (pinfunction "2A4_17") (pintype "input"))
    )
    (net (code "74") (name "/GPIO_029_B11") (class "Default")
      (node (ref "OJ6") (pin "1") (pinfunction "1_1") (pintype "bidirectional"))
      (node (ref "SV1") (pin "36") (pinfunction "36_36") (pintype "passive"))
      (node (ref "VSLUE") (pin "11") (pinfunction "2A1_11") (pintype "input"))
      (node (ref "VSLUE") (pin "13") (pinfunction "2A2_13") (pintype "input"))
    )
    (net (code "75") (name "/GPIO_29_F16") (class "Default")
      (node (ref "J1") (pin "14") (pinfunction "14_14") (pintype "passive"))
      (node (ref "OJ38") (pin "1") (pinfunction "1_1") (pintype "bidirectional"))
      (node (ref "VSLUE4") (pin "11") (pinfunction "2A1_11") (pintype "input"))
      (node (ref "VSLUE4") (pin "13") (pinfunction "2A2_13") (pintype "input"))
    )
    (net (code "76") (name "/GPIO_030_A12") (class "Default")
      (node (ref "A12_T21N") (pin "1") (pinfunction "1_1") (pintype "passive"))
      (node (ref "J36") (pin "2") (pinfunction "2_2") (pintype "bidirectional"))
      (node (ref "OJ10") (pin "2") (pinfunction "2_2") (pintype "bidirectional"))
      (node (ref "R9") (pin "P$2") (pinfunction "2_P$2") (pintype "passive"))
      (node (ref "SV1") (pin "37") (pinfunction "37_37") (pintype "passive"))
    )
    (net (code "77") (name "/GPIO_031_D11") (class "Default")
      (node (ref "OJ8") (pin "1") (pinfunction "1_1") (pintype "bidirectional"))
      (node (ref "SV1") (pin "38") (pinfunction "38_38") (pintype "passive"))
      (node (ref "VSLUE") (pin "6") (pinfunction "1A3_6") (pintype "input"))
      (node (ref "VSLUE") (pin "8") (pinfunction "1A4_8") (pintype "input"))
    )
    (net (code "78") (name "/GPIO_032_D12") (class "Default")
      (node (ref "OJ95") (pin "1") (pinfunction "1_1") (pintype "bidirectional"))
      (node (ref "SV1") (pin "39") (pinfunction "39_39") (pintype "passive"))
      (node (ref "VSLUE11") (pin "2") (pinfunction "1A1_2") (pintype "input"))
      (node (ref "VSLUE11") (pin "4") (pinfunction "1A2_4") (pintype "input"))
    )
    (net (code "79") (name "/GPIO_033_B12") (class "Default")
      (node (ref "B12_T21P") (pin "1") (pinfunction "1_1") (pintype "passive"))
      (node (ref "J37") (pin "2") (pinfunction "2_2") (pintype "bidirectional"))
      (node (ref "R11") (pin "P$2") (pinfunction "2_P$2") (pintype "passive"))
      (node (ref "SV1") (pin "40") (pinfunction "40_40") (pintype "passive"))
    )
    (net (code "80") (name "/GPIO_110_P11") (class "Default")
      (node (ref "OJ80") (pin "1") (pinfunction "1_1") (pintype "bidirectional"))
      (node (ref "SV2") (pin "15") (pinfunction "15_15") (pintype "passive"))
      (node (ref "VSLUE9") (pin "6") (pinfunction "1A3_6") (pintype "input"))
      (node (ref "VSLUE9") (pin "8") (pinfunction "1A4_8") (pintype "input"))
    )
    (net (code "81") (name "/GPIO_111_R10") (class "Default")
      (node (ref "J48") (pin "2") (pinfunction "2_2") (pintype "bidirectional"))
      (node (ref "R10_B16P") (pin "1") (pinfunction "1_1") (pintype "passive"))
      (node (ref "R49") (pin "P$2") (pinfunction "2_P$2") (pintype "passive"))
      (node (ref "SV2") (pin "16") (pinfunction "16_16") (pintype "passive"))
    )
    (net (code "82") (name "/GPIO_112_N12") (class "Default")
      (node (ref "OJ23") (pin "1") (pinfunction "1_1") (pintype "bidirectional"))
      (node (ref "SV2") (pin "17") (pinfunction "17_17") (pintype "passive"))
      (node (ref "VSLUE2") (pin "2") (pinfunction "1A1_2") (pintype "input"))
      (node (ref "VSLUE2") (pin "4") (pinfunction "1A2_4") (pintype "input"))
    )
    (net (code "83") (name "/GPIO_113_P9") (class "Default")
      (node (ref "OJ45") (pin "1") (pinfunction "1_1") (pintype "bidirectional"))
      (node (ref "SV2") (pin "18") (pinfunction "18_18") (pintype "passive"))
      (node (ref "VSLUE5") (pin "15") (pinfunction "2A3_15") (pintype "input"))
      (node (ref "VSLUE5") (pin "17") (pinfunction "2A4_17") (pintype "input"))
    )
    (net (code "84") (name "/GPIO_114_N9") (class "Default")
      (node (ref "J3") (pin "4") (pinfunction "P$4_4") (pintype "bidirectional"))
      (node (ref "LED1") (pin "A") (pinfunction "A_A") (pintype "passive"))
      (node (ref "R17") (pin "P$2") (pinfunction "2_P$2") (pintype "passive"))
      (node (ref "SV2") (pin "19") (pinfunction "19_19") (pintype "passive"))
      (node (ref "VSLUE") (pin "1") (pinfunction "~{1OE}_1") (pintype "input"))
      (node (ref "VSLUE") (pin "19") (pinfunction "~{2OE}_19") (pintype "input"))
      (node (ref "VSLUE11") (pin "1") (pinfunction "~{1OE}_1") (pintype "input"))
      (node (ref "VSLUE11") (pin "19") (pinfunction "~{2OE}_19") (pintype "input"))
      (node (ref "VSLUE2") (pin "1") (pinfunction "~{1OE}_1") (pintype "input"))
      (node (ref "VSLUE2") (pin "19") (pinfunction "~{2OE}_19") (pintype "input"))
      (node (ref "VSLUE3") (pin "1") (pinfunction "~{1OE}_1") (pintype "input"))
      (node (ref "VSLUE3") (pin "19") (pinfunction "~{2OE}_19") (pintype "input"))
      (node (ref "VSLUE4") (pin "1") (pinfunction "~{1OE}_1") (pintype "input"))
      (node (ref "VSLUE4") (pin "19") (pinfunction "~{2OE}_19") (pintype "input"))
      (node (ref "VSLUE5") (pin "1") (pinfunction "~{1OE}_1") (pintype "input"))
      (node (ref "VSLUE5") (pin "19") (pinfunction "~{2OE}_19") (pintype "input"))
      (node (ref "VSLUE6") (pin "1") (pinfunction "~{1OE}_1") (pintype "input"))
      (node (ref "VSLUE6") (pin "19") (pinfunction "~{2OE}_19") (pintype "input"))
      (node (ref "VSLUE7") (pin "1") (pinfunction "~{1OE}_1") (pintype "input"))
      (node (ref "VSLUE7") (pin "19") (pinfunction "~{2OE}_19") (pintype "input"))
      (node (ref "VSLUE8") (pin "1") (pinfunction "~{1OE}_1") (pintype "input"))
      (node (ref "VSLUE8") (pin "19") (pinfunction "~{2OE}_19") (pintype "input"))
      (node (ref "VSLUE9") (pin "1") (pinfunction "~{1OE}_1") (pintype "input"))
      (node (ref "VSLUE9") (pin "19") (pinfunction "~{2OE}_19") (pintype "input"))
    )
    (net (code "85") (name "/GPIO_115_N11") (class "Default")
      (node (ref "OJ46") (pin "1") (pinfunction "1_1") (pintype "bidirectional"))
      (node (ref "SV2") (pin "20") (pinfunction "20_20") (pintype "passive"))
      (node (ref "VSLUE5") (pin "11") (pinfunction "2A1_11") (pintype "input"))
      (node (ref "VSLUE5") (pin "13") (pinfunction "2A2_13") (pintype "input"))
    )
    (net (code "86") (name "/GPIO_116_L16") (class "Default")
      (node (ref "J32") (pin "2") (pinfunction "2_2") (pintype "bidirectional"))
      (node (ref "L16_R11N") (pin "1") (pinfunction "1_1") (pintype "passive"))
      (node (ref "R28") (pin "P$2") (pinfunction "2_P$2") (pintype "passive"))
      (node (ref "SV2") (pin "21") (pinfunction "21_21") (pintype "passive"))
    )
    (net (code "87") (name "/GPIO_117_K16") (class "Default")
      (node (ref "J33") (pin "2") (pinfunction "2_2") (pintype "bidirectional"))
      (node (ref "K16_R10N") (pin "1") (pinfunction "1_1") (pintype "passive"))
      (node (ref "R30") (pin "P$2") (pinfunction "2_P$2") (pintype "passive"))
      (node (ref "SV2") (pin "22") (pinfunction "22_22") (pintype "passive"))
    )
    (net (code "88") (name "/GPIO_118_R16") (class "Default")
      (node (ref "J34") (pin "2") (pinfunction "2_2") (pintype "bidirectional"))
      (node (ref "R16_R15P") (pin "1") (pinfunction "1_1") (pintype "passive"))
      (node (ref "R31") (pin "P$2") (pinfunction "2_P$2") (pintype "passive"))
      (node (ref "SV2") (pin "23") (pinfunction "23_23") (pintype "passive"))
    )
    (net (code "89") (name "/GPIO_119_L15") (class "Default")
      (node (ref "J43") (pin "2") (pinfunction "2_2") (pintype "bidirectional"))
      (node (ref "L15_R11P") (pin "1") (pinfunction "1_1") (pintype "passive"))
      (node (ref "R43") (pin "P$2") (pinfunction "2_P$2") (pintype "passive"))
      (node (ref "SV2") (pin "24") (pinfunction "24_24") (pintype "passive"))
    )
    (net (code "90") (name "/GPIO_120_P15") (class "Default")
      (node (ref "OJ61") (pin "1") (pinfunction "1_1") (pintype "bidirectional"))
      (node (ref "SV2") (pin "25") (pinfunction "25_25") (pintype "passive"))
      (node (ref "VSLUE7") (pin "15") (pinfunction "2A3_15") (pintype "input"))
      (node (ref "VSLUE7") (pin "17") (pinfunction "2A4_17") (pintype "input"))
    )
    (net (code "91") (name "/GPIO_121_P16") (class "Default")
      (node (ref "J42") (pin "2") (pinfunction "2_2") (pintype "bidirectional"))
      (node (ref "P16_R15N") (pin "1") (pinfunction "1_1") (pintype "passive"))
      (node (ref "R41") (pin "P$2") (pinfunction "2_P$2") (pintype "passive"))
      (node (ref "SV2") (pin "26") (pinfunction "26_26") (pintype "passive"))
    )
    (net (code "92") (name "/GPIO_122_R14") (class "Default")
      (node (ref "J53") (pin "2") (pinfunction "2_2") (pintype "bidirectional"))
      (node (ref "R14_CLKOUT_4N") (pin "1") (pinfunction "1_1") (pintype "passive"))
      (node (ref "R46") (pin "P$2") (pinfunction "2_P$2") (pintype "passive"))
      (node (ref "SV2") (pin "27") (pinfunction "27_27") (pintype "passive"))
    )
    (net (code "93") (name "/GPIO_123_N16") (class "Default")
      (node (ref "J55") (pin "2") (pinfunction "2_2") (pintype "bidirectional"))
      (node (ref "N16_R13N") (pin "1") (pinfunction "1_1") (pintype "passive"))
      (node (ref "R52") (pin "P$2") (pinfunction "2_P$2") (pintype "passive"))
      (node (ref "SV2") (pin "28") (pinfunction "28_28") (pintype "passive"))
    )
    (net (code "94") (name "/GPIO_124_N15") (class "Default")
      (node (ref "J54") (pin "2") (pinfunction "2_2") (pintype "bidirectional"))
      (node (ref "N15_R13P") (pin "1") (pinfunction "1_1") (pintype "passive"))
      (node (ref "R47") (pin "P$2") (pinfunction "2_P$2") (pintype "passive"))
      (node (ref "SV2") (pin "31") (pinfunction "31_31") (pintype "passive"))
    )
    (net (code "95") (name "/GPIO_125_P14") (class "Default")
      (node (ref "J52") (pin "2") (pinfunction "2_2") (pintype "bidirectional"))
      (node (ref "P14_CLKOUT_4P") (pin "1") (pinfunction "1_1") (pintype "passive"))
      (node (ref "R45") (pin "P$2") (pinfunction "2_P$2") (pintype "passive"))
      (node (ref "SV2") (pin "32") (pinfunction "32_32") (pintype "passive"))
    )
    (net (code "96") (name "/GPIO_126_L14") (class "Default")
      (node (ref "J7") (pin "2") (pinfunction "P$2_2") (pintype "bidirectional"))
      (node (ref "SV2") (pin "33") (pinfunction "33_33") (pintype "passive"))
    )
    (net (code "97") (name "/GPIO_127_N14") (class "Default")
      (node (ref "OJ70") (pin "1") (pinfunction "1_1") (pintype "bidirectional"))
      (node (ref "SV2") (pin "34") (pinfunction "34_34") (pintype "passive"))
      (node (ref "VSLUE8") (pin "11") (pinfunction "2A1_11") (pintype "input"))
      (node (ref "VSLUE8") (pin "13") (pinfunction "2A2_13") (pintype "input"))
    )
    (net (code "98") (name "/GPIO_128_M10") (class "Default")
      (node (ref "J12") (pin "2") (pinfunction "P$2_2") (pintype "bidirectional"))
      (node (ref "SV2") (pin "35") (pinfunction "35_35") (pintype "passive"))
    )
    (net (code "99") (name "/GPIO_129_L13") (class "Default")
      (node (ref "J7") (pin "1") (pinfunction "P$1_1") (pintype "bidirectional"))
      (node (ref "SV2") (pin "36") (pinfunction "36_36") (pintype "passive"))
    )
    (net (code "100") (name "/GPIO_130_J16") (class "Default")
      (node (ref "J12") (pin "1") (pinfunction "P$1_1") (pintype "bidirectional"))
      (node (ref "SV2") (pin "37") (pinfunction "37_37") (pintype "passive"))
    )
    (net (code "101") (name "/GPIO_131_K15") (class "Default")
      (node (ref "J39") (pin "2") (pinfunction "2_2") (pintype "bidirectional"))
      (node (ref "K15_R10P") (pin "1") (pinfunction "1_1") (pintype "passive"))
      (node (ref "R35") (pin "P$2") (pinfunction "2_P$2") (pintype "passive"))
      (node (ref "SV2") (pin "38") (pinfunction "38_38") (pintype "passive"))
    )
    (net (code "102") (name "/GPIO_132_J13") (class "Default")
      (node (ref "OJ77") (pin "1") (pinfunction "1_1") (pintype "bidirectional"))
      (node (ref "SV2") (pin "39") (pinfunction "39_39") (pintype "passive"))
      (node (ref "VSLUE9") (pin "15") (pinfunction "2A3_15") (pintype "input"))
      (node (ref "VSLUE9") (pin "17") (pinfunction "2A4_17") (pintype "input"))
    )
    (net (code "103") (name "/GPIO_133_J14") (class "Default")
      (node (ref "OJ7") (pin "1") (pinfunction "1_1") (pintype "bidirectional"))
      (node (ref "SV2") (pin "40") (pinfunction "40_40") (pintype "passive"))
      (node (ref "VSLUE") (pin "2") (pinfunction "1A1_2") (pintype "input"))
      (node (ref "VSLUE") (pin "4") (pinfunction "1A2_4") (pintype "input"))
    )
    (net (code "104") (name "/GPIO_210_F14") (class "Default")
      (node (ref "J1") (pin "15") (pinfunction "15_15") (pintype "passive"))
      (node (ref "OJ30") (pin "1") (pinfunction "1_1") (pintype "bidirectional"))
      (node (ref "VSLUE3") (pin "11") (pinfunction "2A1_11") (pintype "input"))
      (node (ref "VSLUE3") (pin "13") (pinfunction "2A2_13") (pintype "input"))
    )
    (net (code "105") (name "/GPIO_211_G16") (class "Default")
      (node (ref "G16_R5N") (pin "1") (pinfunction "1_1") (pintype "passive"))
      (node (ref "J1") (pin "16") (pinfunction "16_16") (pintype "passive"))
      (node (ref "J28") (pin "2") (pinfunction "2_2") (pintype "bidirectional"))
      (node (ref "R24") (pin "P$2") (pinfunction "2_P$2") (pintype "passive"))
    )
    (net (code "106") (name "/GPIO_212_G15") (class "Default")
      (node (ref "G15_R5P") (pin "1") (pinfunction "1_1") (pintype "passive"))
      (node (ref "J1") (pin "17") (pinfunction "17_17") (pintype "passive"))
      (node (ref "J29") (pin "2") (pinfunction "2_2") (pintype "bidirectional"))
      (node (ref "R26") (pin "P$2") (pinfunction "2_P$2") (pintype "passive"))
    )
    (net (code "107") (name "GND") (class "Default")
      (node (ref "A12_T21N") (pin "2") (pinfunction "2_2") (pintype "passive"))
      (node (ref "A12_T21N") (pin "3") (pinfunction "2_3") (pintype "passive"))
      (node (ref "A12_T21N") (pin "4") (pinfunction "2_4") (pintype "passive"))
      (node (ref "A12_T21N") (pin "5") (pinfunction "2_5") (pintype "passive"))
      (node (ref "A14_CLKOUT_2N") (pin "2") (pinfunction "2_2") (pintype "passive"))
      (node (ref "A14_CLKOUT_2N") (pin "3") (pinfunction "2_3") (pintype "passive"))
      (node (ref "A14_CLKOUT_2N") (pin "4") (pinfunction "2_4") (pintype "passive"))
      (node (ref "A14_CLKOUT_2N") (pin "5") (pinfunction "2_5") (pintype "passive"))
      (node (ref "A2_T2N") (pin "2") (pinfunction "2_2") (pintype "passive"))
      (node (ref "A2_T2N") (pin "3") (pinfunction "2_3") (pintype "passive"))
      (node (ref "A2_T2N") (pin "4") (pinfunction "2_4") (pintype "passive"))
      (node (ref "A2_T2N") (pin "5") (pinfunction "2_5") (pintype "passive"))
      (node (ref "A3_T2P") (pin "2") (pinfunction "2_2") (pintype "passive"))
      (node (ref "A3_T2P") (pin "3") (pinfunction "2_3") (pintype "passive"))
      (node (ref "A3_T2P") (pin "4") (pinfunction "2_4") (pintype "passive"))
      (node (ref "A3_T2P") (pin "5") (pinfunction "2_5") (pintype "passive"))
      (node (ref "A4") (pin "2") (pinfunction "2_2") (pintype "passive"))
      (node (ref "A4") (pin "3") (pinfunction "2_3") (pintype "passive"))
      (node (ref "A4") (pin "4") (pinfunction "2_4") (pintype "passive"))
      (node (ref "A4") (pin "5") (pinfunction "2_5") (pintype "passive"))
      (node (ref "A5") (pin "2") (pinfunction "2_2") (pintype "passive"))
      (node (ref "A5") (pin "3") (pinfunction "2_3") (pintype "passive"))
      (node (ref "A5") (pin "4") (pinfunction "2_4") (pintype "passive"))
      (node (ref "A5") (pin "5") (pinfunction "2_5") (pintype "passive"))
      (node (ref "A6") (pin "2") (pinfunction "2_2") (pintype "passive"))
      (node (ref "A6") (pin "3") (pinfunction "2_3") (pintype "passive"))
      (node (ref "A6") (pin "4") (pinfunction "2_4") (pintype "passive"))
      (node (ref "A6") (pin "5") (pinfunction "2_5") (pintype "passive"))
      (node (ref "A7_T9N") (pin "2") (pinfunction "2_2") (pintype "passive"))
      (node (ref "A7_T9N") (pin "3") (pinfunction "2_3") (pintype "passive"))
      (node (ref "A7_T9N") (pin "4") (pinfunction "2_4") (pintype "passive"))
      (node (ref "A7_T9N") (pin "5") (pinfunction "2_5") (pintype "passive"))
      (node (ref "A8CLK_4N") (pin "2") (pinfunction "2_2") (pintype "passive"))
      (node (ref "A8CLK_4N") (pin "3") (pinfunction "2_3") (pintype "passive"))
      (node (ref "A8CLK_4N") (pin "4") (pinfunction "2_4") (pintype "passive"))
      (node (ref "A8CLK_4N") (pin "5") (pinfunction "2_5") (pintype "passive"))
      (node (ref "B11") (pin "2") (pinfunction "2_2") (pintype "passive"))
      (node (ref "B11") (pin "3") (pinfunction "2_3") (pintype "passive"))
      (node (ref "B11") (pin "4") (pinfunction "2_4") (pintype "passive"))
      (node (ref "B11") (pin "5") (pinfunction "2_5") (pintype "passive"))
      (node (ref "B12_T21P") (pin "2") (pinfunction "2_2") (pintype "passive"))
      (node (ref "B12_T21P") (pin "3") (pinfunction "2_3") (pintype "passive"))
      (node (ref "B12_T21P") (pin "4") (pinfunction "2_4") (pintype "passive"))
      (node (ref "B12_T21P") (pin "5") (pinfunction "2_5") (pintype "passive"))
      (node (ref "B16") (pin "2") (pinfunction "2_2") (pintype "passive"))
      (node (ref "B16") (pin "3") (pinfunction "2_3") (pintype "passive"))
      (node (ref "B16") (pin "4") (pinfunction "2_4") (pintype "passive"))
      (node (ref "B16") (pin "5") (pinfunction "2_5") (pintype "passive"))
      (node (ref "B3") (pin "2") (pinfunction "2_2") (pintype "passive"))
      (node (ref "B3") (pin "3") (pinfunction "2_3") (pintype "passive"))
      (node (ref "B3") (pin "4") (pinfunction "2_4") (pintype "passive"))
      (node (ref "B3") (pin "5") (pinfunction "2_5") (pintype "passive"))
      (node (ref "B4") (pin "2") (pinfunction "2_2") (pintype "passive"))
      (node (ref "B4") (pin "3") (pinfunction "2_3") (pintype "passive"))
      (node (ref "B4") (pin "4") (pinfunction "2_4") (pintype "passive"))
      (node (ref "B4") (pin "5") (pinfunction "2_5") (pintype "passive"))
      (node (ref "B5") (pin "2") (pinfunction "2_2") (pintype "passive"))
      (node (ref "B5") (pin "3") (pinfunction "2_3") (pintype "passive"))
      (node (ref "B5") (pin "4") (pinfunction "2_4") (pintype "passive"))
      (node (ref "B5") (pin "5") (pinfunction "2_5") (pintype "passive"))
      (node (ref "B6") (pin "2") (pinfunction "2_2") (pintype "passive"))
      (node (ref "B6") (pin "3") (pinfunction "2_3") (pintype "passive"))
      (node (ref "B6") (pin "4") (pinfunction "2_4") (pintype "passive"))
      (node (ref "B6") (pin "5") (pinfunction "2_5") (pintype "passive"))
      (node (ref "B7_T9P") (pin "2") (pinfunction "2_2") (pintype "passive"))
      (node (ref "B7_T9P") (pin "3") (pinfunction "2_3") (pintype "passive"))
      (node (ref "B7_T9P") (pin "4") (pinfunction "2_4") (pintype "passive"))
      (node (ref "B7_T9P") (pin "5") (pinfunction "2_5") (pintype "passive"))
      (node (ref "B8CLK_4P") (pin "2") (pinfunction "2_2") (pintype "passive"))
      (node (ref "B8CLK_4P") (pin "3") (pinfunction "2_3") (pintype "passive"))
      (node (ref "B8CLK_4P") (pin "4") (pinfunction "2_4") (pintype "passive"))
      (node (ref "B8CLK_4P") (pin "5") (pinfunction "2_5") (pintype "passive"))
      (node (ref "C10") (pin "1") (pinfunction "1_1") (pintype "passive"))
      (node (ref "C11") (pin "2") (pinfunction "2_2") (pintype "passive"))
      (node (ref "C11") (pin "3") (pinfunction "2_3") (pintype "passive"))
      (node (ref "C11") (pin "4") (pinfunction "2_4") (pintype "passive"))
      (node (ref "C11") (pin "5") (pinfunction "2_5") (pintype "passive"))
      (node (ref "C13") (pin "2") (pinfunction "2_2") (pintype "passive"))
      (node (ref "C14") (pin "2") (pinfunction "2_2") (pintype "passive"))
      (node (ref "C14") (pin "3") (pinfunction "2_3") (pintype "passive"))
      (node (ref "C14") (pin "4") (pinfunction "2_4") (pintype "passive"))
      (node (ref "C14") (pin "5") (pinfunction "2_5") (pintype "passive"))
      (node (ref "C15") (pin "2") (pinfunction "2_2") (pintype "passive"))
      (node (ref "C15") (pin "3") (pinfunction "2_3") (pintype "passive"))
      (node (ref "C15") (pin "4") (pinfunction "2_4") (pintype "passive"))
      (node (ref "C15") (pin "5") (pinfunction "2_5") (pintype "passive"))
      (node (ref "C16") (pin "2") (pinfunction "2_2") (pintype "passive"))
      (node (ref "C16") (pin "3") (pinfunction "2_3") (pintype "passive"))
      (node (ref "C16") (pin "4") (pinfunction "2_4") (pintype "passive"))
      (node (ref "C16") (pin "5") (pinfunction "2_5") (pintype "passive"))
      (node (ref "C18") (pin "2") (pinfunction "2_2") (pintype "passive"))
      (node (ref "C19") (pin "1") (pinfunction "1_1") (pintype "passive"))
      (node (ref "C2") (pin "1") (pinfunction "1_1") (pintype "passive"))
      (node (ref "C20") (pin "1") (pinfunction "1_1") (pintype "passive"))
      (node (ref "C21") (pin "1") (pinfunction "1_1") (pintype "passive"))
      (node (ref "C22") (pin "1") (pinfunction "1_1") (pintype "passive"))
      (node (ref "C3") (pin "2") (pinfunction "2_2") (pintype "passive"))
      (node (ref "C3_CLKOUT_3N") (pin "2") (pinfunction "2_2") (pintype "passive"))
      (node (ref "C3_CLKOUT_3N") (pin "3") (pinfunction "2_3") (pintype "passive"))
      (node (ref "C3_CLKOUT_3N") (pin "4") (pinfunction "2_4") (pintype "passive"))
      (node (ref "C3_CLKOUT_3N") (pin "5") (pinfunction "2_5") (pintype "passive"))
      (node (ref "C4") (pin "1") (pinfunction "1_1") (pintype "passive"))
      (node (ref "C5") (pin "1") (pinfunction "1_1") (pintype "passive"))
      (node (ref "C6") (pin "2") (pinfunction "2_2") (pintype "passive"))
      (node (ref "C6") (pin "3") (pinfunction "2_3") (pintype "passive"))
      (node (ref "C6") (pin "4") (pinfunction "2_4") (pintype "passive"))
      (node (ref "C6") (pin "5") (pinfunction "2_5") (pintype "passive"))
      (node (ref "C8") (pin "2") (pinfunction "2_2") (pintype "passive"))
      (node (ref "C8") (pin "3") (pinfunction "2_3") (pintype "passive"))
      (node (ref "C8") (pin "4") (pinfunction "2_4") (pintype "passive"))
      (node (ref "C8") (pin "5") (pinfunction "2_5") (pintype "passive"))
      (node (ref "C9") (pin "2") (pinfunction "2_2") (pintype "passive"))
      (node (ref "C91") (pin "1") (pinfunction "1_1") (pintype "passive"))
      (node (ref "C93") (pin "1") (pinfunction "1_1") (pintype "passive"))
      (node (ref "C94") (pin "1") (pinfunction "1_1") (pintype "passive"))
      (node (ref "C95") (pin "1") (pinfunction "1_1") (pintype "passive"))
      (node (ref "C96") (pin "1") (pinfunction "1_1") (pintype "passive"))
      (node (ref "C97") (pin "1") (pinfunction "1_1") (pintype "passive"))
      (node (ref "C9_T15N") (pin "2") (pinfunction "2_2") (pintype "passive"))
      (node (ref "C9_T15N") (pin "3") (pinfunction "2_3") (pintype "passive"))
      (node (ref "C9_T15N") (pin "4") (pinfunction "2_4") (pintype "passive"))
      (node (ref "C9_T15N") (pin "5") (pinfunction "2_5") (pintype "passive"))
      (node (ref "D11") (pin "2") (pinfunction "2_2") (pintype "passive"))
      (node (ref "D11") (pin "3") (pinfunction "2_3") (pintype "passive"))
      (node (ref "D11") (pin "4") (pinfunction "2_4") (pintype "passive"))
      (node (ref "D11") (pin "5") (pinfunction "2_5") (pintype "passive"))
      (node (ref "D12") (pin "2") (pinfunction "2_2") (pintype "passive"))
      (node (ref "D12") (pin "3") (pinfunction "2_3") (pintype "passive"))
      (node (ref "D12") (pin "4") (pinfunction "2_4") (pintype "passive"))
      (node (ref "D12") (pin "5") (pinfunction "2_5") (pintype "passive"))
      (node (ref "D14") (pin "2") (pinfunction "2_2") (pintype "passive"))
      (node (ref "D14") (pin "3") (pinfunction "2_3") (pintype "passive"))
      (node (ref "D14") (pin "4") (pinfunction "2_4") (pintype "passive"))
      (node (ref "D14") (pin "5") (pinfunction "2_5") (pintype "passive"))
      (node (ref "D15") (pin "2") (pinfunction "2_2") (pintype "passive"))
      (node (ref "D15") (pin "3") (pinfunction "2_3") (pintype "passive"))
      (node (ref "D15") (pin "4") (pinfunction "2_4") (pintype "passive"))
      (node (ref "D15") (pin "5") (pinfunction "2_5") (pintype "passive"))
      (node (ref "D16") (pin "2") (pinfunction "2_2") (pintype "passive"))
      (node (ref "D16") (pin "3") (pinfunction "2_3") (pintype "passive"))
      (node (ref "D16") (pin "4") (pinfunction "2_4") (pintype "passive"))
      (node (ref "D16") (pin "5") (pinfunction "2_5") (pintype "passive"))
      (node (ref "D3_CLKOUT_3P") (pin "2") (pinfunction "2_2") (pintype "passive"))
      (node (ref "D3_CLKOUT_3P") (pin "3") (pinfunction "2_3") (pintype "passive"))
      (node (ref "D3_CLKOUT_3P") (pin "4") (pinfunction "2_4") (pintype "passive"))
      (node (ref "D3_CLKOUT_3P") (pin "5") (pinfunction "2_5") (pintype "passive"))
      (node (ref "D5") (pin "2") (pinfunction "2_2") (pintype "passive"))
      (node (ref "D5") (pin "3") (pinfunction "2_3") (pintype "passive"))
      (node (ref "D5") (pin "4") (pinfunction "2_4") (pintype "passive"))
      (node (ref "D5") (pin "5") (pinfunction "2_5") (pintype "passive"))
      (node (ref "D6") (pin "2") (pinfunction "2_2") (pintype "passive"))
      (node (ref "D6") (pin "3") (pinfunction "2_3") (pintype "passive"))
      (node (ref "D6") (pin "4") (pinfunction "2_4") (pintype "passive"))
      (node (ref "D6") (pin "5") (pinfunction "2_5") (pintype "passive"))
      (node (ref "D8") (pin "2") (pinfunction "2_2") (pintype "passive"))
      (node (ref "D8") (pin "3") (pinfunction "2_3") (pintype "passive"))
      (node (ref "D8") (pin "4") (pinfunction "2_4") (pintype "passive"))
      (node (ref "D8") (pin "5") (pinfunction "2_5") (pintype "passive"))
      (node (ref "D9_T15P") (pin "2") (pinfunction "2_2") (pintype "passive"))
      (node (ref "D9_T15P") (pin "3") (pinfunction "2_3") (pintype "passive"))
      (node (ref "D9_T15P") (pin "4") (pinfunction "2_4") (pintype "passive"))
      (node (ref "D9_T15P") (pin "5") (pinfunction "2_5") (pintype "passive"))
      (node (ref "E10") (pin "2") (pinfunction "2_2") (pintype "passive"))
      (node (ref "E10") (pin "3") (pinfunction "2_3") (pintype "passive"))
      (node (ref "E10") (pin "4") (pinfunction "2_4") (pintype "passive"))
      (node (ref "E10") (pin "5") (pinfunction "2_5") (pintype "passive"))
      (node (ref "E11") (pin "2") (pinfunction "2_2") (pintype "passive"))
      (node (ref "E11") (pin "3") (pinfunction "2_3") (pintype "passive"))
      (node (ref "E11") (pin "4") (pinfunction "2_4") (pintype "passive"))
      (node (ref "E11") (pin "5") (pinfunction "2_5") (pintype "passive"))
      (node (ref "E15CLK_2P") (pin "2") (pinfunction "2_2") (pintype "passive"))
      (node (ref "E15CLK_2P") (pin "3") (pinfunction "2_3") (pintype "passive"))
      (node (ref "E15CLK_2P") (pin "4") (pinfunction "2_4") (pintype "passive"))
      (node (ref "E15CLK_2P") (pin "5") (pinfunction "2_5") (pintype "passive"))
      (node (ref "E16CLK_2N") (pin "2") (pinfunction "2_2") (pintype "passive"))
      (node (ref "E16CLK_2N") (pin "3") (pinfunction "2_3") (pintype "passive"))
      (node (ref "E16CLK_2N") (pin "4") (pinfunction "2_4") (pintype "passive"))
      (node (ref "E16CLK_2N") (pin "5") (pinfunction "2_5") (pintype "passive"))
      (node (ref "E6") (pin "2") (pinfunction "2_2") (pintype "passive"))
      (node (ref "E6") (pin "3") (pinfunction "2_3") (pintype "passive"))
      (node (ref "E6") (pin "4") (pinfunction "2_4") (pintype "passive"))
      (node (ref "E6") (pin "5") (pinfunction "2_5") (pintype "passive"))
      (node (ref "E7") (pin "2") (pinfunction "2_2") (pintype "passive"))
      (node (ref "E7") (pin "3") (pinfunction "2_3") (pintype "passive"))
      (node (ref "E7") (pin "4") (pinfunction "2_4") (pintype "passive"))
      (node (ref "E7") (pin "5") (pinfunction "2_5") (pintype "passive"))
      (node (ref "E8_T10N") (pin "2") (pinfunction "2_2") (pintype "passive"))
      (node (ref "E8_T10N") (pin "3") (pinfunction "2_3") (pintype "passive"))
      (node (ref "E8_T10N") (pin "4") (pinfunction "2_4") (pintype "passive"))
      (node (ref "E8_T10N") (pin "5") (pinfunction "2_5") (pintype "passive"))
      (node (ref "E9") (pin "2") (pinfunction "2_2") (pintype "passive"))
      (node (ref "E9") (pin "3") (pinfunction "2_3") (pintype "passive"))
      (node (ref "E9") (pin "4") (pinfunction "2_4") (pintype "passive"))
      (node (ref "E9") (pin "5") (pinfunction "2_5") (pintype "passive"))
      (node (ref "F14") (pin "2") (pinfunction "2_2") (pintype "passive"))
      (node (ref "F14") (pin "3") (pinfunction "2_3") (pintype "passive"))
      (node (ref "F14") (pin "4") (pinfunction "2_4") (pintype "passive"))
      (node (ref "F14") (pin "5") (pinfunction "2_5") (pintype "passive"))
      (node (ref "F15") (pin "2") (pinfunction "2_2") (pintype "passive"))
      (node (ref "F15") (pin "3") (pinfunction "2_3") (pintype "passive"))
      (node (ref "F15") (pin "4") (pinfunction "2_4") (pintype "passive"))
      (node (ref "F15") (pin "5") (pinfunction "2_5") (pintype "passive"))
      (node (ref "F16") (pin "2") (pinfunction "2_2") (pintype "passive"))
      (node (ref "F16") (pin "3") (pinfunction "2_3") (pintype "passive"))
      (node (ref "F16") (pin "4") (pinfunction "2_4") (pintype "passive"))
      (node (ref "F16") (pin "5") (pinfunction "2_5") (pintype "passive"))
      (node (ref "F8_T10P") (pin "2") (pinfunction "2_2") (pintype "passive"))
      (node (ref "F8_T10P") (pin "3") (pinfunction "2_3") (pintype "passive"))
      (node (ref "F8_T10P") (pin "4") (pinfunction "2_4") (pintype "passive"))
      (node (ref "F8_T10P") (pin "5") (pinfunction "2_5") (pintype "passive"))
      (node (ref "F9") (pin "2") (pinfunction "2_2") (pintype "passive"))
      (node (ref "F9") (pin "3") (pinfunction "2_3") (pintype "passive"))
      (node (ref "F9") (pin "4") (pinfunction "2_4") (pintype "passive"))
      (node (ref "F9") (pin "5") (pinfunction "2_5") (pintype "passive"))
      (node (ref "G15_R5P") (pin "2") (pinfunction "2_2") (pintype "passive"))
      (node (ref "G15_R5P") (pin "3") (pinfunction "2_3") (pintype "passive"))
      (node (ref "G15_R5P") (pin "4") (pinfunction "2_4") (pintype "passive"))
      (node (ref "G15_R5P") (pin "5") (pinfunction "2_5") (pintype "passive"))
      (node (ref "G16_R5N") (pin "2") (pinfunction "2_2") (pintype "passive"))
      (node (ref "G16_R5N") (pin "3") (pinfunction "2_3") (pintype "passive"))
      (node (ref "G16_R5N") (pin "4") (pinfunction "2_4") (pintype "passive"))
      (node (ref "G16_R5N") (pin "5") (pinfunction "2_5") (pintype "passive"))
      (node (ref "IC1") (pin "3") (pinfunction "GND_3") (pintype "power_in"))
      (node (ref "IC2") (pin "3") (pinfunction "GND_3") (pintype "power_in"))
      (node (ref "IC3") (pin "3") (pinfunction "GND_3") (pintype "power_in"))
      (node (ref "IC4") (pin "3") (pinfunction "GND_3") (pintype "power_in"))
      (node (ref "J1") (pin "26") (pinfunction "26_26") (pintype "passive"))
      (node (ref "J10") (pin "1") (pinfunction "1_1") (pintype "bidirectional"))
      (node (ref "J11") (pin "1") (pinfunction "1_1") (pintype "bidirectional"))
      (node (ref "J12") (pin "3") (pinfunction "P$3_3") (pintype "bidirectional"))
      (node (ref "J13") (pin "2") (pinfunction "2_2") (pintype "passive"))
      (node (ref "J13") (pin "3") (pinfunction "2_3") (pintype "passive"))
      (node (ref "J13") (pin "4") (pinfunction "2_4") (pintype "passive"))
      (node (ref "J13") (pin "5") (pinfunction "2_5") (pintype "passive"))
      (node (ref "J14") (pin "2") (pinfunction "2_2") (pintype "passive"))
      (node (ref "J14") (pin "3") (pinfunction "2_3") (pintype "passive"))
      (node (ref "J14") (pin "4") (pinfunction "2_4") (pintype "passive"))
      (node (ref "J14") (pin "5") (pinfunction "2_5") (pintype "passive"))
      (node (ref "J141") (pin "1") (pinfunction "1_1") (pintype "bidirectional"))
      (node (ref "J15") (pin "1") (pinfunction "1_1") (pintype "bidirectional"))
      (node (ref "J16") (pin "1") (pinfunction "1_1") (pintype "bidirectional"))
      (node (ref "J17") (pin "1") (pinfunction "1_1") (pintype "bidirectional"))
      (node (ref "J18") (pin "1") (pinfunction "1_1") (pintype "bidirectional"))
      (node (ref "J19") (pin "1-A9") (pinfunction "MS_1-A9") (pintype "passive"))
      (node (ref "J19") (pin "1-C9") (pinfunction "MS_1-C9") (pintype "passive"))
      (node (ref "J19") (pin "2-A9") (pinfunction "MS_2-A9") (pintype "passive"))
      (node (ref "J19") (pin "2-C9") (pinfunction "MS_2-C9") (pintype "passive"))
      (node (ref "J20") (pin "3") (pinfunction "P$3_3") (pintype "bidirectional"))
      (node (ref "J21") (pin "3") (pinfunction "P$3_3") (pintype "bidirectional"))
      (node (ref "J22") (pin "1") (pinfunction "1_1") (pintype "bidirectional"))
      (node (ref "J23") (pin "1") (pinfunction "1_1") (pintype "bidirectional"))
      (node (ref "J24") (pin "1") (pinfunction "1_1") (pintype "bidirectional"))
      (node (ref "J25") (pin "1") (pinfunction "1_1") (pintype "bidirectional"))
      (node (ref "J26") (pin "3") (pinfunction "P$3_3") (pintype "bidirectional"))
      (node (ref "J27") (pin "3") (pinfunction "P$3_3") (pintype "bidirectional"))
      (node (ref "J28") (pin "1") (pinfunction "1_1") (pintype "bidirectional"))
      (node (ref "J29") (pin "1") (pinfunction "1_1") (pintype "bidirectional"))
      (node (ref "J30") (pin "1") (pinfunction "1_1") (pintype "bidirectional"))
      (node (ref "J31") (pin "1") (pinfunction "1_1") (pintype "bidirectional"))
      (node (ref "J32") (pin "1") (pinfunction "1_1") (pintype "bidirectional"))
      (node (ref "J33") (pin "1") (pinfunction "1_1") (pintype "bidirectional"))
      (node (ref "J34") (pin "1") (pinfunction "1_1") (pintype "bidirectional"))
      (node (ref "J35") (pin "1") (pinfunction "1_1") (pintype "bidirectional"))
      (node (ref "J36") (pin "1") (pinfunction "1_1") (pintype "bidirectional"))
      (node (ref "J37") (pin "1") (pinfunction "1_1") (pintype "bidirectional"))
      (node (ref "J38") (pin "1") (pinfunction "1_1") (pintype "bidirectional"))
      (node (ref "J39") (pin "1") (pinfunction "1_1") (pintype "bidirectional"))
      (node (ref "J4") (pin "1") (pinfunction "1_1") (pintype "bidirectional"))
      (node (ref "J40") (pin "1") (pinfunction "1_1") (pintype "bidirectional"))
      (node (ref "J41") (pin "1") (pinfunction "1_1") (pintype "bidirectional"))
      (node (ref "J42") (pin "1") (pinfunction "1_1") (pintype "bidirectional"))
      (node (ref "J43") (pin "1") (pinfunction "1_1") (pintype "bidirectional"))
      (node (ref "J48") (pin "1") (pinfunction "1_1") (pintype "bidirectional"))
      (node (ref "J49") (pin "1") (pinfunction "1_1") (pintype "bidirectional"))
      (node (ref "J5") (pin "1") (pinfunction "1_1") (pintype "bidirectional"))
      (node (ref "J50") (pin "1") (pinfunction "1_1") (pintype "bidirectional"))
      (node (ref "J51") (pin "1") (pinfunction "1_1") (pintype "bidirectional"))
      (node (ref "J52") (pin "1") (pinfunction "1_1") (pintype "bidirectional"))
      (node (ref "J53") (pin "1") (pinfunction "1_1") (pintype "bidirectional"))
      (node (ref "J54") (pin "1") (pinfunction "1_1") (pintype "bidirectional"))
      (node (ref "J55") (pin "1") (pinfunction "1_1") (pintype "bidirectional"))
      (node (ref "J6") (pin "1") (pinfunction "1_1") (pintype "bidirectional"))
      (node (ref "J7") (pin "3") (pinfunction "P$3_3") (pintype "bidirectional"))
      (node (ref "J8") (pin "1") (pinfunction "1_1") (pintype "bidirectional"))
      (node (ref "J9") (pin "1") (pinfunction "1_1") (pintype "bidirectional"))
      (node (ref "K15_R10P") (pin "2") (pinfunction "2_2") (pintype "passive"))
      (node (ref "K15_R10P") (pin "3") (pinfunction "2_3") (pintype "passive"))
      (node (ref "K15_R10P") (pin "4") (pinfunction "2_4") (pintype "passive"))
      (node (ref "K15_R10P") (pin "5") (pinfunction "2_5") (pintype "passive"))
      (node (ref "K16_R10N") (pin "2") (pinfunction "2_2") (pintype "passive"))
      (node (ref "K16_R10N") (pin "3") (pinfunction "2_3") (pintype "passive"))
      (node (ref "K16_R10N") (pin "4") (pinfunction "2_4") (pintype "passive"))
      (node (ref "K16_R10N") (pin "5") (pinfunction "2_5") (pintype "passive"))
      (node (ref "L15_R11P") (pin "2") (pinfunction "2_2") (pintype "passive"))
      (node (ref "L15_R11P") (pin "3") (pinfunction "2_3") (pintype "passive"))
      (node (ref "L15_R11P") (pin "4") (pinfunction "2_4") (pintype "passive"))
      (node (ref "L15_R11P") (pin "5") (pinfunction "2_5") (pintype "passive"))
      (node (ref "L16_R11N") (pin "2") (pinfunction "2_2") (pintype "passive"))
      (node (ref "L16_R11N") (pin "3") (pinfunction "2_3") (pintype "passive"))
      (node (ref "L16_R11N") (pin "4") (pinfunction "2_4") (pintype "passive"))
      (node (ref "L16_R11N") (pin "5") (pinfunction "2_5") (pintype "passive"))
      (node (ref "M16CLK_3N") (pin "2") (pinfunction "2_2") (pintype "passive"))
      (node (ref "M16CLK_3N") (pin "3") (pinfunction "2_3") (pintype "passive"))
      (node (ref "M16CLK_3N") (pin "4") (pinfunction "2_4") (pintype "passive"))
      (node (ref "M16CLK_3N") (pin "5") (pinfunction "2_5") (pintype "passive"))
      (node (ref "N11") (pin "2") (pinfunction "2_2") (pintype "passive"))
      (node (ref "N11") (pin "3") (pinfunction "2_3") (pintype "passive"))
      (node (ref "N11") (pin "4") (pinfunction "2_4") (pintype "passive"))
      (node (ref "N11") (pin "5") (pinfunction "2_5") (pintype "passive"))
      (node (ref "N12") (pin "2") (pinfunction "2_2") (pintype "passive"))
      (node (ref "N12") (pin "3") (pinfunction "2_3") (pintype "passive"))
      (node (ref "N12") (pin "4") (pinfunction "2_4") (pintype "passive"))
      (node (ref "N12") (pin "5") (pinfunction "2_5") (pintype "passive"))
      (node (ref "N14") (pin "2") (pinfunction "2_2") (pintype "passive"))
      (node (ref "N14") (pin "3") (pinfunction "2_3") (pintype "passive"))
      (node (ref "N14") (pin "4") (pinfunction "2_4") (pintype "passive"))
      (node (ref "N14") (pin "5") (pinfunction "2_5") (pintype "passive"))
      (node (ref "N15_R13P") (pin "2") (pinfunction "2_2") (pintype "passive"))
      (node (ref "N15_R13P") (pin "3") (pinfunction "2_3") (pintype "passive"))
      (node (ref "N15_R13P") (pin "4") (pinfunction "2_4") (pintype "passive"))
      (node (ref "N15_R13P") (pin "5") (pinfunction "2_5") (pintype "passive"))
      (node (ref "N16_R13N") (pin "2") (pinfunction "2_2") (pintype "passive"))
      (node (ref "N16_R13N") (pin "3") (pinfunction "2_3") (pintype "passive"))
      (node (ref "N16_R13N") (pin "4") (pinfunction "2_4") (pintype "passive"))
      (node (ref "N16_R13N") (pin "5") (pinfunction "2_5") (pintype "passive"))
      (node (ref "OJ1") (pin "2") (pinfunction "2_2") (pintype "bidirectional"))
      (node (ref "OJ17") (pin "2") (pinfunction "2_2") (pintype "bidirectional"))
      (node (ref "OJ18") (pin "2") (pinfunction "2_2") (pintype "bidirectional"))
      (node (ref "OJ19") (pin "2") (pinfunction "2_2") (pintype "bidirectional"))
      (node (ref "OJ2") (pin "2") (pinfunction "2_2") (pintype "bidirectional"))
      (node (ref "OJ20") (pin "2") (pinfunction "2_2") (pintype "bidirectional"))
      (node (ref "OJ21") (pin "2") (pinfunction "2_2") (pintype "bidirectional"))
      (node (ref "OJ22") (pin "2") (pinfunction "2_2") (pintype "bidirectional"))
      (node (ref "OJ23") (pin "2") (pinfunction "2_2") (pintype "bidirectional"))
      (node (ref "OJ24") (pin "2") (pinfunction "2_2") (pintype "bidirectional"))
      (node (ref "OJ25") (pin "2") (pinfunction "2_2") (pintype "bidirectional"))
      (node (ref "OJ26") (pin "2") (pinfunction "2_2") (pintype "bidirectional"))
      (node (ref "OJ27") (pin "2") (pinfunction "2_2") (pintype "bidirectional"))
      (node (ref "OJ28") (pin "2") (pinfunction "2_2") (pintype "bidirectional"))
      (node (ref "OJ29") (pin "2") (pinfunction "2_2") (pintype "bidirectional"))
      (node (ref "OJ3") (pin "2") (pinfunction "2_2") (pintype "bidirectional"))
      (node (ref "OJ30") (pin "2") (pinfunction "2_2") (pintype "bidirectional"))
      (node (ref "OJ31") (pin "2") (pinfunction "2_2") (pintype "bidirectional"))
      (node (ref "OJ32") (pin "2") (pinfunction "2_2") (pintype "bidirectional"))
      (node (ref "OJ33") (pin "2") (pinfunction "2_2") (pintype "bidirectional"))
      (node (ref "OJ34") (pin "2") (pinfunction "2_2") (pintype "bidirectional"))
      (node (ref "OJ35") (pin "2") (pinfunction "2_2") (pintype "bidirectional"))
      (node (ref "OJ36") (pin "2") (pinfunction "2_2") (pintype "bidirectional"))
      (node (ref "OJ37") (pin "2") (pinfunction "2_2") (pintype "bidirectional"))
      (node (ref "OJ38") (pin "2") (pinfunction "2_2") (pintype "bidirectional"))
      (node (ref "OJ39") (pin "2") (pinfunction "2_2") (pintype "bidirectional"))
      (node (ref "OJ4") (pin "2") (pinfunction "2_2") (pintype "bidirectional"))
      (node (ref "OJ40") (pin "2") (pinfunction "2_2") (pintype "bidirectional"))
      (node (ref "OJ41") (pin "2") (pinfunction "2_2") (pintype "bidirectional"))
      (node (ref "OJ42") (pin "2") (pinfunction "2_2") (pintype "bidirectional"))
      (node (ref "OJ43") (pin "2") (pinfunction "2_2") (pintype "bidirectional"))
      (node (ref "OJ44") (pin "2") (pinfunction "2_2") (pintype "bidirectional"))
      (node (ref "OJ45") (pin "2") (pinfunction "2_2") (pintype "bidirectional"))
      (node (ref "OJ46") (pin "2") (pinfunction "2_2") (pintype "bidirectional"))
      (node (ref "OJ47") (pin "2") (pinfunction "2_2") (pintype "bidirectional"))
      (node (ref "OJ48") (pin "2") (pinfunction "2_2") (pintype "bidirectional"))
      (node (ref "OJ49") (pin "2") (pinfunction "2_2") (pintype "bidirectional"))
      (node (ref "OJ5") (pin "2") (pinfunction "2_2") (pintype "bidirectional"))
      (node (ref "OJ50") (pin "2") (pinfunction "2_2") (pintype "bidirectional"))
      (node (ref "OJ51") (pin "2") (pinfunction "2_2") (pintype "bidirectional"))
      (node (ref "OJ52") (pin "2") (pinfunction "2_2") (pintype "bidirectional"))
      (node (ref "OJ53") (pin "2") (pinfunction "2_2") (pintype "bidirectional"))
      (node (ref "OJ54") (pin "2") (pinfunction "2_2") (pintype "bidirectional"))
      (node (ref "OJ55") (pin "2") (pinfunction "2_2") (pintype "bidirectional"))
      (node (ref "OJ56") (pin "2") (pinfunction "2_2") (pintype "bidirectional"))
      (node (ref "OJ57") (pin "2") (pinfunction "2_2") (pintype "bidirectional"))
      (node (ref "OJ58") (pin "2") (pinfunction "2_2") (pintype "bidirectional"))
      (node (ref "OJ59") (pin "2") (pinfunction "2_2") (pintype "bidirectional"))
      (node (ref "OJ6") (pin "2") (pinfunction "2_2") (pintype "bidirectional"))
      (node (ref "OJ60") (pin "2") (pinfunction "2_2") (pintype "bidirectional"))
      (node (ref "OJ61") (pin "2") (pinfunction "2_2") (pintype "bidirectional"))
      (node (ref "OJ62") (pin "2") (pinfunction "2_2") (pintype "bidirectional"))
      (node (ref "OJ63") (pin "2") (pinfunction "2_2") (pintype "bidirectional"))
      (node (ref "OJ64") (pin "2") (pinfunction "2_2") (pintype "bidirectional"))
      (node (ref "OJ65") (pin "2") (pinfunction "2_2") (pintype "bidirectional"))
      (node (ref "OJ66") (pin "2") (pinfunction "2_2") (pintype "bidirectional"))
      (node (ref "OJ67") (pin "2") (pinfunction "2_2") (pintype "bidirectional"))
      (node (ref "OJ68") (pin "2") (pinfunction "2_2") (pintype "bidirectional"))
      (node (ref "OJ69") (pin "2") (pinfunction "2_2") (pintype "bidirectional"))
      (node (ref "OJ7") (pin "2") (pinfunction "2_2") (pintype "bidirectional"))
      (node (ref "OJ70") (pin "2") (pinfunction "2_2") (pintype "bidirectional"))
      (node (ref "OJ71") (pin "2") (pinfunction "2_2") (pintype "bidirectional"))
      (node (ref "OJ72") (pin "2") (pinfunction "2_2") (pintype "bidirectional"))
      (node (ref "OJ73") (pin "2") (pinfunction "2_2") (pintype "bidirectional"))
      (node (ref "OJ74") (pin "2") (pinfunction "2_2") (pintype "bidirectional"))
      (node (ref "OJ75") (pin "2") (pinfunction "2_2") (pintype "bidirectional"))
      (node (ref "OJ76") (pin "2") (pinfunction "2_2") (pintype "bidirectional"))
      (node (ref "OJ77") (pin "2") (pinfunction "2_2") (pintype "bidirectional"))
      (node (ref "OJ78") (pin "2") (pinfunction "2_2") (pintype "bidirectional"))
      (node (ref "OJ79") (pin "2") (pinfunction "2_2") (pintype "bidirectional"))
      (node (ref "OJ8") (pin "2") (pinfunction "2_2") (pintype "bidirectional"))
      (node (ref "OJ80") (pin "2") (pinfunction "2_2") (pintype "bidirectional"))
      (node (ref "OJ89") (pin "2") (pinfunction "2_2") (pintype "bidirectional"))
      (node (ref "OJ90") (pin "2") (pinfunction "2_2") (pintype "bidirectional"))
      (node (ref "OJ91") (pin "2") (pinfunction "2_2") (pintype "bidirectional"))
      (node (ref "OJ92") (pin "2") (pinfunction "2_2") (pintype "bidirectional"))
      (node (ref "OJ93") (pin "2") (pinfunction "2_2") (pintype "bidirectional"))
      (node (ref "OJ94") (pin "2") (pinfunction "2_2") (pintype "bidirectional"))
      (node (ref "OJ95") (pin "2") (pinfunction "2_2") (pintype "bidirectional"))
      (node (ref "OJ96") (pin "2") (pinfunction "2_2") (pintype "bidirectional"))
      (node (ref "P11") (pin "2") (pinfunction "2_2") (pintype "passive"))
      (node (ref "P11") (pin "3") (pinfunction "2_3") (pintype "passive"))
      (node (ref "P11") (pin "4") (pinfunction "2_4") (pintype "passive"))
      (node (ref "P11") (pin "5") (pinfunction "2_5") (pintype "passive"))
      (node (ref "P14_CLKOUT_4P") (pin "2") (pinfunction "2_2") (pintype "passive"))
      (node (ref "P14_CLKOUT_4P") (pin "3") (pinfunction "2_3") (pintype "passive"))
      (node (ref "P14_CLKOUT_4P") (pin "4") (pinfunction "2_4") (pintype "passive"))
      (node (ref "P14_CLKOUT_4P") (pin "5") (pinfunction "2_5") (pintype "passive"))
      (node (ref "P15") (pin "2") (pinfunction "2_2") (pintype "passive"))
      (node (ref "P15") (pin "3") (pinfunction "2_3") (pintype "passive"))
      (node (ref "P15") (pin "4") (pinfunction "2_4") (pintype "passive"))
      (node (ref "P15") (pin "5") (pinfunction "2_5") (pintype "passive"))
      (node (ref "P16_R15N") (pin "2") (pinfunction "2_2") (pintype "passive"))
      (node (ref "P16_R15N") (pin "3") (pinfunction "2_3") (pintype "passive"))
      (node (ref "P16_R15N") (pin "4") (pinfunction "2_4") (pintype "passive"))
      (node (ref "P16_R15N") (pin "5") (pinfunction "2_5") (pintype "passive"))
      (node (ref "P9") (pin "2") (pinfunction "2_2") (pintype "passive"))
      (node (ref "P9") (pin "3") (pinfunction "2_3") (pintype "passive"))
      (node (ref "P9") (pin "4") (pinfunction "2_4") (pintype "passive"))
      (node (ref "P9") (pin "5") (pinfunction "2_5") (pintype "passive"))
      (node (ref "R1") (pin "1") (pinfunction "A_1") (pintype "passive"))
      (node (ref "R100") (pin "P$1") (pinfunction "1_P$1") (pintype "passive"))
      (node (ref "R10_B16P") (pin "2") (pinfunction "2_2") (pintype "passive"))
      (node (ref "R10_B16P") (pin "3") (pinfunction "2_3") (pintype "passive"))
      (node (ref "R10_B16P") (pin "4") (pinfunction "2_4") (pintype "passive"))
      (node (ref "R10_B16P") (pin "5") (pinfunction "2_5") (pintype "passive"))
      (node (ref "R11") (pin "P$1") (pinfunction "1_P$1") (pintype "passive"))
      (node (ref "R111") (pin "P$1") (pinfunction "1_P$1") (pintype "passive"))
      (node (ref "R12_B18P") (pin "2") (pinfunction "2_2") (pintype "passive"))
      (node (ref "R12_B18P") (pin "3") (pinfunction "2_3") (pintype "passive"))
      (node (ref "R12_B18P") (pin "4") (pinfunction "2_4") (pintype "passive"))
      (node (ref "R12_B18P") (pin "5") (pinfunction "2_5") (pintype "passive"))
      (node (ref "R13_B20P") (pin "2") (pinfunction "2_2") (pintype "passive"))
      (node (ref "R13_B20P") (pin "3") (pinfunction "2_3") (pintype "passive"))
      (node (ref "R13_B20P") (pin "4") (pinfunction "2_4") (pintype "passive"))
      (node (ref "R13_B20P") (pin "5") (pinfunction "2_5") (pintype "passive"))
      (node (ref "R141") (pin "P$1") (pinfunction "1_P$1") (pintype "passive"))
      (node (ref "R14_CLKOUT_4N") (pin "2") (pinfunction "2_2") (pintype "passive"))
      (node (ref "R14_CLKOUT_4N") (pin "3") (pinfunction "2_3") (pintype "passive"))
      (node (ref "R14_CLKOUT_4N") (pin "4") (pinfunction "2_4") (pintype "passive"))
      (node (ref "R14_CLKOUT_4N") (pin "5") (pinfunction "2_5") (pintype "passive"))
      (node (ref "R15") (pin "P$1") (pinfunction "1_P$1") (pintype "passive"))
      (node (ref "R161") (pin "P$1") (pinfunction "1_P$1") (pintype "passive"))
      (node (ref "R16_R15P") (pin "2") (pinfunction "2_2") (pintype "passive"))
      (node (ref "R16_R15P") (pin "3") (pinfunction "2_3") (pintype "passive"))
      (node (ref "R16_R15P") (pin "4") (pinfunction "2_4") (pintype "passive"))
      (node (ref "R16_R15P") (pin "5") (pinfunction "2_5") (pintype "passive"))
      (node (ref "R18") (pin "P$1") (pinfunction "1_P$1") (pintype "passive"))
      (node (ref "R19") (pin "P$1") (pinfunction "1_P$1") (pintype "passive"))
      (node (ref "R2") (pin "1") (pinfunction "A_1") (pintype "passive"))
      (node (ref "R20") (pin "P$1") (pinfunction "1_P$1") (pintype "passive"))
      (node (ref "R21") (pin "P$1") (pinfunction "1_P$1") (pintype "passive"))
      (node (ref "R22") (pin "P$1") (pinfunction "1_P$1") (pintype "passive"))
      (node (ref "R23") (pin "P$1") (pinfunction "1_P$1") (pintype "passive"))
      (node (ref "R24") (pin "P$1") (pinfunction "1_P$1") (pintype "passive"))
      (node (ref "R25") (pin "P$1") (pinfunction "1_P$1") (pintype "passive"))
      (node (ref "R26") (pin "P$1") (pinfunction "1_P$1") (pintype "passive"))
      (node (ref "R27") (pin "P$1") (pinfunction "1_P$1") (pintype "passive"))
      (node (ref "R28") (pin "P$1") (pinfunction "1_P$1") (pintype "passive"))
      (node (ref "R29") (pin "P$1") (pinfunction "1_P$1") (pintype "passive"))
      (node (ref "R3") (pin "1") (pinfunction "A_1") (pintype "passive"))
      (node (ref "R30") (pin "P$1") (pinfunction "1_P$1") (pintype "passive"))
      (node (ref "R31") (pin "P$1") (pinfunction "1_P$1") (pintype "passive"))
      (node (ref "R32") (pin "P$1") (pinfunction "1_P$1") (pintype "passive"))
      (node (ref "R33") (pin "P$1") (pinfunction "1_P$1") (pintype "passive"))
      (node (ref "R35") (pin "P$1") (pinfunction "1_P$1") (pintype "passive"))
      (node (ref "R39") (pin "P$1") (pinfunction "1_P$1") (pintype "passive"))
      (node (ref "R4") (pin "P$1") (pinfunction "1_P$1") (pintype "passive"))
      (node (ref "R40") (pin "P$1") (pinfunction "1_P$1") (pintype "passive"))
      (node (ref "R41") (pin "P$1") (pinfunction "1_P$1") (pintype "passive"))
      (node (ref "R43") (pin "P$1") (pinfunction "1_P$1") (pintype "passive"))
      (node (ref "R45") (pin "P$1") (pinfunction "1_P$1") (pintype "passive"))
      (node (ref "R46") (pin "P$1") (pinfunction "1_P$1") (pintype "passive"))
      (node (ref "R47") (pin "P$1") (pinfunction "1_P$1") (pintype "passive"))
      (node (ref "R49") (pin "P$1") (pinfunction "1_P$1") (pintype "passive"))
      (node (ref "R5") (pin "P$1") (pinfunction "1_P$1") (pintype "passive"))
      (node (ref "R50") (pin "P$1") (pinfunction "1_P$1") (pintype "passive"))
      (node (ref "R51") (pin "P$1") (pinfunction "1_P$1") (pintype "passive"))
      (node (ref "R52") (pin "P$1") (pinfunction "1_P$1") (pintype "passive"))
      (node (ref "R53") (pin "P$1") (pinfunction "1_P$1") (pintype "passive"))
      (node (ref "R6") (pin "P$1") (pinfunction "1_P$1") (pintype "passive"))
      (node (ref "R7") (pin "1") (pinfunction "A_1") (pintype "passive"))
      (node (ref "R8") (pin "2") (pinfunction "2_2") (pintype "passive"))
      (node (ref "R9") (pin "P$1") (pinfunction "1_P$1") (pintype "passive"))
      (node (ref "R91") (pin "P$1") (pinfunction "1_P$1") (pintype "passive"))
      (node (ref "R9CLK_7P") (pin "2") (pinfunction "2_2") (pintype "passive"))
      (node (ref "R9CLK_7P") (pin "3") (pinfunction "2_3") (pintype "passive"))
      (node (ref "R9CLK_7P") (pin "4") (pinfunction "2_4") (pintype "passive"))
      (node (ref "R9CLK_7P") (pin "5") (pinfunction "2_5") (pintype "passive"))
      (node (ref "SV1") (pin "12") (pinfunction "12_12") (pintype "passive"))
      (node (ref "SV1") (pin "30") (pinfunction "30_30") (pintype "passive"))
      (node (ref "SV2") (pin "12") (pinfunction "12_12") (pintype "passive"))
      (node (ref "SV2") (pin "30") (pinfunction "30_30") (pintype "passive"))
      (node (ref "T10_B16N") (pin "2") (pinfunction "2_2") (pintype "passive"))
      (node (ref "T10_B16N") (pin "3") (pinfunction "2_3") (pintype "passive"))
      (node (ref "T10_B16N") (pin "4") (pinfunction "2_4") (pintype "passive"))
      (node (ref "T10_B16N") (pin "5") (pinfunction "2_5") (pintype "passive"))
      (node (ref "T12_B18N") (pin "2") (pinfunction "2_2") (pintype "passive"))
      (node (ref "T12_B18N") (pin "3") (pinfunction "2_3") (pintype "passive"))
      (node (ref "T12_B18N") (pin "4") (pinfunction "2_4") (pintype "passive"))
      (node (ref "T12_B18N") (pin "5") (pinfunction "2_5") (pintype "passive"))
      (node (ref "T13_B20N") (pin "2") (pinfunction "2_2") (pintype "passive"))
      (node (ref "T13_B20N") (pin "3") (pinfunction "2_3") (pintype "passive"))
      (node (ref "T13_B20N") (pin "4") (pinfunction "2_4") (pintype "passive"))
      (node (ref "T13_B20N") (pin "5") (pinfunction "2_5") (pintype "passive"))
      (node (ref "T14_B23P") (pin "2") (pinfunction "2_2") (pintype "passive"))
      (node (ref "T14_B23P") (pin "3") (pinfunction "2_3") (pintype "passive"))
      (node (ref "T14_B23P") (pin "4") (pinfunction "2_4") (pintype "passive"))
      (node (ref "T14_B23P") (pin "5") (pinfunction "2_5") (pintype "passive"))
      (node (ref "T15_B23N") (pin "2") (pinfunction "2_2") (pintype "passive"))
      (node (ref "T15_B23N") (pin "3") (pinfunction "2_3") (pintype "passive"))
      (node (ref "T15_B23N") (pin "4") (pinfunction "2_4") (pintype "passive"))
      (node (ref "T15_B23N") (pin "5") (pinfunction "2_5") (pintype "passive"))
      (node (ref "T9CLK_7N") (pin "2") (pinfunction "2_2") (pintype "passive"))
      (node (ref "T9CLK_7N") (pin "3") (pinfunction "2_3") (pintype "passive"))
      (node (ref "T9CLK_7N") (pin "4") (pinfunction "2_4") (pintype "passive"))
      (node (ref "T9CLK_7N") (pin "5") (pinfunction "2_5") (pintype "passive"))
      (node (ref "VSLUE") (pin "10") (pinfunction "GND_10") (pintype "power_in"))
      (node (ref "VSLUE11") (pin "10") (pinfunction "GND_10") (pintype "power_in"))
      (node (ref "VSLUE2") (pin "10") (pinfunction "GND_10") (pintype "power_in"))
      (node (ref "VSLUE3") (pin "10") (pinfunction "GND_10") (pintype "power_in"))
      (node (ref "VSLUE4") (pin "10") (pinfunction "GND_10") (pintype "power_in"))
      (node (ref "VSLUE5") (pin "10") (pinfunction "GND_10") (pintype "power_in"))
      (node (ref "VSLUE6") (pin "10") (pinfunction "GND_10") (pintype "power_in"))
      (node (ref "VSLUE7") (pin "10") (pinfunction "GND_10") (pintype "power_in"))
      (node (ref "VSLUE8") (pin "10") (pinfunction "GND_10") (pintype "power_in"))
      (node (ref "VSLUE9") (pin "10") (pinfunction "GND_10") (pintype "power_in"))
    )
    (net (code "108") (name "Net-(IC1-CAP+)") (class "Default")
      (node (ref "C1") (pin "1") (pinfunction "1_1") (pintype "passive"))
      (node (ref "IC1") (pin "2") (pinfunction "CAP+_2") (pintype "passive"))
    )
    (net (code "109") (name "Net-(IC1-CAP-)") (class "Default")
      (node (ref "C1") (pin "2") (pinfunction "2_2") (pintype "passive"))
      (node (ref "IC1") (pin "4") (pinfunction "CAP-_4") (pintype "passive"))
    )
    (net (code "110") (name "Net-(IC2-CAP+)") (class "Default")
      (node (ref "C7") (pin "1") (pinfunction "1_1") (pintype "passive"))
      (node (ref "IC2") (pin "2") (pinfunction "CAP+_2") (pintype "passive"))
    )
    (net (code "111") (name "Net-(IC2-CAP-)") (class "Default")
      (node (ref "C7") (pin "2") (pinfunction "2_2") (pintype "passive"))
      (node (ref "IC2") (pin "4") (pinfunction "CAP-_4") (pintype "passive"))
    )
    (net (code "112") (name "Net-(IC3-CAP+)") (class "Default")
      (node (ref "C12") (pin "1") (pinfunction "1_1") (pintype "passive"))
      (node (ref "IC3") (pin "2") (pinfunction "CAP+_2") (pintype "passive"))
    )
    (net (code "113") (name "Net-(IC3-CAP-)") (class "Default")
      (node (ref "C12") (pin "2") (pinfunction "2_2") (pintype "passive"))
      (node (ref "IC3") (pin "4") (pinfunction "CAP-_4") (pintype "passive"))
    )
    (net (code "114") (name "Net-(IC4-CAP+)") (class "Default")
      (node (ref "C17") (pin "1") (pinfunction "1_1") (pintype "passive"))
      (node (ref "IC4") (pin "2") (pinfunction "CAP+_2") (pintype "passive"))
    )
    (net (code "115") (name "Net-(IC4-CAP-)") (class "Default")
      (node (ref "C17") (pin "2") (pinfunction "2_2") (pintype "passive"))
      (node (ref "IC4") (pin "4") (pinfunction "CAP-_4") (pintype "passive"))
    )
    (net (code "116") (name "Net-(LED1-PadC)") (class "Default")
      (node (ref "LED1") (pin "C") (pinfunction "C_C") (pintype "passive"))
      (node (ref "R8") (pin "1") (pinfunction "1_1") (pintype "passive"))
    )
    (net (code "117") (name "Net-(R1-E)") (class "Default")
      (node (ref "R1") (pin "3") (pinfunction "E_3") (pintype "passive"))
      (node (ref "R10") (pin "P$1") (pinfunction "1_P$1") (pintype "passive"))
    )
    (net (code "118") (name "Net-(R12-1)") (class "Default")
      (node (ref "R12") (pin "P$1") (pinfunction "1_P$1") (pintype "passive"))
      (node (ref "R2") (pin "3") (pinfunction "E_3") (pintype "passive"))
    )
    (net (code "119") (name "Net-(R13-1)") (class "Default")
      (node (ref "R13") (pin "P$1") (pinfunction "1_P$1") (pintype "passive"))
      (node (ref "R3") (pin "3") (pinfunction "E_3") (pintype "passive"))
    )
    (net (code "120") (name "Net-(R14-1)") (class "Default")
      (node (ref "R14") (pin "P$1") (pinfunction "1_P$1") (pintype "passive"))
      (node (ref "R7") (pin "3") (pinfunction "E_3") (pintype "passive"))
    )
    (net (code "121") (name "Net-(VSLUE-1Y1)") (class "Default")
      (node (ref "J14") (pin "1") (pinfunction "1_1") (pintype "passive"))
      (node (ref "OJ1") (pin "1") (pinfunction "1_1") (pintype "bidirectional"))
      (node (ref "VSLUE") (pin "16") (pinfunction "1Y2_16") (pintype "output"))
      (node (ref "VSLUE") (pin "18") (pinfunction "1Y1_18") (pintype "output"))
    )
    (net (code "122") (name "Net-(VSLUE-1Y3)") (class "Default")
      (node (ref "D11") (pin "1") (pinfunction "1_1") (pintype "passive"))
      (node (ref "OJ2") (pin "1") (pinfunction "1_1") (pintype "bidirectional"))
      (node (ref "VSLUE") (pin "12") (pinfunction "1Y4_12") (pintype "output"))
      (node (ref "VSLUE") (pin "14") (pinfunction "1Y3_14") (pintype "output"))
    )
    (net (code "123") (name "Net-(VSLUE-2Y1)") (class "Default")
      (node (ref "B11") (pin "1") (pinfunction "1_1") (pintype "passive"))
      (node (ref "OJ3") (pin "1") (pinfunction "1_1") (pintype "bidirectional"))
      (node (ref "VSLUE") (pin "7") (pinfunction "2Y2_7") (pintype "output"))
      (node (ref "VSLUE") (pin "9") (pinfunction "2Y1_9") (pintype "output"))
    )
    (net (code "124") (name "Net-(VSLUE-2Y3)") (class "Default")
      (node (ref "E10") (pin "1") (pinfunction "1_1") (pintype "passive"))
      (node (ref "OJ4") (pin "1") (pinfunction "1_1") (pintype "bidirectional"))
      (node (ref "VSLUE") (pin "3") (pinfunction "2Y4_3") (pintype "output"))
      (node (ref "VSLUE") (pin "5") (pinfunction "2Y3_5") (pintype "output"))
    )
    (net (code "125") (name "Net-(VSLUE2-1Y1)") (class "Default")
      (node (ref "N12") (pin "1") (pinfunction "1_1") (pintype "passive"))
      (node (ref "OJ20") (pin "1") (pinfunction "1_1") (pintype "bidirectional"))
      (node (ref "VSLUE2") (pin "16") (pinfunction "1Y2_16") (pintype "output"))
      (node (ref "VSLUE2") (pin "18") (pinfunction "1Y1_18") (pintype "output"))
    )
    (net (code "126") (name "Net-(VSLUE2-1Y3)") (class "Default")
      (node (ref "E9") (pin "1") (pinfunction "1_1") (pintype "passive"))
      (node (ref "OJ19") (pin "1") (pinfunction "1_1") (pintype "bidirectional"))
      (node (ref "VSLUE2") (pin "12") (pinfunction "1Y4_12") (pintype "output"))
      (node (ref "VSLUE2") (pin "14") (pinfunction "1Y3_14") (pintype "output"))
    )
    (net (code "127") (name "Net-(VSLUE2-2Y1)") (class "Default")
      (node (ref "B16") (pin "1") (pinfunction "1_1") (pintype "passive"))
      (node (ref "OJ18") (pin "1") (pinfunction "1_1") (pintype "bidirectional"))
      (node (ref "VSLUE2") (pin "7") (pinfunction "2Y2_7") (pintype "output"))
      (node (ref "VSLUE2") (pin "9") (pinfunction "2Y1_9") (pintype "output"))
    )
    (net (code "128") (name "Net-(VSLUE2-2Y3)") (class "Default")
      (node (ref "D8") (pin "1") (pinfunction "1_1") (pintype "passive"))
      (node (ref "OJ17") (pin "1") (pinfunction "1_1") (pintype "bidirectional"))
      (node (ref "VSLUE2") (pin "3") (pinfunction "2Y4_3") (pintype "output"))
      (node (ref "VSLUE2") (pin "5") (pinfunction "2Y3_5") (pintype "output"))
    )
    (net (code "129") (name "Net-(VSLUE3-1Y1)") (class "Default")
      (node (ref "C15") (pin "1") (pinfunction "1_1") (pintype "passive"))
      (node (ref "OJ28") (pin "1") (pinfunction "1_1") (pintype "bidirectional"))
      (node (ref "VSLUE3") (pin "16") (pinfunction "1Y2_16") (pintype "output"))
      (node (ref "VSLUE3") (pin "18") (pinfunction "1Y1_18") (pintype "output"))
    )
    (net (code "130") (name "Net-(VSLUE3-1Y3)") (class "Default")
      (node (ref "C14") (pin "1") (pinfunction "1_1") (pintype "passive"))
      (node (ref "OJ27") (pin "1") (pinfunction "1_1") (pintype "bidirectional"))
      (node (ref "VSLUE3") (pin "12") (pinfunction "1Y4_12") (pintype "output"))
      (node (ref "VSLUE3") (pin "14") (pinfunction "1Y3_14") (pintype "output"))
    )
    (net (code "131") (name "Net-(VSLUE3-2Y1)") (class "Default")
      (node (ref "F14") (pin "1") (pinfunction "1_1") (pintype "passive"))
      (node (ref "OJ26") (pin "1") (pinfunction "1_1") (pintype "bidirectional"))
      (node (ref "VSLUE3") (pin "7") (pinfunction "2Y2_7") (pintype "output"))
      (node (ref "VSLUE3") (pin "9") (pinfunction "2Y1_9") (pintype "output"))
    )
    (net (code "132") (name "Net-(VSLUE3-2Y3)") (class "Default")
      (node (ref "D15") (pin "1") (pinfunction "1_1") (pintype "passive"))
      (node (ref "OJ25") (pin "1") (pinfunction "1_1") (pintype "bidirectional"))
      (node (ref "VSLUE3") (pin "3") (pinfunction "2Y4_3") (pintype "output"))
      (node (ref "VSLUE3") (pin "5") (pinfunction "2Y3_5") (pintype "output"))
    )
    (net (code "133") (name "Net-(VSLUE4-1Y1)") (class "Default")
      (node (ref "D16") (pin "1") (pinfunction "1_1") (pintype "passive"))
      (node (ref "OJ36") (pin "1") (pinfunction "1_1") (pintype "bidirectional"))
      (node (ref "VSLUE4") (pin "16") (pinfunction "1Y2_16") (pintype "output"))
      (node (ref "VSLUE4") (pin "18") (pinfunction "1Y1_18") (pintype "output"))
    )
    (net (code "134") (name "Net-(VSLUE4-1Y3)") (class "Default")
      (node (ref "D14") (pin "1") (pinfunction "1_1") (pintype "passive"))
      (node (ref "OJ35") (pin "1") (pinfunction "1_1") (pintype "bidirectional"))
      (node (ref "VSLUE4") (pin "12") (pinfunction "1Y4_12") (pintype "output"))
      (node (ref "VSLUE4") (pin "14") (pinfunction "1Y3_14") (pintype "output"))
    )
    (net (code "135") (name "Net-(VSLUE4-2Y1)") (class "Default")
      (node (ref "F16") (pin "1") (pinfunction "1_1") (pintype "passive"))
      (node (ref "OJ34") (pin "1") (pinfunction "1_1") (pintype "bidirectional"))
      (node (ref "VSLUE4") (pin "7") (pinfunction "2Y2_7") (pintype "output"))
      (node (ref "VSLUE4") (pin "9") (pinfunction "2Y1_9") (pintype "output"))
    )
    (net (code "136") (name "Net-(VSLUE4-2Y3)") (class "Default")
      (node (ref "F15") (pin "1") (pinfunction "1_1") (pintype "passive"))
      (node (ref "OJ33") (pin "1") (pinfunction "1_1") (pintype "bidirectional"))
      (node (ref "VSLUE4") (pin "3") (pinfunction "2Y4_3") (pintype "output"))
      (node (ref "VSLUE4") (pin "5") (pinfunction "2Y3_5") (pintype "output"))
    )
    (net (code "137") (name "Net-(VSLUE5-1Y1)") (class "Default")
      (node (ref "B6") (pin "1") (pinfunction "1_1") (pintype "passive"))
      (node (ref "OJ44") (pin "1") (pinfunction "1_1") (pintype "bidirectional"))
      (node (ref "VSLUE5") (pin "16") (pinfunction "1Y2_16") (pintype "output"))
      (node (ref "VSLUE5") (pin "18") (pinfunction "1Y1_18") (pintype "output"))
    )
    (net (code "138") (name "Net-(VSLUE5-1Y3)") (class "Default")
      (node (ref "A6") (pin "1") (pinfunction "1_1") (pintype "passive"))
      (node (ref "OJ43") (pin "1") (pinfunction "1_1") (pintype "bidirectional"))
      (node (ref "VSLUE5") (pin "12") (pinfunction "1Y4_12") (pintype "output"))
      (node (ref "VSLUE5") (pin "14") (pinfunction "1Y3_14") (pintype "output"))
    )
    (net (code "139") (name "Net-(VSLUE5-2Y1)") (class "Default")
      (node (ref "N11") (pin "1") (pinfunction "1_1") (pintype "passive"))
      (node (ref "OJ42") (pin "1") (pinfunction "1_1") (pintype "bidirectional"))
      (node (ref "VSLUE5") (pin "7") (pinfunction "2Y2_7") (pintype "output"))
      (node (ref "VSLUE5") (pin "9") (pinfunction "2Y1_9") (pintype "output"))
    )
    (net (code "140") (name "Net-(VSLUE5-2Y3)") (class "Default")
      (node (ref "OJ41") (pin "1") (pinfunction "1_1") (pintype "bidirectional"))
      (node (ref "P9") (pin "1") (pinfunction "1_1") (pintype "passive"))
      (node (ref "VSLUE5") (pin "3") (pinfunction "2Y4_3") (pintype "output"))
      (node (ref "VSLUE5") (pin "5") (pinfunction "2Y3_5") (pintype "output"))
    )
    (net (code "141") (name "Net-(VSLUE6-1Y1)") (class "Default")
      (node (ref "D6") (pin "1") (pinfunction "1_1") (pintype "passive"))
      (node (ref "OJ52") (pin "1") (pinfunction "1_1") (pintype "bidirectional"))
      (node (ref "VSLUE6") (pin "16") (pinfunction "1Y2_16") (pintype "output"))
      (node (ref "VSLUE6") (pin "18") (pinfunction "1Y1_18") (pintype "output"))
    )
    (net (code "142") (name "Net-(VSLUE6-1Y3)") (class "Default")
      (node (ref "C6") (pin "1") (pinfunction "1_1") (pintype "passive"))
      (node (ref "OJ51") (pin "1") (pinfunction "1_1") (pintype "bidirectional"))
      (node (ref "VSLUE6") (pin "12") (pinfunction "1Y4_12") (pintype "output"))
      (node (ref "VSLUE6") (pin "14") (pinfunction "1Y3_14") (pintype "output"))
    )
    (net (code "143") (name "Net-(VSLUE6-2Y1)") (class "Default")
      (node (ref "E6") (pin "1") (pinfunction "1_1") (pintype "passive"))
      (node (ref "OJ50") (pin "1") (pinfunction "1_1") (pintype "bidirectional"))
      (node (ref "VSLUE6") (pin "7") (pinfunction "2Y2_7") (pintype "output"))
      (node (ref "VSLUE6") (pin "9") (pinfunction "2Y1_9") (pintype "output"))
    )
    (net (code "144") (name "Net-(VSLUE6-2Y3)") (class "Default")
      (node (ref "C8") (pin "1") (pinfunction "1_1") (pintype "passive"))
      (node (ref "OJ49") (pin "1") (pinfunction "1_1") (pintype "bidirectional"))
      (node (ref "VSLUE6") (pin "3") (pinfunction "2Y4_3") (pintype "output"))
      (node (ref "VSLUE6") (pin "5") (pinfunction "2Y3_5") (pintype "output"))
    )
    (net (code "145") (name "Net-(VSLUE7-1Y1)") (class "Default")
      (node (ref "C16") (pin "1") (pinfunction "1_1") (pintype "passive"))
      (node (ref "OJ60") (pin "1") (pinfunction "1_1") (pintype "bidirectional"))
      (node (ref "VSLUE7") (pin "16") (pinfunction "1Y2_16") (pintype "output"))
      (node (ref "VSLUE7") (pin "18") (pinfunction "1Y1_18") (pintype "output"))
    )
    (net (code "146") (name "Net-(VSLUE7-1Y3)") (class "Default")
      (node (ref "E7") (pin "1") (pinfunction "1_1") (pintype "passive"))
      (node (ref "OJ59") (pin "1") (pinfunction "1_1") (pintype "bidirectional"))
      (node (ref "VSLUE7") (pin "12") (pinfunction "1Y4_12") (pintype "output"))
      (node (ref "VSLUE7") (pin "14") (pinfunction "1Y3_14") (pintype "output"))
    )
    (net (code "147") (name "Net-(VSLUE7-2Y1)") (class "Default")
      (node (ref "F9") (pin "1") (pinfunction "1_1") (pintype "passive"))
      (node (ref "OJ58") (pin "1") (pinfunction "1_1") (pintype "bidirectional"))
      (node (ref "VSLUE7") (pin "7") (pinfunction "2Y2_7") (pintype "output"))
      (node (ref "VSLUE7") (pin "9") (pinfunction "2Y1_9") (pintype "output"))
    )
    (net (code "148") (name "Net-(VSLUE7-2Y3)") (class "Default")
      (node (ref "OJ57") (pin "1") (pinfunction "1_1") (pintype "bidirectional"))
      (node (ref "P15") (pin "1") (pinfunction "1_1") (pintype "passive"))
      (node (ref "VSLUE7") (pin "3") (pinfunction "2Y4_3") (pintype "output"))
      (node (ref "VSLUE7") (pin "5") (pinfunction "2Y3_5") (pintype "output"))
    )
    (net (code "149") (name "Net-(VSLUE8-1Y1)") (class "Default")
      (node (ref "B5") (pin "1") (pinfunction "1_1") (pintype "passive"))
      (node (ref "OJ68") (pin "1") (pinfunction "1_1") (pintype "bidirectional"))
      (node (ref "VSLUE8") (pin "16") (pinfunction "1Y2_16") (pintype "output"))
      (node (ref "VSLUE8") (pin "18") (pinfunction "1Y1_18") (pintype "output"))
    )
    (net (code "150") (name "Net-(VSLUE8-1Y3)") (class "Default")
      (node (ref "A5") (pin "1") (pinfunction "1_1") (pintype "passive"))
      (node (ref "OJ67") (pin "1") (pinfunction "1_1") (pintype "bidirectional"))
      (node (ref "VSLUE8") (pin "12") (pinfunction "1Y4_12") (pintype "output"))
      (node (ref "VSLUE8") (pin "14") (pinfunction "1Y3_14") (pintype "output"))
    )
    (net (code "151") (name "Net-(VSLUE8-2Y1)") (class "Default")
      (node (ref "N14") (pin "1") (pinfunction "1_1") (pintype "passive"))
      (node (ref "OJ66") (pin "1") (pinfunction "1_1") (pintype "bidirectional"))
      (node (ref "VSLUE8") (pin "7") (pinfunction "2Y2_7") (pintype "output"))
      (node (ref "VSLUE8") (pin "9") (pinfunction "2Y1_9") (pintype "output"))
    )
    (net (code "152") (name "Net-(VSLUE8-2Y3)") (class "Default")
      (node (ref "D5") (pin "1") (pinfunction "1_1") (pintype "passive"))
      (node (ref "OJ65") (pin "1") (pinfunction "1_1") (pintype "bidirectional"))
      (node (ref "VSLUE8") (pin "3") (pinfunction "2Y4_3") (pintype "output"))
      (node (ref "VSLUE8") (pin "5") (pinfunction "2Y3_5") (pintype "output"))
    )
    (net (code "153") (name "Net-(VSLUE9-1Y1)") (class "Default")
      (node (ref "E11") (pin "1") (pinfunction "1_1") (pintype "passive"))
      (node (ref "OJ76") (pin "1") (pinfunction "1_1") (pintype "bidirectional"))
      (node (ref "VSLUE9") (pin "16") (pinfunction "1Y2_16") (pintype "output"))
      (node (ref "VSLUE9") (pin "18") (pinfunction "1Y1_18") (pintype "output"))
    )
    (net (code "154") (name "Net-(VSLUE9-1Y3)") (class "Default")
      (node (ref "OJ75") (pin "1") (pinfunction "1_1") (pintype "bidirectional"))
      (node (ref "P11") (pin "1") (pinfunction "1_1") (pintype "passive"))
      (node (ref "VSLUE9") (pin "12") (pinfunction "1Y4_12") (pintype "output"))
      (node (ref "VSLUE9") (pin "14") (pinfunction "1Y3_14") (pintype "output"))
    )
    (net (code "155") (name "Net-(VSLUE9-2Y1)") (class "Default")
      (node (ref "C11") (pin "1") (pinfunction "1_1") (pintype "passive"))
      (node (ref "OJ74") (pin "1") (pinfunction "1_1") (pintype "bidirectional"))
      (node (ref "VSLUE9") (pin "7") (pinfunction "2Y2_7") (pintype "output"))
      (node (ref "VSLUE9") (pin "9") (pinfunction "2Y1_9") (pintype "output"))
    )
    (net (code "156") (name "Net-(VSLUE9-2Y3)") (class "Default")
      (node (ref "J13") (pin "1") (pinfunction "1_1") (pintype "passive"))
      (node (ref "OJ73") (pin "1") (pinfunction "1_1") (pintype "bidirectional"))
      (node (ref "VSLUE9") (pin "3") (pinfunction "2Y4_3") (pintype "output"))
      (node (ref "VSLUE9") (pin "5") (pinfunction "2Y3_5") (pintype "output"))
    )
    (net (code "157") (name "Net-(VSLUE11-1Y1)") (class "Default")
      (node (ref "D12") (pin "1") (pinfunction "1_1") (pintype "passive"))
      (node (ref "OJ92") (pin "1") (pinfunction "1_1") (pintype "bidirectional"))
      (node (ref "VSLUE11") (pin "16") (pinfunction "1Y2_16") (pintype "output"))
      (node (ref "VSLUE11") (pin "18") (pinfunction "1Y1_18") (pintype "output"))
    )
    (net (code "158") (name "Net-(VSLUE11-1Y3)") (class "Default")
      (node (ref "B3") (pin "1") (pinfunction "1_1") (pintype "passive"))
      (node (ref "OJ91") (pin "1") (pinfunction "1_1") (pintype "bidirectional"))
      (node (ref "VSLUE11") (pin "12") (pinfunction "1Y4_12") (pintype "output"))
      (node (ref "VSLUE11") (pin "14") (pinfunction "1Y3_14") (pintype "output"))
    )
    (net (code "159") (name "Net-(VSLUE11-2Y1)") (class "Default")
      (node (ref "B4") (pin "1") (pinfunction "1_1") (pintype "passive"))
      (node (ref "OJ90") (pin "1") (pinfunction "1_1") (pintype "bidirectional"))
      (node (ref "VSLUE11") (pin "7") (pinfunction "2Y2_7") (pintype "output"))
      (node (ref "VSLUE11") (pin "9") (pinfunction "2Y1_9") (pintype "output"))
    )
    (net (code "160") (name "Net-(VSLUE11-2Y3)") (class "Default")
      (node (ref "A4") (pin "1") (pinfunction "1_1") (pintype "passive"))
      (node (ref "OJ89") (pin "1") (pinfunction "1_1") (pintype "bidirectional"))
      (node (ref "VSLUE11") (pin "3") (pinfunction "2Y4_3") (pintype "output"))
      (node (ref "VSLUE11") (pin "5") (pinfunction "2Y3_5") (pintype "output"))
    )
    (net (code "161") (name "unconnected-(IC1-LV-Pad6)") (class "Default")
      (node (ref "IC1") (pin "6") (pinfunction "LV_6") (pintype "passive"))
    )
    (net (code "162") (name "unconnected-(IC1-NC-Pad1)") (class "Default")
      (node (ref "IC1") (pin "1") (pinfunction "NC_1") (pintype "no_connect"))
    )
    (net (code "163") (name "unconnected-(IC1-OSC-Pad7)") (class "Default")
      (node (ref "IC1") (pin "7") (pinfunction "OSC_7") (pintype "output"))
    )
    (net (code "164") (name "unconnected-(IC2-LV-Pad6)") (class "Default")
      (node (ref "IC2") (pin "6") (pinfunction "LV_6") (pintype "passive"))
    )
    (net (code "165") (name "unconnected-(IC2-NC-Pad1)") (class "Default")
      (node (ref "IC2") (pin "1") (pinfunction "NC_1") (pintype "no_connect"))
    )
    (net (code "166") (name "unconnected-(IC2-OSC-Pad7)") (class "Default")
      (node (ref "IC2") (pin "7") (pinfunction "OSC_7") (pintype "output"))
    )
    (net (code "167") (name "unconnected-(IC3-LV-Pad6)") (class "Default")
      (node (ref "IC3") (pin "6") (pinfunction "LV_6") (pintype "passive"))
    )
    (net (code "168") (name "unconnected-(IC3-NC-Pad1)") (class "Default")
      (node (ref "IC3") (pin "1") (pinfunction "NC_1") (pintype "no_connect"))
    )
    (net (code "169") (name "unconnected-(IC3-OSC-Pad7)") (class "Default")
      (node (ref "IC3") (pin "7") (pinfunction "OSC_7") (pintype "output"))
    )
    (net (code "170") (name "unconnected-(IC4-LV-Pad6)") (class "Default")
      (node (ref "IC4") (pin "6") (pinfunction "LV_6") (pintype "passive"))
    )
    (net (code "171") (name "unconnected-(IC4-NC-Pad1)") (class "Default")
      (node (ref "IC4") (pin "1") (pinfunction "NC_1") (pintype "no_connect"))
    )
    (net (code "172") (name "unconnected-(IC4-OSC-Pad7)") (class "Default")
      (node (ref "IC4") (pin "7") (pinfunction "OSC_7") (pintype "output"))
    )
    (net (code "173") (name "unconnected-(J2-Pad1)") (class "Default")
      (node (ref "J2") (pin "1") (pinfunction "1_1") (pintype "passive"))
    )
    (net (code "174") (name "unconnected-(J2-Pad2)") (class "Default")
      (node (ref "J2") (pin "2") (pinfunction "2_2") (pintype "passive"))
    )
    (net (code "175") (name "unconnected-(J2-Pad3)") (class "Default")
      (node (ref "J2") (pin "3") (pinfunction "3_3") (pintype "passive"))
    )
    (net (code "176") (name "unconnected-(J2-Pad4)") (class "Default")
      (node (ref "J2") (pin "4") (pinfunction "4_4") (pintype "passive"))
    )
    (net (code "177") (name "unconnected-(J2-Pad5)") (class "Default")
      (node (ref "J2") (pin "5") (pinfunction "5_5") (pintype "passive"))
    )
    (net (code "178") (name "unconnected-(J2-Pad6)") (class "Default")
      (node (ref "J2") (pin "6") (pinfunction "6_6") (pintype "passive"))
    )
    (net (code "179") (name "unconnected-(J2-Pad7)") (class "Default")
      (node (ref "J2") (pin "7") (pinfunction "7_7") (pintype "passive"))
    )
    (net (code "180") (name "unconnected-(J2-Pad8)") (class "Default")
      (node (ref "J2") (pin "8") (pinfunction "8_8") (pintype "passive"))
    )
    (net (code "181") (name "unconnected-(J2-Pad9)") (class "Default")
      (node (ref "J2") (pin "9") (pinfunction "9_9") (pintype "passive"))
    )
    (net (code "182") (name "unconnected-(J2-Pad10)") (class "Default")
      (node (ref "J2") (pin "10") (pinfunction "10_10") (pintype "passive"))
    )
    (net (code "183") (name "unconnected-(J2-Pad11)") (class "Default")
      (node (ref "J2") (pin "11") (pinfunction "11_11") (pintype "passive"))
    )
    (net (code "184") (name "unconnected-(J2-Pad12)") (class "Default")
      (node (ref "J2") (pin "12") (pinfunction "12_12") (pintype "passive"))
    )
    (net (code "185") (name "unconnected-(J2-Pad13)") (class "Default")
      (node (ref "J2") (pin "13") (pinfunction "13_13") (pintype "passive"))
    )
    (net (code "186") (name "unconnected-(J2-Pad14)") (class "Default")
      (node (ref "J2") (pin "14") (pinfunction "14_14") (pintype "passive"))
    )
    (net (code "187") (name "unconnected-(J2-Pad15)") (class "Default")
      (node (ref "J2") (pin "15") (pinfunction "15_15") (pintype "passive"))
    )
    (net (code "188") (name "unconnected-(J2-Pad16)") (class "Default")
      (node (ref "J2") (pin "16") (pinfunction "16_16") (pintype "passive"))
    )
    (net (code "189") (name "unconnected-(J2-Pad17)") (class "Default")
      (node (ref "J2") (pin "17") (pinfunction "17_17") (pintype "passive"))
    )
    (net (code "190") (name "unconnected-(J2-Pad18)") (class "Default")
      (node (ref "J2") (pin "18") (pinfunction "18_18") (pintype "passive"))
    )
    (net (code "191") (name "unconnected-(J2-Pad19)") (class "Default")
      (node (ref "J2") (pin "19") (pinfunction "19_19") (pintype "passive"))
    )
    (net (code "192") (name "unconnected-(J2-Pad20)") (class "Default")
      (node (ref "J2") (pin "20") (pinfunction "20_20") (pintype "passive"))
    )
    (net (code "193") (name "unconnected-(J2-Pad21)") (class "Default")
      (node (ref "J2") (pin "21") (pinfunction "21_21") (pintype "passive"))
    )
    (net (code "194") (name "unconnected-(J2-Pad22)") (class "Default")
      (node (ref "J2") (pin "22") (pinfunction "22_22") (pintype "passive"))
    )
    (net (code "195") (name "unconnected-(J2-Pad23)") (class "Default")
      (node (ref "J2") (pin "23") (pinfunction "23_23") (pintype "passive"))
    )
    (net (code "196") (name "unconnected-(J2-Pad24)") (class "Default")
      (node (ref "J2") (pin "24") (pinfunction "24_24") (pintype "passive"))
    )
    (net (code "197") (name "unconnected-(J2-Pad25)") (class "Default")
      (node (ref "J2") (pin "25") (pinfunction "25_25") (pintype "passive"))
    )
    (net (code "198") (name "unconnected-(J2-Pad26)") (class "Default")
      (node (ref "J2") (pin "26") (pinfunction "26_26") (pintype "passive"))
    )
    (net (code "199") (name "unconnected-(J19A-MSV-Pad1-A1)") (class "Default")
      (node (ref "J19") (pin "1-A1") (pinfunction "MSV_1-A1") (pintype "passive"))
    )
    (net (code "200") (name "unconnected-(J19AA-MS-Pad1-A4)") (class "Default")
      (node (ref "J19") (pin "1-A4") (pinfunction "MS_1-A4") (pintype "passive"))
    )
    (net (code "201") (name "unconnected-(J19AB-MS-Pad1-A5)") (class "Default")
      (node (ref "J19") (pin "1-A5") (pinfunction "MS_1-A5") (pintype "passive"))
    )
    (net (code "202") (name "unconnected-(J19AC-MS-Pad1-A6)") (class "Default")
      (node (ref "J19") (pin "1-A6") (pinfunction "MS_1-A6") (pintype "passive"))
    )
    (net (code "203") (name "unconnected-(J19AD-MS-Pad1-A7)") (class "Default")
      (node (ref "J19") (pin "1-A7") (pinfunction "MS_1-A7") (pintype "passive"))
    )
    (net (code "204") (name "unconnected-(J19AE-MS-Pad1-A8)") (class "Default")
      (node (ref "J19") (pin "1-A8") (pinfunction "MS_1-A8") (pintype "passive"))
    )
    (net (code "205") (name "unconnected-(J19AG-MSV-Pad1-C1)") (class "Default")
      (node (ref "J19") (pin "1-C1") (pinfunction "MSV_1-C1") (pintype "passive"))
    )
    (net (code "206") (name "unconnected-(J19AH-MS-Pad1-C10)") (class "Default")
      (node (ref "J19") (pin "1-C10") (pinfunction "MS_1-C10") (pintype "passive"))
    )
    (net (code "207") (name "unconnected-(J19AI-MS-Pad1-C11)") (class "Default")
      (node (ref "J19") (pin "1-C11") (pinfunction "MS_1-C11") (pintype "passive"))
    )
    (net (code "208") (name "unconnected-(J19AJ-MS-Pad1-C12)") (class "Default")
      (node (ref "J19") (pin "1-C12") (pinfunction "MS_1-C12") (pintype "passive"))
    )
    (net (code "209") (name "unconnected-(J19AK-MS-Pad1-C13)") (class "Default")
      (node (ref "J19") (pin "1-C13") (pinfunction "MS_1-C13") (pintype "passive"))
    )
    (net (code "210") (name "unconnected-(J19AL-MS-Pad1-C14)") (class "Default")
      (node (ref "J19") (pin "1-C14") (pinfunction "MS_1-C14") (pintype "passive"))
    )
    (net (code "211") (name "unconnected-(J19AM-MS-Pad1-C15)") (class "Default")
      (node (ref "J19") (pin "1-C15") (pinfunction "MS_1-C15") (pintype "passive"))
    )
    (net (code "212") (name "unconnected-(J19AN-MS-Pad1-C16)") (class "Default")
      (node (ref "J19") (pin "1-C16") (pinfunction "MS_1-C16") (pintype "passive"))
    )
    (net (code "213") (name "unconnected-(J19AO-MS-Pad1-C17)") (class "Default")
      (node (ref "J19") (pin "1-C17") (pinfunction "MS_1-C17") (pintype "passive"))
    )
    (net (code "214") (name "unconnected-(J19AP-MS-Pad1-C18)") (class "Default")
      (node (ref "J19") (pin "1-C18") (pinfunction "MS_1-C18") (pintype "passive"))
    )
    (net (code "215") (name "unconnected-(J19AQ-MS-Pad1-C19)") (class "Default")
      (node (ref "J19") (pin "1-C19") (pinfunction "MS_1-C19") (pintype "passive"))
    )
    (net (code "216") (name "unconnected-(J19AR-MS-Pad1-C2)") (class "Default")
      (node (ref "J19") (pin "1-C2") (pinfunction "MS_1-C2") (pintype "passive"))
    )
    (net (code "217") (name "unconnected-(J19AS-MS-Pad1-C20)") (class "Default")
      (node (ref "J19") (pin "1-C20") (pinfunction "MS_1-C20") (pintype "passive"))
    )
    (net (code "218") (name "unconnected-(J19AT-MS-Pad1-C21)") (class "Default")
      (node (ref "J19") (pin "1-C21") (pinfunction "MS_1-C21") (pintype "passive"))
    )
    (net (code "219") (name "unconnected-(J19AU-MS-Pad1-C22)") (class "Default")
      (node (ref "J19") (pin "1-C22") (pinfunction "MS_1-C22") (pintype "passive"))
    )
    (net (code "220") (name "unconnected-(J19AV-MS-Pad1-C23)") (class "Default")
      (node (ref "J19") (pin "1-C23") (pinfunction "MS_1-C23") (pintype "passive"))
    )
    (net (code "221") (name "unconnected-(J19AW-MS-Pad1-C24)") (class "Default")
      (node (ref "J19") (pin "1-C24") (pinfunction "MS_1-C24") (pintype "passive"))
    )
    (net (code "222") (name "unconnected-(J19AX-MS-Pad1-C25)") (class "Default")
      (node (ref "J19") (pin "1-C25") (pinfunction "MS_1-C25") (pintype "passive"))
    )
    (net (code "223") (name "unconnected-(J19AY-MS-Pad1-C26)") (class "Default")
      (node (ref "J19") (pin "1-C26") (pinfunction "MS_1-C26") (pintype "passive"))
    )
    (net (code "224") (name "unconnected-(J19AZ-MS-Pad1-C27)") (class "Default")
      (node (ref "J19") (pin "1-C27") (pinfunction "MS_1-C27") (pintype "passive"))
    )
    (net (code "225") (name "unconnected-(J19B-MS-Pad1-A10)") (class "Default")
      (node (ref "J19") (pin "1-A10") (pinfunction "MS_1-A10") (pintype "passive"))
    )
    (net (code "226") (name "unconnected-(J19BA-MS-Pad1-C28)") (class "Default")
      (node (ref "J19") (pin "1-C28") (pinfunction "MS_1-C28") (pintype "passive"))
    )
    (net (code "227") (name "unconnected-(J19BB-MS-Pad1-C29)") (class "Default")
      (node (ref "J19") (pin "1-C29") (pinfunction "MS_1-C29") (pintype "passive"))
    )
    (net (code "228") (name "unconnected-(J19BC-MS-Pad1-C3)") (class "Default")
      (node (ref "J19") (pin "1-C3") (pinfunction "MS_1-C3") (pintype "passive"))
    )
    (net (code "229") (name "unconnected-(J19BD-MS-Pad1-C30)") (class "Default")
      (node (ref "J19") (pin "1-C30") (pinfunction "MS_1-C30") (pintype "passive"))
    )
    (net (code "230") (name "unconnected-(J19BE-MS-Pad1-C31)") (class "Default")
      (node (ref "J19") (pin "1-C31") (pinfunction "MS_1-C31") (pintype "passive"))
    )
    (net (code "231") (name "unconnected-(J19BG-MS-Pad1-C4)") (class "Default")
      (node (ref "J19") (pin "1-C4") (pinfunction "MS_1-C4") (pintype "passive"))
    )
    (net (code "232") (name "unconnected-(J19BH-MS-Pad1-C5)") (class "Default")
      (node (ref "J19") (pin "1-C5") (pinfunction "MS_1-C5") (pintype "passive"))
    )
    (net (code "233") (name "unconnected-(J19BI-MS-Pad1-C6)") (class "Default")
      (node (ref "J19") (pin "1-C6") (pinfunction "MS_1-C6") (pintype "passive"))
    )
    (net (code "234") (name "unconnected-(J19BJ-MS-Pad1-C7)") (class "Default")
      (node (ref "J19") (pin "1-C7") (pinfunction "MS_1-C7") (pintype "passive"))
    )
    (net (code "235") (name "unconnected-(J19BK-MS-Pad1-C8)") (class "Default")
      (node (ref "J19") (pin "1-C8") (pinfunction "MS_1-C8") (pintype "passive"))
    )
    (net (code "236") (name "unconnected-(J19BM-MSV-Pad2-A1)") (class "Default")
      (node (ref "J19") (pin "2-A1") (pinfunction "MSV_2-A1") (pintype "passive"))
    )
    (net (code "237") (name "unconnected-(J19BN-MS-Pad2-A10)") (class "Default")
      (node (ref "J19") (pin "2-A10") (pinfunction "MS_2-A10") (pintype "passive"))
    )
    (net (code "238") (name "unconnected-(J19BO-MS-Pad2-A11)") (class "Default")
      (node (ref "J19") (pin "2-A11") (pinfunction "MS_2-A11") (pintype "passive"))
    )
    (net (code "239") (name "unconnected-(J19BP-MS-Pad2-A12)") (class "Default")
      (node (ref "J19") (pin "2-A12") (pinfunction "MS_2-A12") (pintype "passive"))
    )
    (net (code "240") (name "unconnected-(J19BQ-MS-Pad2-A13)") (class "Default")
      (node (ref "J19") (pin "2-A13") (pinfunction "MS_2-A13") (pintype "passive"))
    )
    (net (code "241") (name "unconnected-(J19BR-MS-Pad2-A14)") (class "Default")
      (node (ref "J19") (pin "2-A14") (pinfunction "MS_2-A14") (pintype "passive"))
    )
    (net (code "242") (name "unconnected-(J19BS-MS-Pad2-A15)") (class "Default")
      (node (ref "J19") (pin "2-A15") (pinfunction "MS_2-A15") (pintype "passive"))
    )
    (net (code "243") (name "unconnected-(J19BT-MS-Pad2-A16)") (class "Default")
      (node (ref "J19") (pin "2-A16") (pinfunction "MS_2-A16") (pintype "passive"))
    )
    (net (code "244") (name "unconnected-(J19BU-MS-Pad2-A17)") (class "Default")
      (node (ref "J19") (pin "2-A17") (pinfunction "MS_2-A17") (pintype "passive"))
    )
    (net (code "245") (name "unconnected-(J19BV-MS-Pad2-A18)") (class "Default")
      (node (ref "J19") (pin "2-A18") (pinfunction "MS_2-A18") (pintype "passive"))
    )
    (net (code "246") (name "unconnected-(J19BW-MS-Pad2-A19)") (class "Default")
      (node (ref "J19") (pin "2-A19") (pinfunction "MS_2-A19") (pintype "passive"))
    )
    (net (code "247") (name "unconnected-(J19BX-MS-Pad2-A2)") (class "Default")
      (node (ref "J19") (pin "2-A2") (pinfunction "MS_2-A2") (pintype "passive"))
    )
    (net (code "248") (name "unconnected-(J19BY-MS-Pad2-A20)") (class "Default")
      (node (ref "J19") (pin "2-A20") (pinfunction "MS_2-A20") (pintype "passive"))
    )
    (net (code "249") (name "unconnected-(J19BZ-MS-Pad2-A21)") (class "Default")
      (node (ref "J19") (pin "2-A21") (pinfunction "MS_2-A21") (pintype "passive"))
    )
    (net (code "250") (name "unconnected-(J19C-MS-Pad1-A11)") (class "Default")
      (node (ref "J19") (pin "1-A11") (pinfunction "MS_1-A11") (pintype "passive"))
    )
    (net (code "251") (name "unconnected-(J19CA-MS-Pad2-A22)") (class "Default")
      (node (ref "J19") (pin "2-A22") (pinfunction "MS_2-A22") (pintype "passive"))
    )
    (net (code "252") (name "unconnected-(J19CB-MS-Pad2-A23)") (class "Default")
      (node (ref "J19") (pin "2-A23") (pinfunction "MS_2-A23") (pintype "passive"))
    )
    (net (code "253") (name "unconnected-(J19CC-MS-Pad2-A24)") (class "Default")
      (node (ref "J19") (pin "2-A24") (pinfunction "MS_2-A24") (pintype "passive"))
    )
    (net (code "254") (name "unconnected-(J19CD-MS-Pad2-A25)") (class "Default")
      (node (ref "J19") (pin "2-A25") (pinfunction "MS_2-A25") (pintype "passive"))
    )
    (net (code "255") (name "unconnected-(J19CE-MS-Pad2-A26)") (class "Default")
      (node (ref "J19") (pin "2-A26") (pinfunction "MS_2-A26") (pintype "passive"))
    )
    (net (code "256") (name "unconnected-(J19CF-MS-Pad2-A27)") (class "Default")
      (node (ref "J19") (pin "2-A27") (pinfunction "MS_2-A27") (pintype "passive"))
    )
    (net (code "257") (name "unconnected-(J19CG-MS-Pad2-A28)") (class "Default")
      (node (ref "J19") (pin "2-A28") (pinfunction "MS_2-A28") (pintype "passive"))
    )
    (net (code "258") (name "unconnected-(J19CH-MS-Pad2-A29)") (class "Default")
      (node (ref "J19") (pin "2-A29") (pinfunction "MS_2-A29") (pintype "passive"))
    )
    (net (code "259") (name "unconnected-(J19CI-MS-Pad2-A3)") (class "Default")
      (node (ref "J19") (pin "2-A3") (pinfunction "MS_2-A3") (pintype "passive"))
    )
    (net (code "260") (name "unconnected-(J19CJ-MS-Pad2-A30)") (class "Default")
      (node (ref "J19") (pin "2-A30") (pinfunction "MS_2-A30") (pintype "passive"))
    )
    (net (code "261") (name "unconnected-(J19CK-MS-Pad2-A31)") (class "Default")
      (node (ref "J19") (pin "2-A31") (pinfunction "MS_2-A31") (pintype "passive"))
    )
    (net (code "262") (name "unconnected-(J19CM-MS-Pad2-A4)") (class "Default")
      (node (ref "J19") (pin "2-A4") (pinfunction "MS_2-A4") (pintype "passive"))
    )
    (net (code "263") (name "unconnected-(J19CN-MS-Pad2-A5)") (class "Default")
      (node (ref "J19") (pin "2-A5") (pinfunction "MS_2-A5") (pintype "passive"))
    )
    (net (code "264") (name "unconnected-(J19CO-MS-Pad2-A6)") (class "Default")
      (node (ref "J19") (pin "2-A6") (pinfunction "MS_2-A6") (pintype "passive"))
    )
    (net (code "265") (name "unconnected-(J19CP-MS-Pad2-A7)") (class "Default")
      (node (ref "J19") (pin "2-A7") (pinfunction "MS_2-A7") (pintype "passive"))
    )
    (net (code "266") (name "unconnected-(J19CQ-MS-Pad2-A8)") (class "Default")
      (node (ref "J19") (pin "2-A8") (pinfunction "MS_2-A8") (pintype "passive"))
    )
    (net (code "267") (name "unconnected-(J19CS-MSV-Pad2-C1)") (class "Default")
      (node (ref "J19") (pin "2-C1") (pinfunction "MSV_2-C1") (pintype "passive"))
    )
    (net (code "268") (name "unconnected-(J19CT-MS-Pad2-C10)") (class "Default")
      (node (ref "J19") (pin "2-C10") (pinfunction "MS_2-C10") (pintype "passive"))
    )
    (net (code "269") (name "unconnected-(J19CU-MS-Pad2-C11)") (class "Default")
      (node (ref "J19") (pin "2-C11") (pinfunction "MS_2-C11") (pintype "passive"))
    )
    (net (code "270") (name "unconnected-(J19CV-MS-Pad2-C12)") (class "Default")
      (node (ref "J19") (pin "2-C12") (pinfunction "MS_2-C12") (pintype "passive"))
    )
    (net (code "271") (name "unconnected-(J19CW-MS-Pad2-C13)") (class "Default")
      (node (ref "J19") (pin "2-C13") (pinfunction "MS_2-C13") (pintype "passive"))
    )
    (net (code "272") (name "unconnected-(J19CX-MS-Pad2-C14)") (class "Default")
      (node (ref "J19") (pin "2-C14") (pinfunction "MS_2-C14") (pintype "passive"))
    )
    (net (code "273") (name "unconnected-(J19CY-MS-Pad2-C15)") (class "Default")
      (node (ref "J19") (pin "2-C15") (pinfunction "MS_2-C15") (pintype "passive"))
    )
    (net (code "274") (name "unconnected-(J19CZ-MS-Pad2-C16)") (class "Default")
      (node (ref "J19") (pin "2-C16") (pinfunction "MS_2-C16") (pintype "passive"))
    )
    (net (code "275") (name "unconnected-(J19D-MS-Pad1-A12)") (class "Default")
      (node (ref "J19") (pin "1-A12") (pinfunction "MS_1-A12") (pintype "passive"))
    )
    (net (code "276") (name "unconnected-(J19DA-MS-Pad2-C17)") (class "Default")
      (node (ref "J19") (pin "2-C17") (pinfunction "MS_2-C17") (pintype "passive"))
    )
    (net (code "277") (name "unconnected-(J19DB-MS-Pad2-C18)") (class "Default")
      (node (ref "J19") (pin "2-C18") (pinfunction "MS_2-C18") (pintype "passive"))
    )
    (net (code "278") (name "unconnected-(J19DC-MS-Pad2-C19)") (class "Default")
      (node (ref "J19") (pin "2-C19") (pinfunction "MS_2-C19") (pintype "passive"))
    )
    (net (code "279") (name "unconnected-(J19DD-MS-Pad2-C2)") (class "Default")
      (node (ref "J19") (pin "2-C2") (pinfunction "MS_2-C2") (pintype "passive"))
    )
    (net (code "280") (name "unconnected-(J19DE-MS-Pad2-C20)") (class "Default")
      (node (ref "J19") (pin "2-C20") (pinfunction "MS_2-C20") (pintype "passive"))
    )
    (net (code "281") (name "unconnected-(J19DF-MS-Pad2-C21)") (class "Default")
      (node (ref "J19") (pin "2-C21") (pinfunction "MS_2-C21") (pintype "passive"))
    )
    (net (code "282") (name "unconnected-(J19DG-MS-Pad2-C22)") (class "Default")
      (node (ref "J19") (pin "2-C22") (pinfunction "MS_2-C22") (pintype "passive"))
    )
    (net (code "283") (name "unconnected-(J19DH-MS-Pad2-C23)") (class "Default")
      (node (ref "J19") (pin "2-C23") (pinfunction "MS_2-C23") (pintype "passive"))
    )
    (net (code "284") (name "unconnected-(J19DI-MS-Pad2-C24)") (class "Default")
      (node (ref "J19") (pin "2-C24") (pinfunction "MS_2-C24") (pintype "passive"))
    )
    (net (code "285") (name "unconnected-(J19DJ-MS-Pad2-C25)") (class "Default")
      (node (ref "J19") (pin "2-C25") (pinfunction "MS_2-C25") (pintype "passive"))
    )
    (net (code "286") (name "unconnected-(J19DK-MS-Pad2-C26)") (class "Default")
      (node (ref "J19") (pin "2-C26") (pinfunction "MS_2-C26") (pintype "passive"))
    )
    (net (code "287") (name "unconnected-(J19DL-MS-Pad2-C27)") (class "Default")
      (node (ref "J19") (pin "2-C27") (pinfunction "MS_2-C27") (pintype "passive"))
    )
    (net (code "288") (name "unconnected-(J19DM-MS-Pad2-C28)") (class "Default")
      (node (ref "J19") (pin "2-C28") (pinfunction "MS_2-C28") (pintype "passive"))
    )
    (net (code "289") (name "unconnected-(J19DN-MS-Pad2-C29)") (class "Default")
      (node (ref "J19") (pin "2-C29") (pinfunction "MS_2-C29") (pintype "passive"))
    )
    (net (code "290") (name "unconnected-(J19DO-MS-Pad2-C3)") (class "Default")
      (node (ref "J19") (pin "2-C3") (pinfunction "MS_2-C3") (pintype "passive"))
    )
    (net (code "291") (name "unconnected-(J19DP-MS-Pad2-C30)") (class "Default")
      (node (ref "J19") (pin "2-C30") (pinfunction "MS_2-C30") (pintype "passive"))
    )
    (net (code "292") (name "unconnected-(J19DQ-MS-Pad2-C31)") (class "Default")
      (node (ref "J19") (pin "2-C31") (pinfunction "MS_2-C31") (pintype "passive"))
    )
    (net (code "293") (name "unconnected-(J19DS-MS-Pad2-C4)") (class "Default")
      (node (ref "J19") (pin "2-C4") (pinfunction "MS_2-C4") (pintype "passive"))
    )
    (net (code "294") (name "unconnected-(J19DT-MS-Pad2-C5)") (class "Default")
      (node (ref "J19") (pin "2-C5") (pinfunction "MS_2-C5") (pintype "passive"))
    )
    (net (code "295") (name "unconnected-(J19DU-MS-Pad2-C6)") (class "Default")
      (node (ref "J19") (pin "2-C6") (pinfunction "MS_2-C6") (pintype "passive"))
    )
    (net (code "296") (name "unconnected-(J19DV-MS-Pad2-C7)") (class "Default")
      (node (ref "J19") (pin "2-C7") (pinfunction "MS_2-C7") (pintype "passive"))
    )
    (net (code "297") (name "unconnected-(J19DW-MS-Pad2-C8)") (class "Default")
      (node (ref "J19") (pin "2-C8") (pinfunction "MS_2-C8") (pintype "passive"))
    )
    (net (code "298") (name "unconnected-(J19E-MS-Pad1-A13)") (class "Default")
      (node (ref "J19") (pin "1-A13") (pinfunction "MS_1-A13") (pintype "passive"))
    )
    (net (code "299") (name "unconnected-(J19F-MS-Pad1-A14)") (class "Default")
      (node (ref "J19") (pin "1-A14") (pinfunction "MS_1-A14") (pintype "passive"))
    )
    (net (code "300") (name "unconnected-(J19G-MS-Pad1-A15)") (class "Default")
      (node (ref "J19") (pin "1-A15") (pinfunction "MS_1-A15") (pintype "passive"))
    )
    (net (code "301") (name "unconnected-(J19H-MS-Pad1-A16)") (class "Default")
      (node (ref "J19") (pin "1-A16") (pinfunction "MS_1-A16") (pintype "passive"))
    )
    (net (code "302") (name "unconnected-(J19I-MS-Pad1-A17)") (class "Default")
      (node (ref "J19") (pin "1-A17") (pinfunction "MS_1-A17") (pintype "passive"))
    )
    (net (code "303") (name "unconnected-(J19J-MS-Pad1-A18)") (class "Default")
      (node (ref "J19") (pin "1-A18") (pinfunction "MS_1-A18") (pintype "passive"))
    )
    (net (code "304") (name "unconnected-(J19K-MS-Pad1-A19)") (class "Default")
      (node (ref "J19") (pin "1-A19") (pinfunction "MS_1-A19") (pintype "passive"))
    )
    (net (code "305") (name "unconnected-(J19L-MS-Pad1-A2)") (class "Default")
      (node (ref "J19") (pin "1-A2") (pinfunction "MS_1-A2") (pintype "passive"))
    )
    (net (code "306") (name "unconnected-(J19M-MS-Pad1-A20)") (class "Default")
      (node (ref "J19") (pin "1-A20") (pinfunction "MS_1-A20") (pintype "passive"))
    )
    (net (code "307") (name "unconnected-(J19N-MS-Pad1-A21)") (class "Default")
      (node (ref "J19") (pin "1-A21") (pinfunction "MS_1-A21") (pintype "passive"))
    )
    (net (code "308") (name "unconnected-(J19O-MS-Pad1-A22)") (class "Default")
      (node (ref "J19") (pin "1-A22") (pinfunction "MS_1-A22") (pintype "passive"))
    )
    (net (code "309") (name "unconnected-(J19P-MS-Pad1-A23)") (class "Default")
      (node (ref "J19") (pin "1-A23") (pinfunction "MS_1-A23") (pintype "passive"))
    )
    (net (code "310") (name "unconnected-(J19Q-MS-Pad1-A24)") (class "Default")
      (node (ref "J19") (pin "1-A24") (pinfunction "MS_1-A24") (pintype "passive"))
    )
    (net (code "311") (name "unconnected-(J19R-MS-Pad1-A25)") (class "Default")
      (node (ref "J19") (pin "1-A25") (pinfunction "MS_1-A25") (pintype "passive"))
    )
    (net (code "312") (name "unconnected-(J19S-MS-Pad1-A26)") (class "Default")
      (node (ref "J19") (pin "1-A26") (pinfunction "MS_1-A26") (pintype "passive"))
    )
    (net (code "313") (name "unconnected-(J19T-MS-Pad1-A27)") (class "Default")
      (node (ref "J19") (pin "1-A27") (pinfunction "MS_1-A27") (pintype "passive"))
    )
    (net (code "314") (name "unconnected-(J19U-MS-Pad1-A28)") (class "Default")
      (node (ref "J19") (pin "1-A28") (pinfunction "MS_1-A28") (pintype "passive"))
    )
    (net (code "315") (name "unconnected-(J19V-MS-Pad1-A29)") (class "Default")
      (node (ref "J19") (pin "1-A29") (pinfunction "MS_1-A29") (pintype "passive"))
    )
    (net (code "316") (name "unconnected-(J19W-MS-Pad1-A3)") (class "Default")
      (node (ref "J19") (pin "1-A3") (pinfunction "MS_1-A3") (pintype "passive"))
    )
    (net (code "317") (name "unconnected-(J19X-MS-Pad1-A30)") (class "Default")
      (node (ref "J19") (pin "1-A30") (pinfunction "MS_1-A30") (pintype "passive"))
    )
    (net (code "318") (name "unconnected-(J19Y-MS-Pad1-A31)") (class "Default")
      (node (ref "J19") (pin "1-A31") (pinfunction "MS_1-A31") (pintype "passive"))
    )
  )
)
